# PCIe-1x-Toolcard.net
KiCad netlist of a schematic drawn in EAGLE
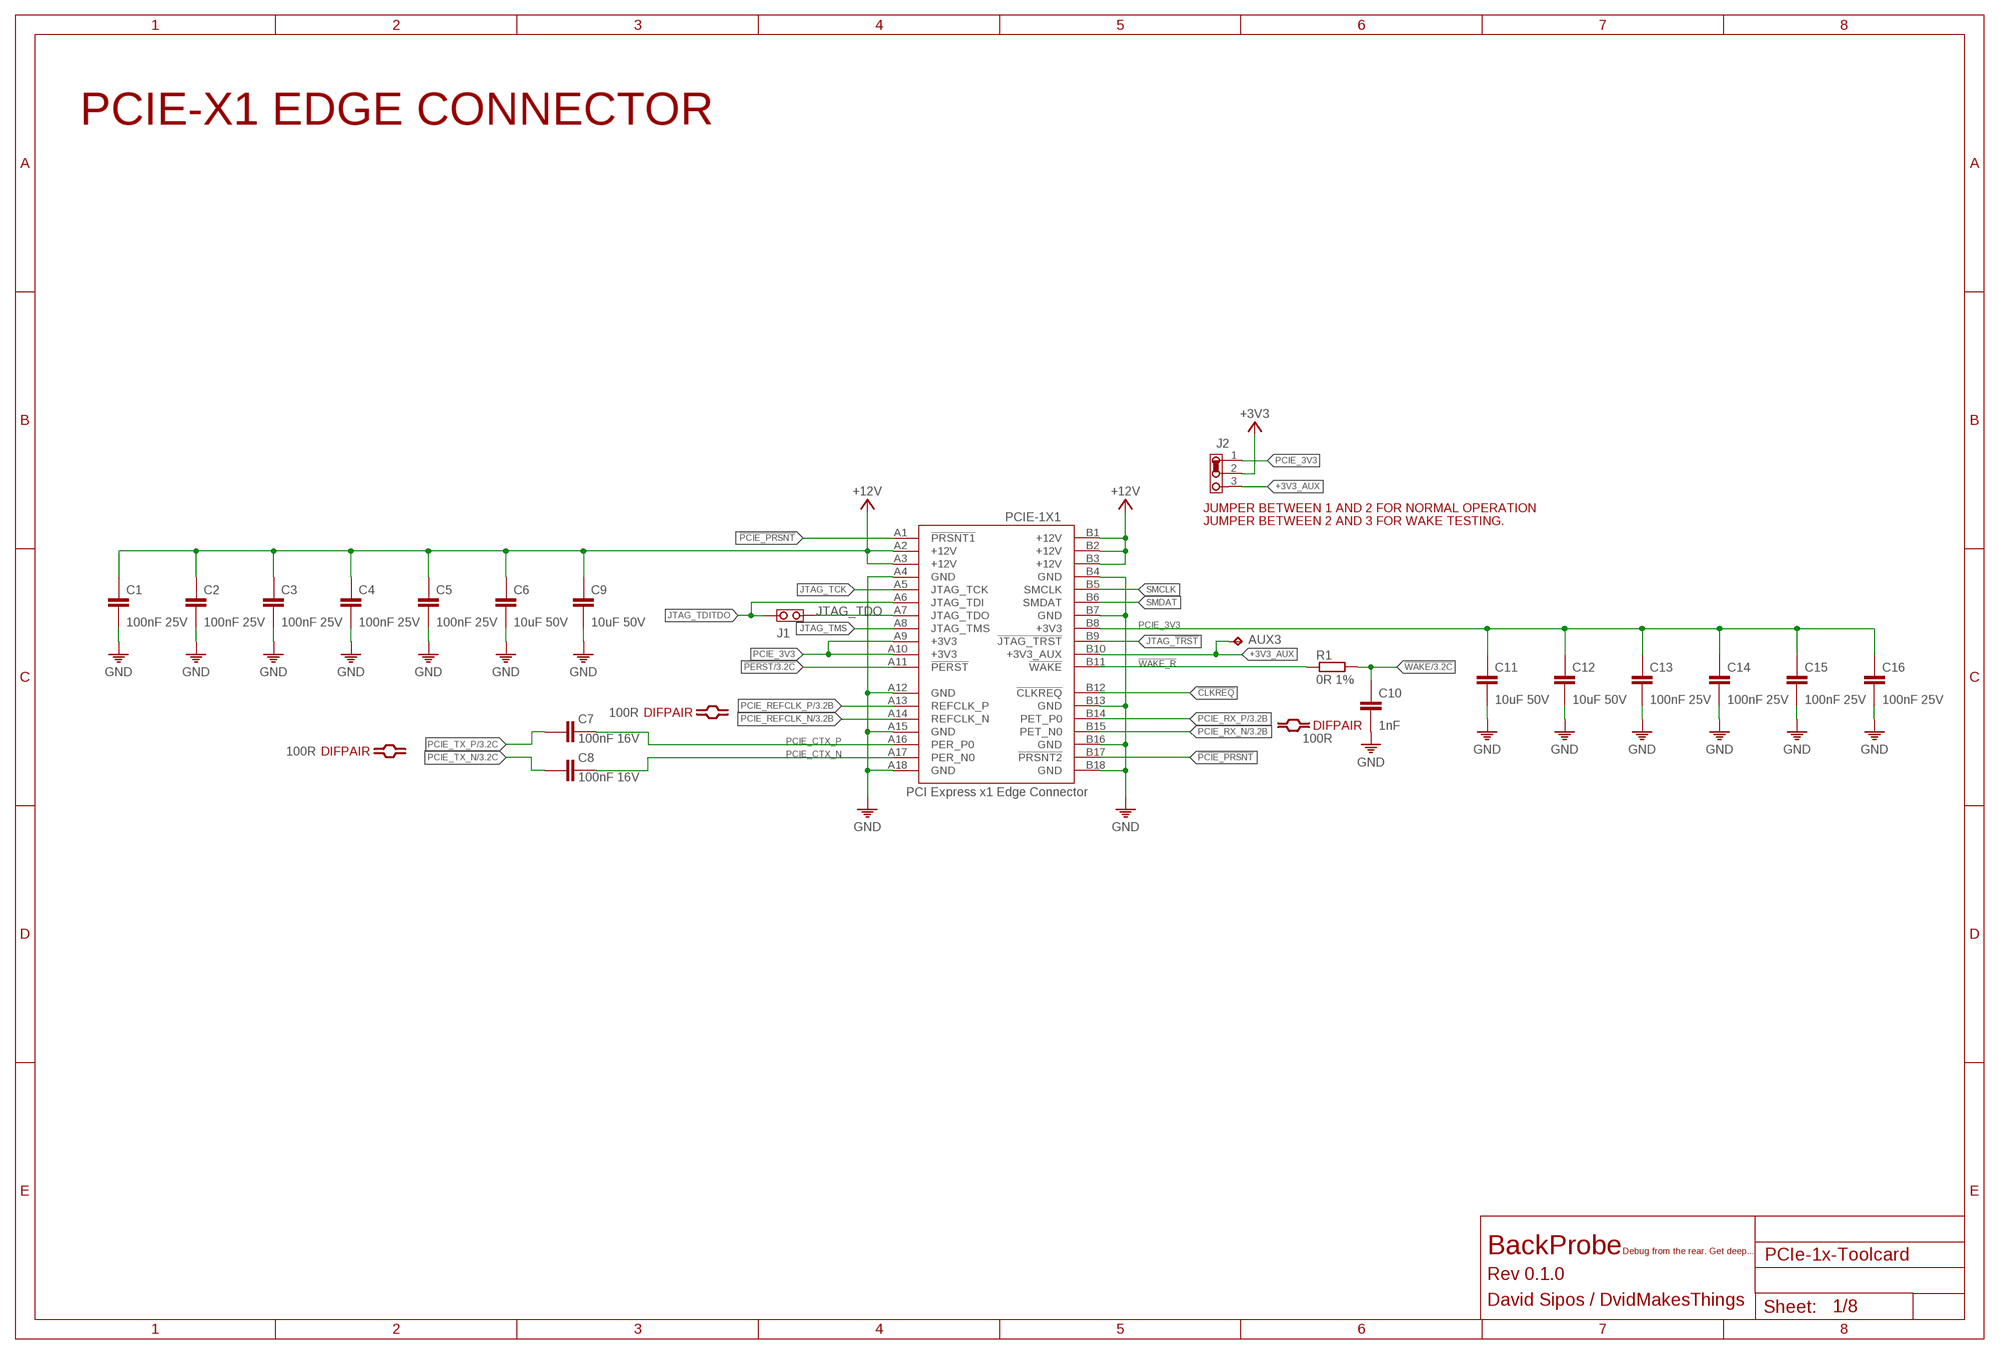
[diagram p0: schematic, sheet 1]
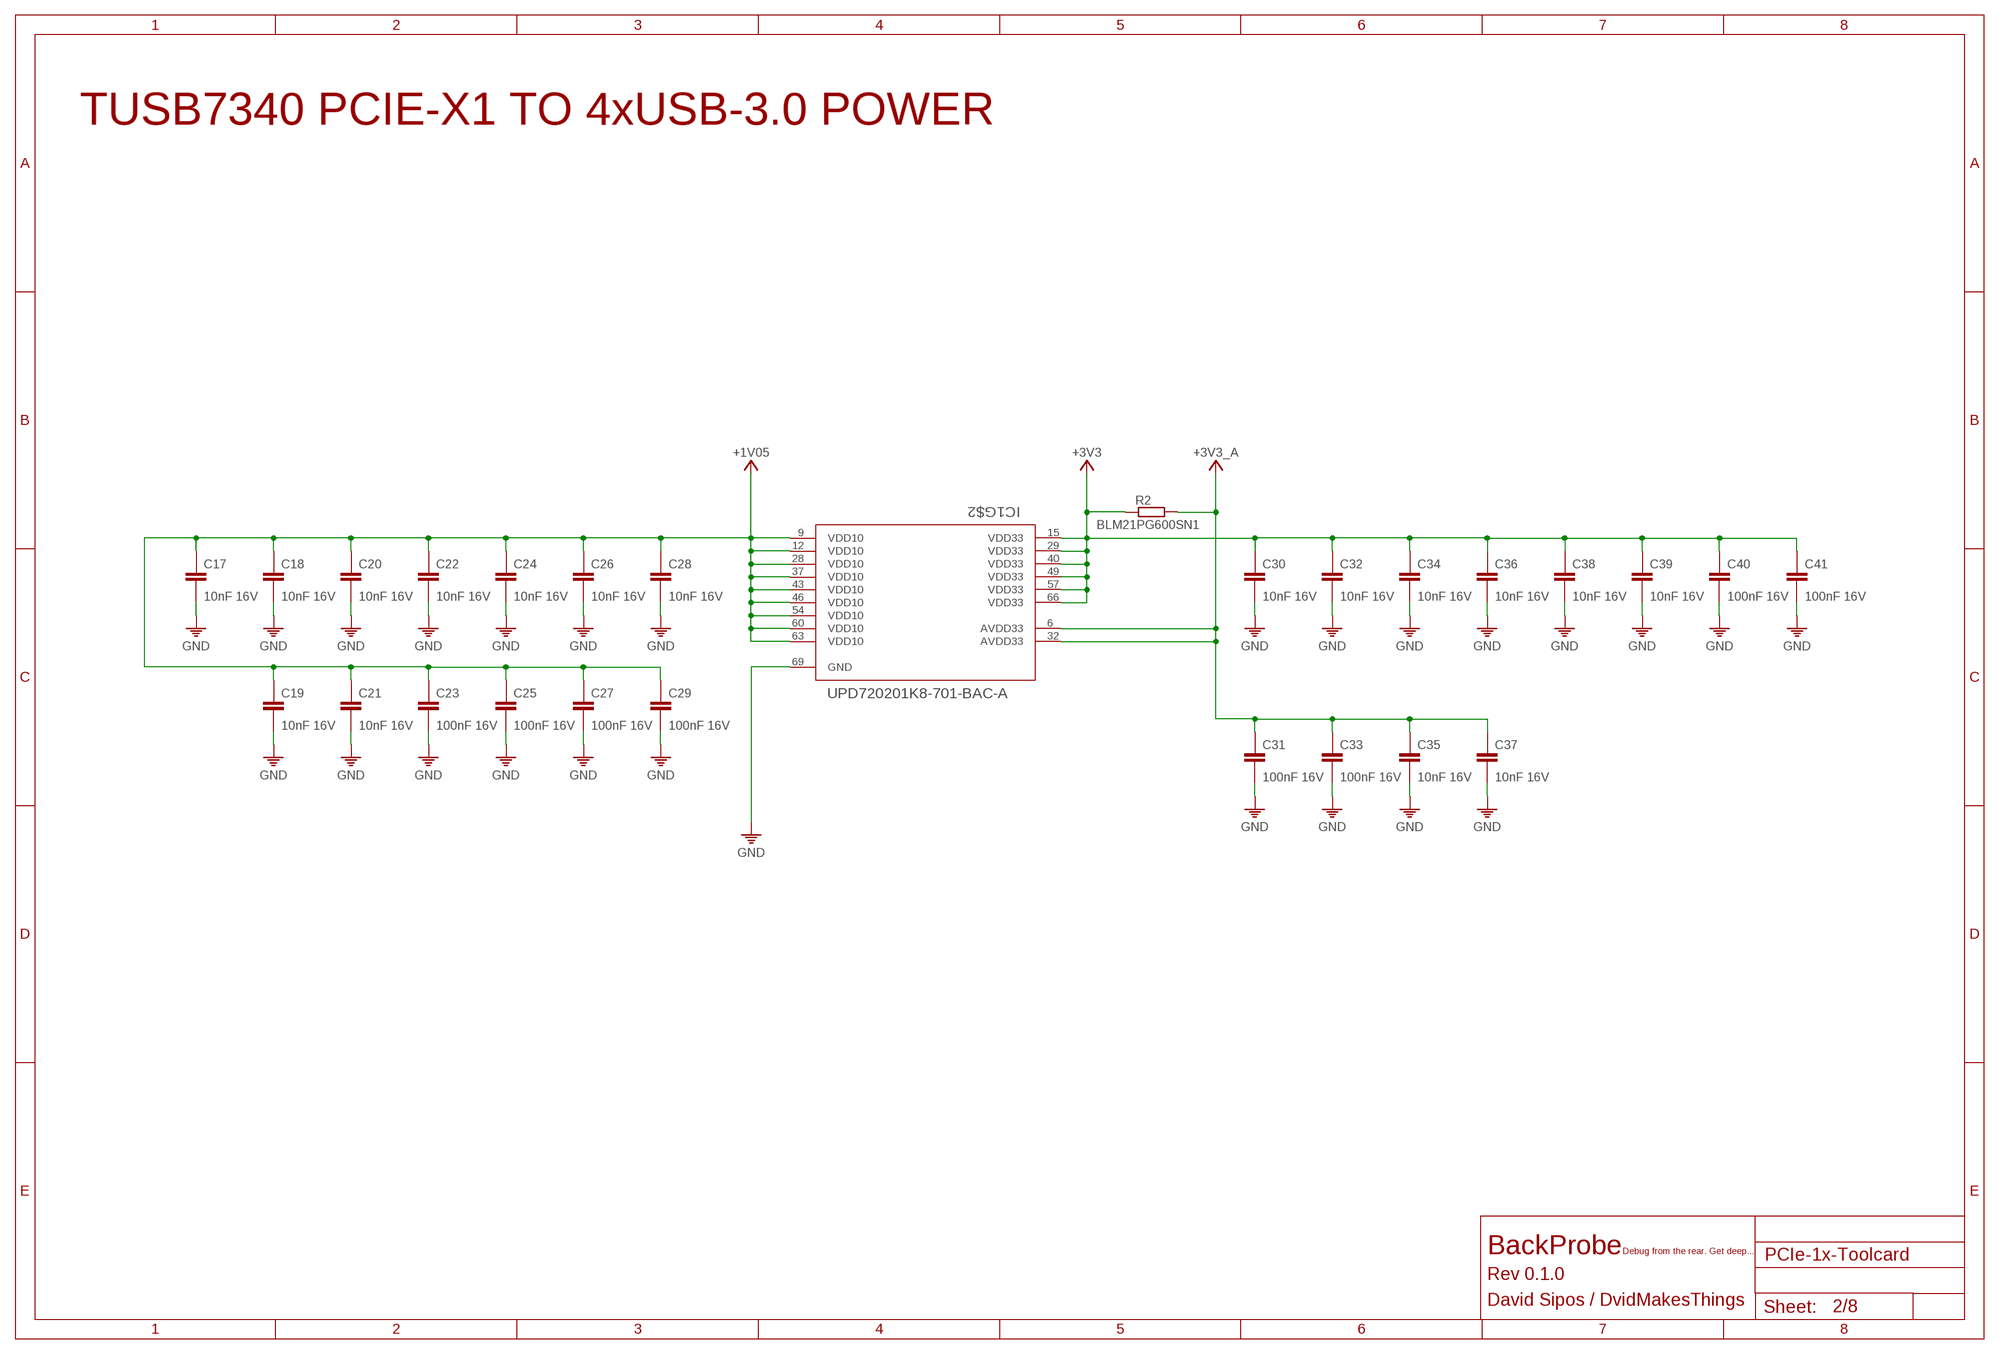
[diagram p1: schematic, sheet 2]
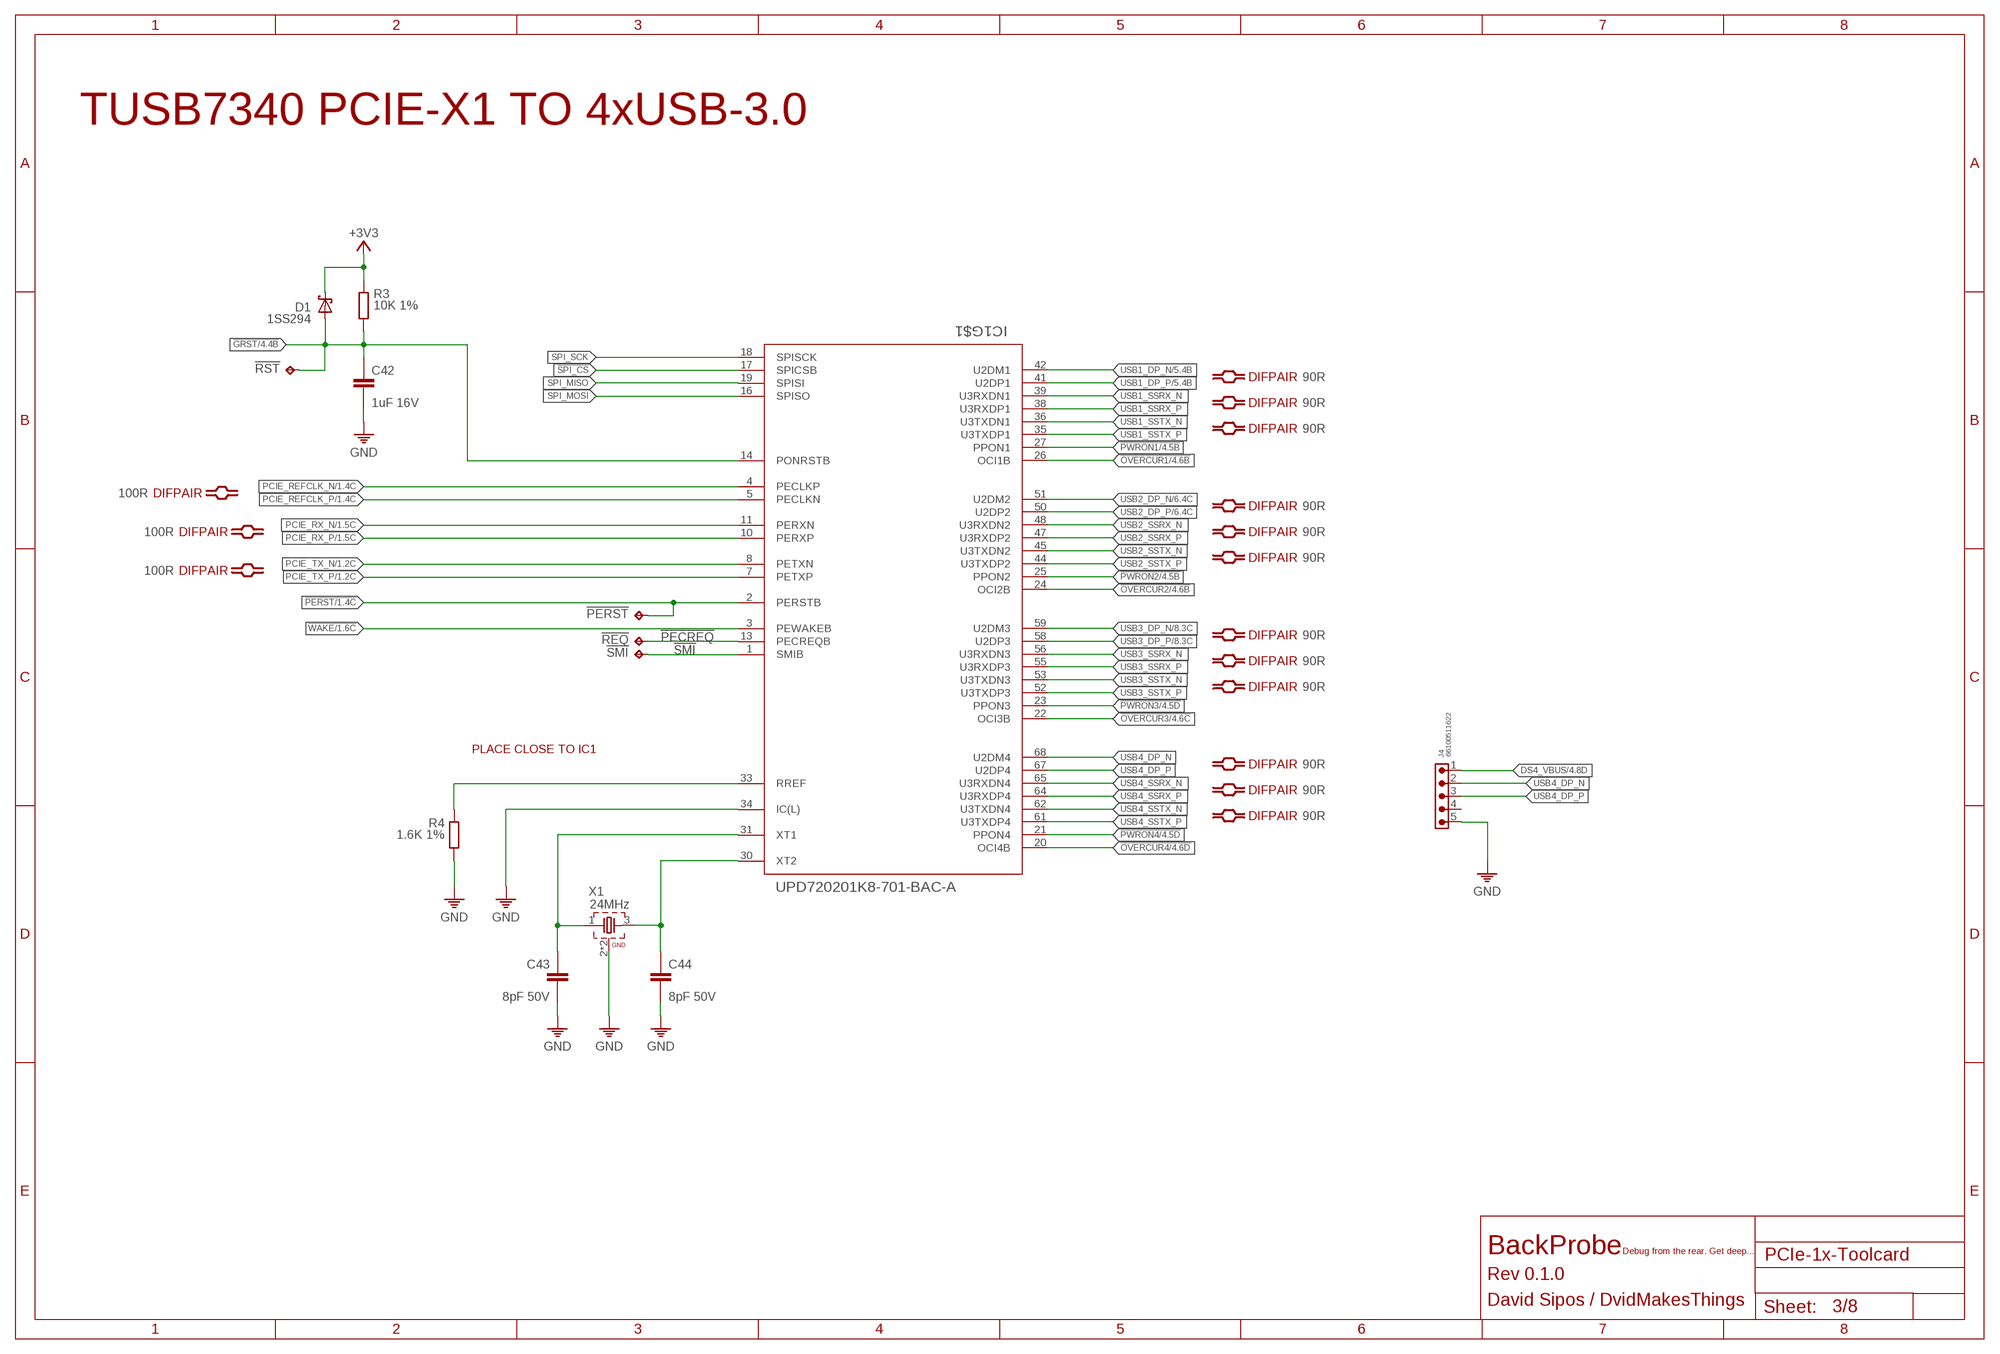
[diagram p2: schematic, sheet 3]
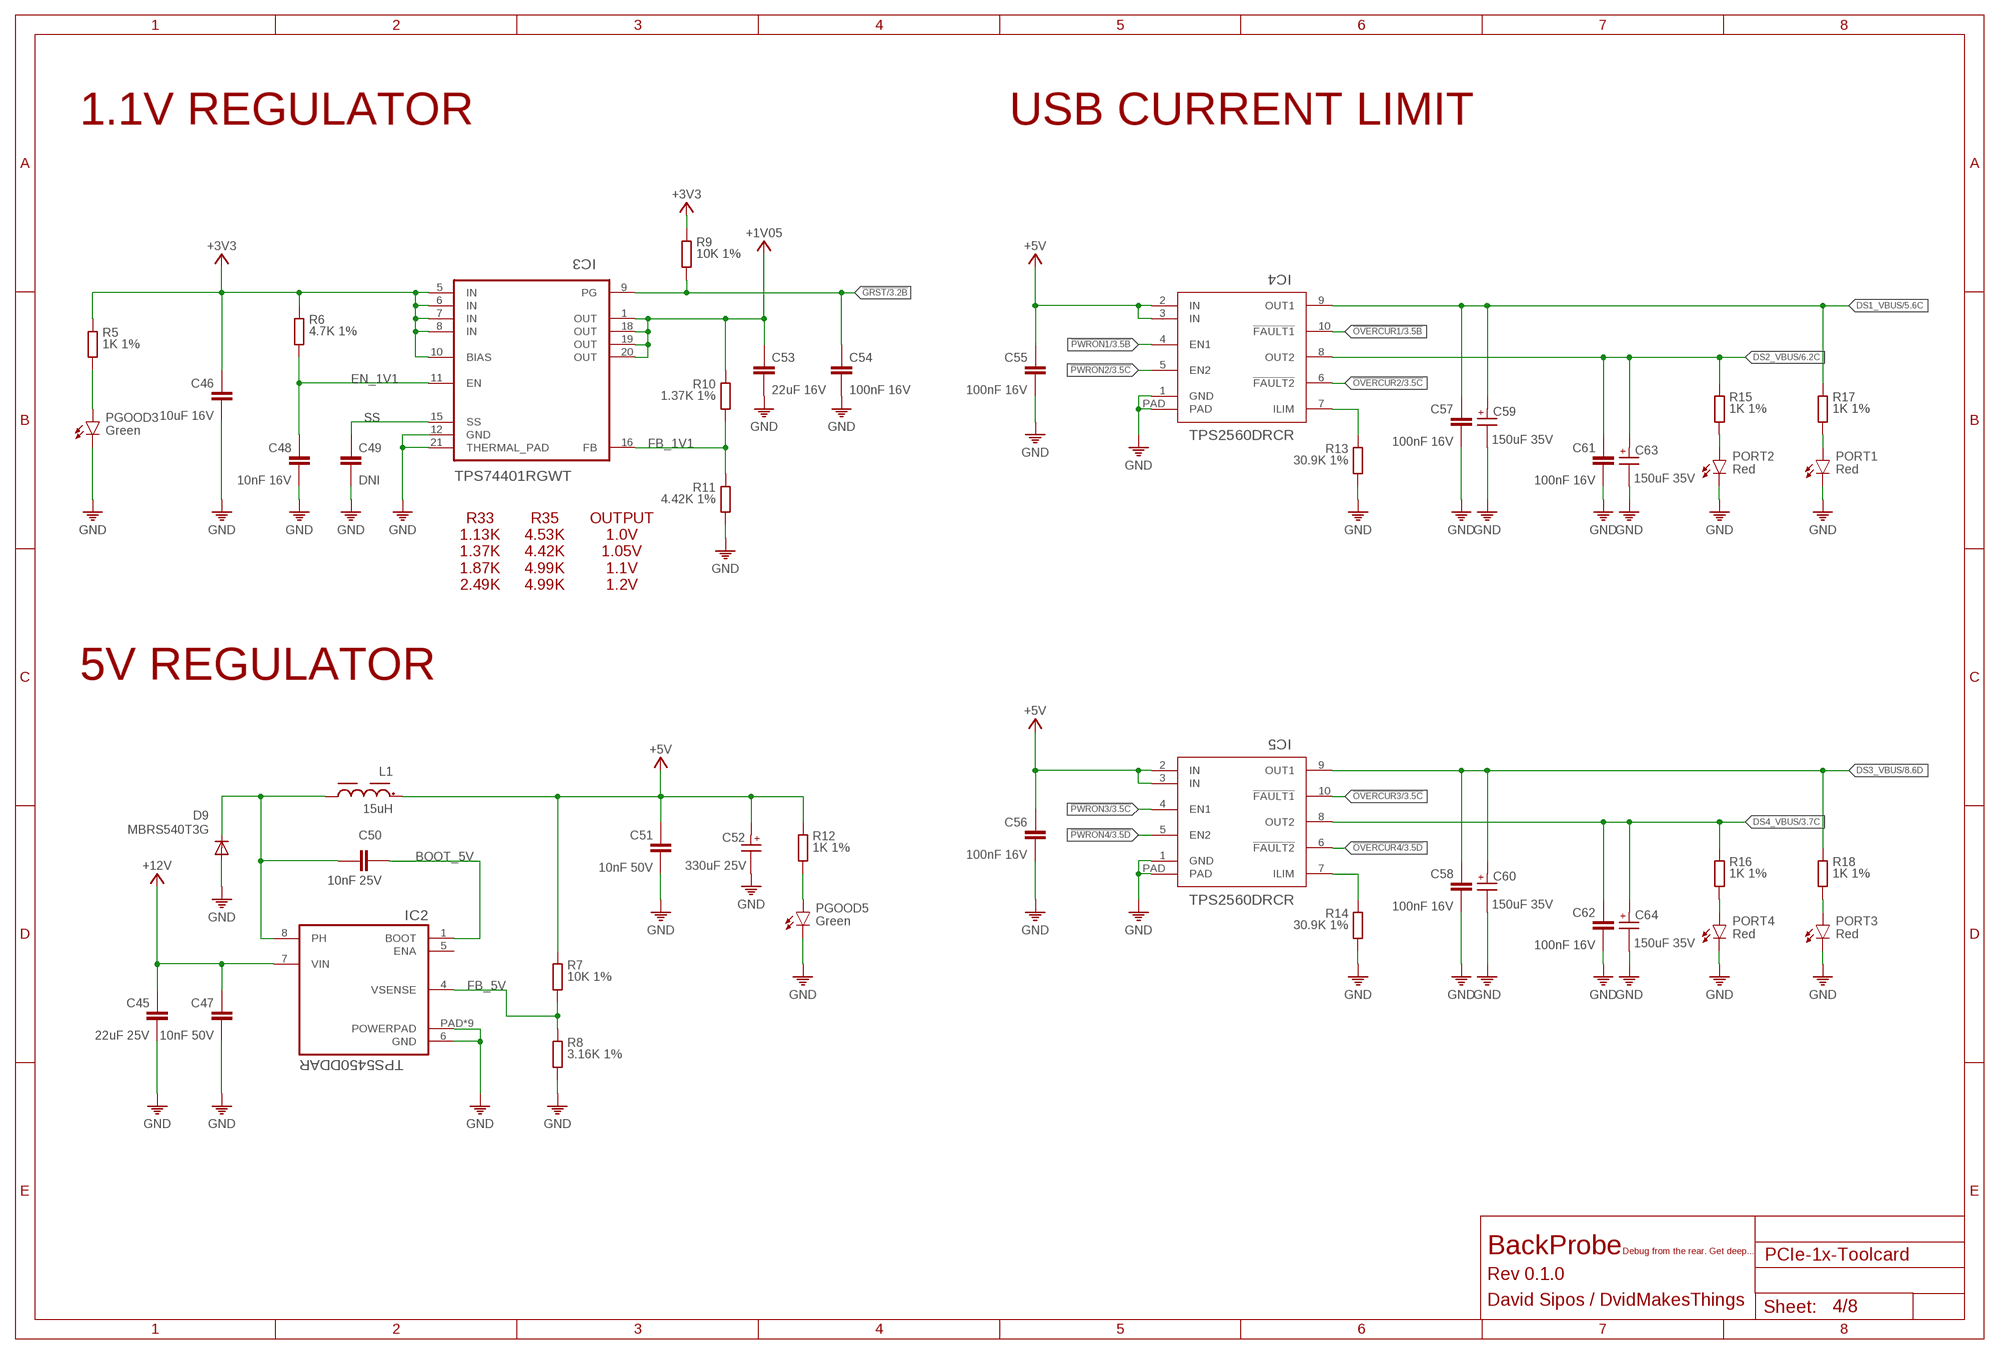
[diagram p3: schematic, sheet 4]
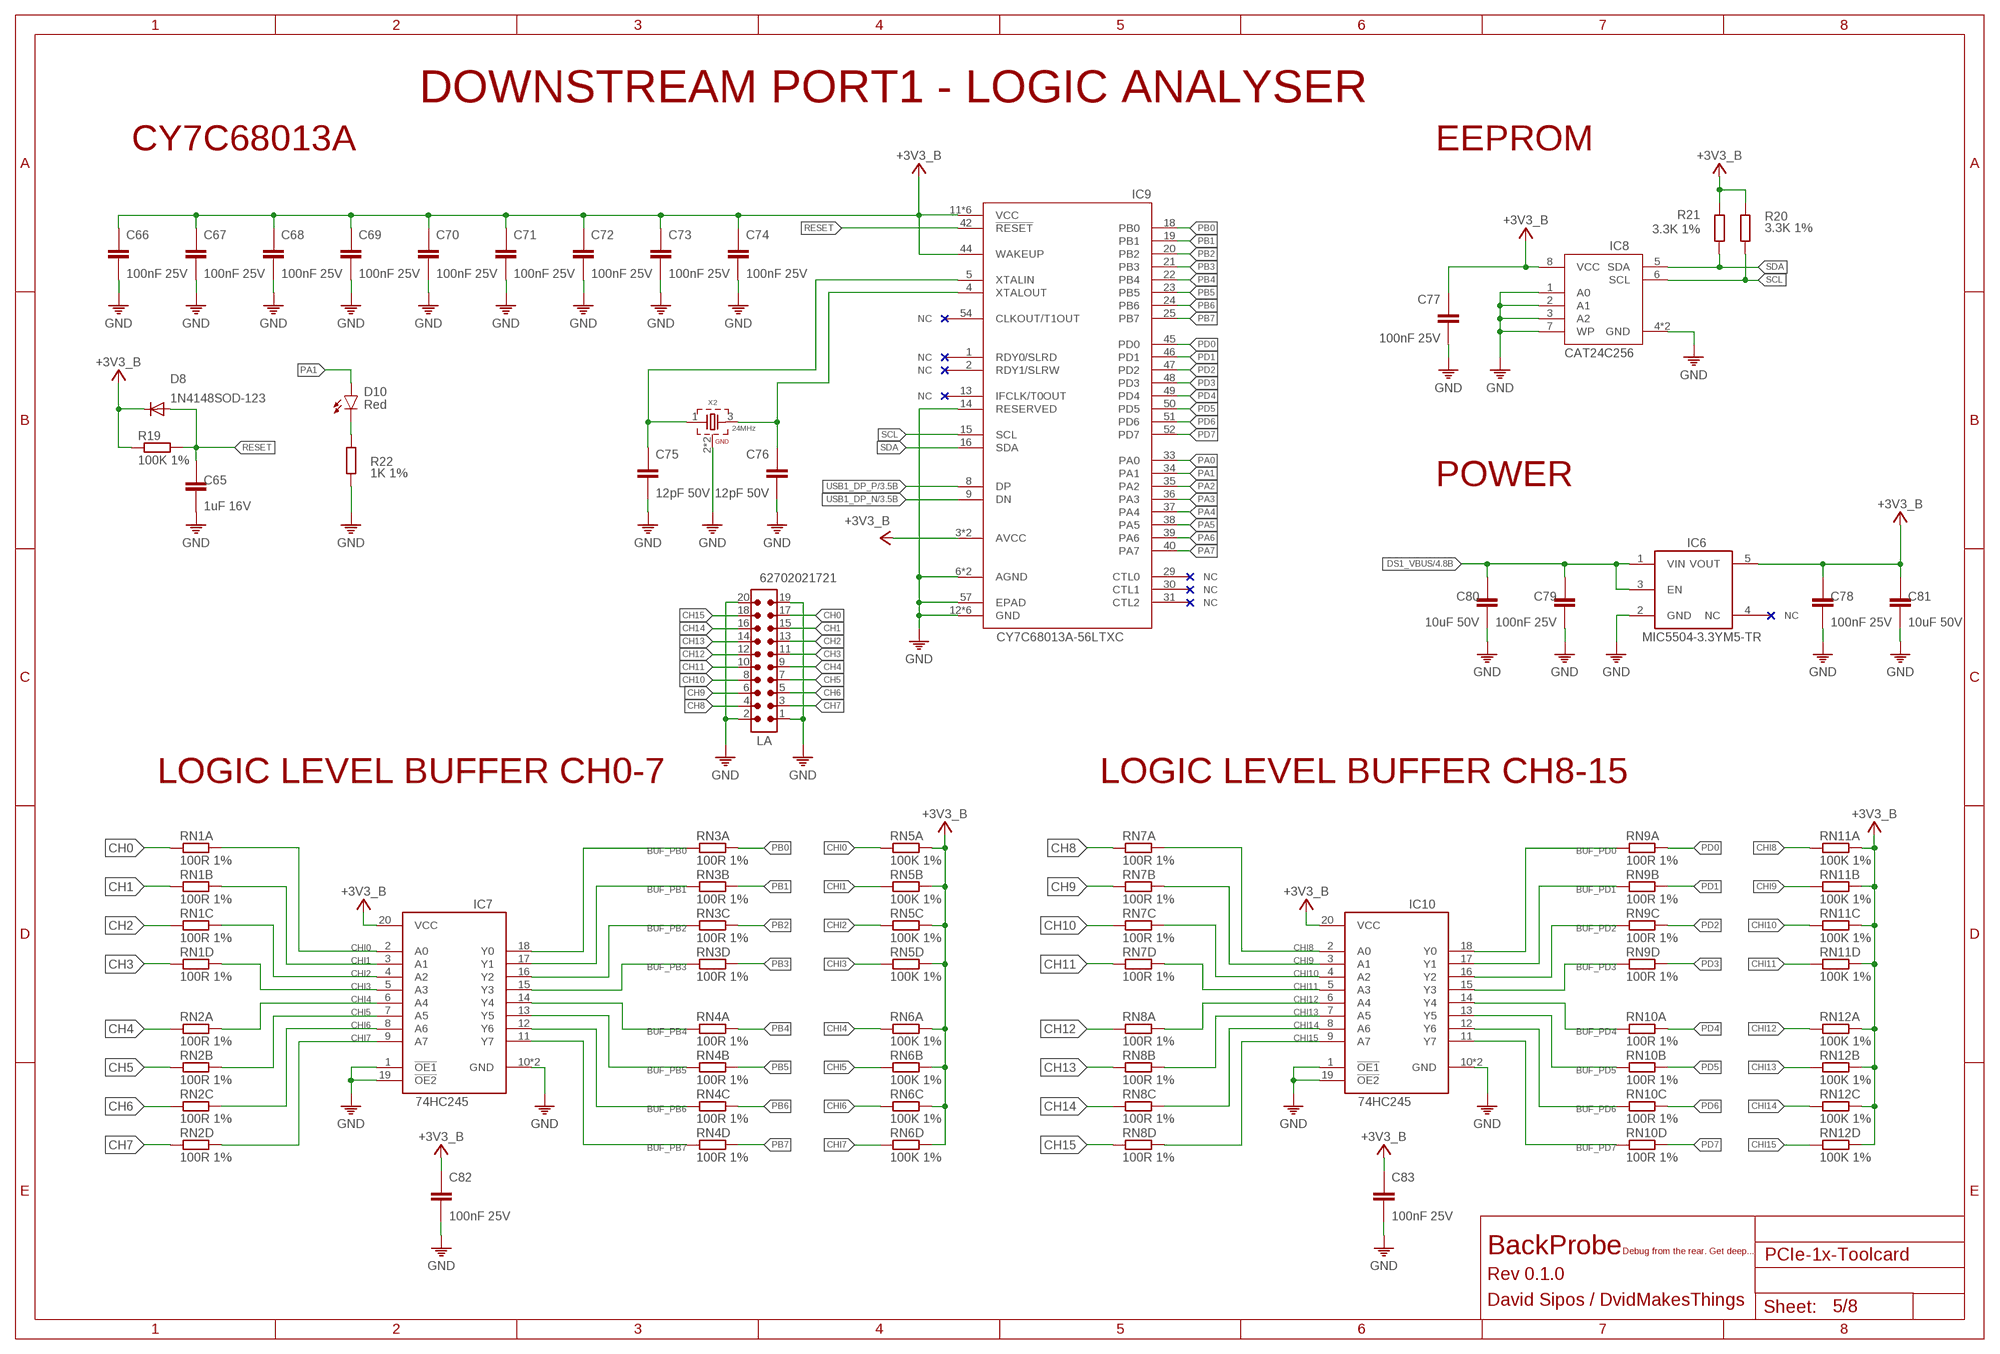
[diagram p4: schematic, sheet 5]
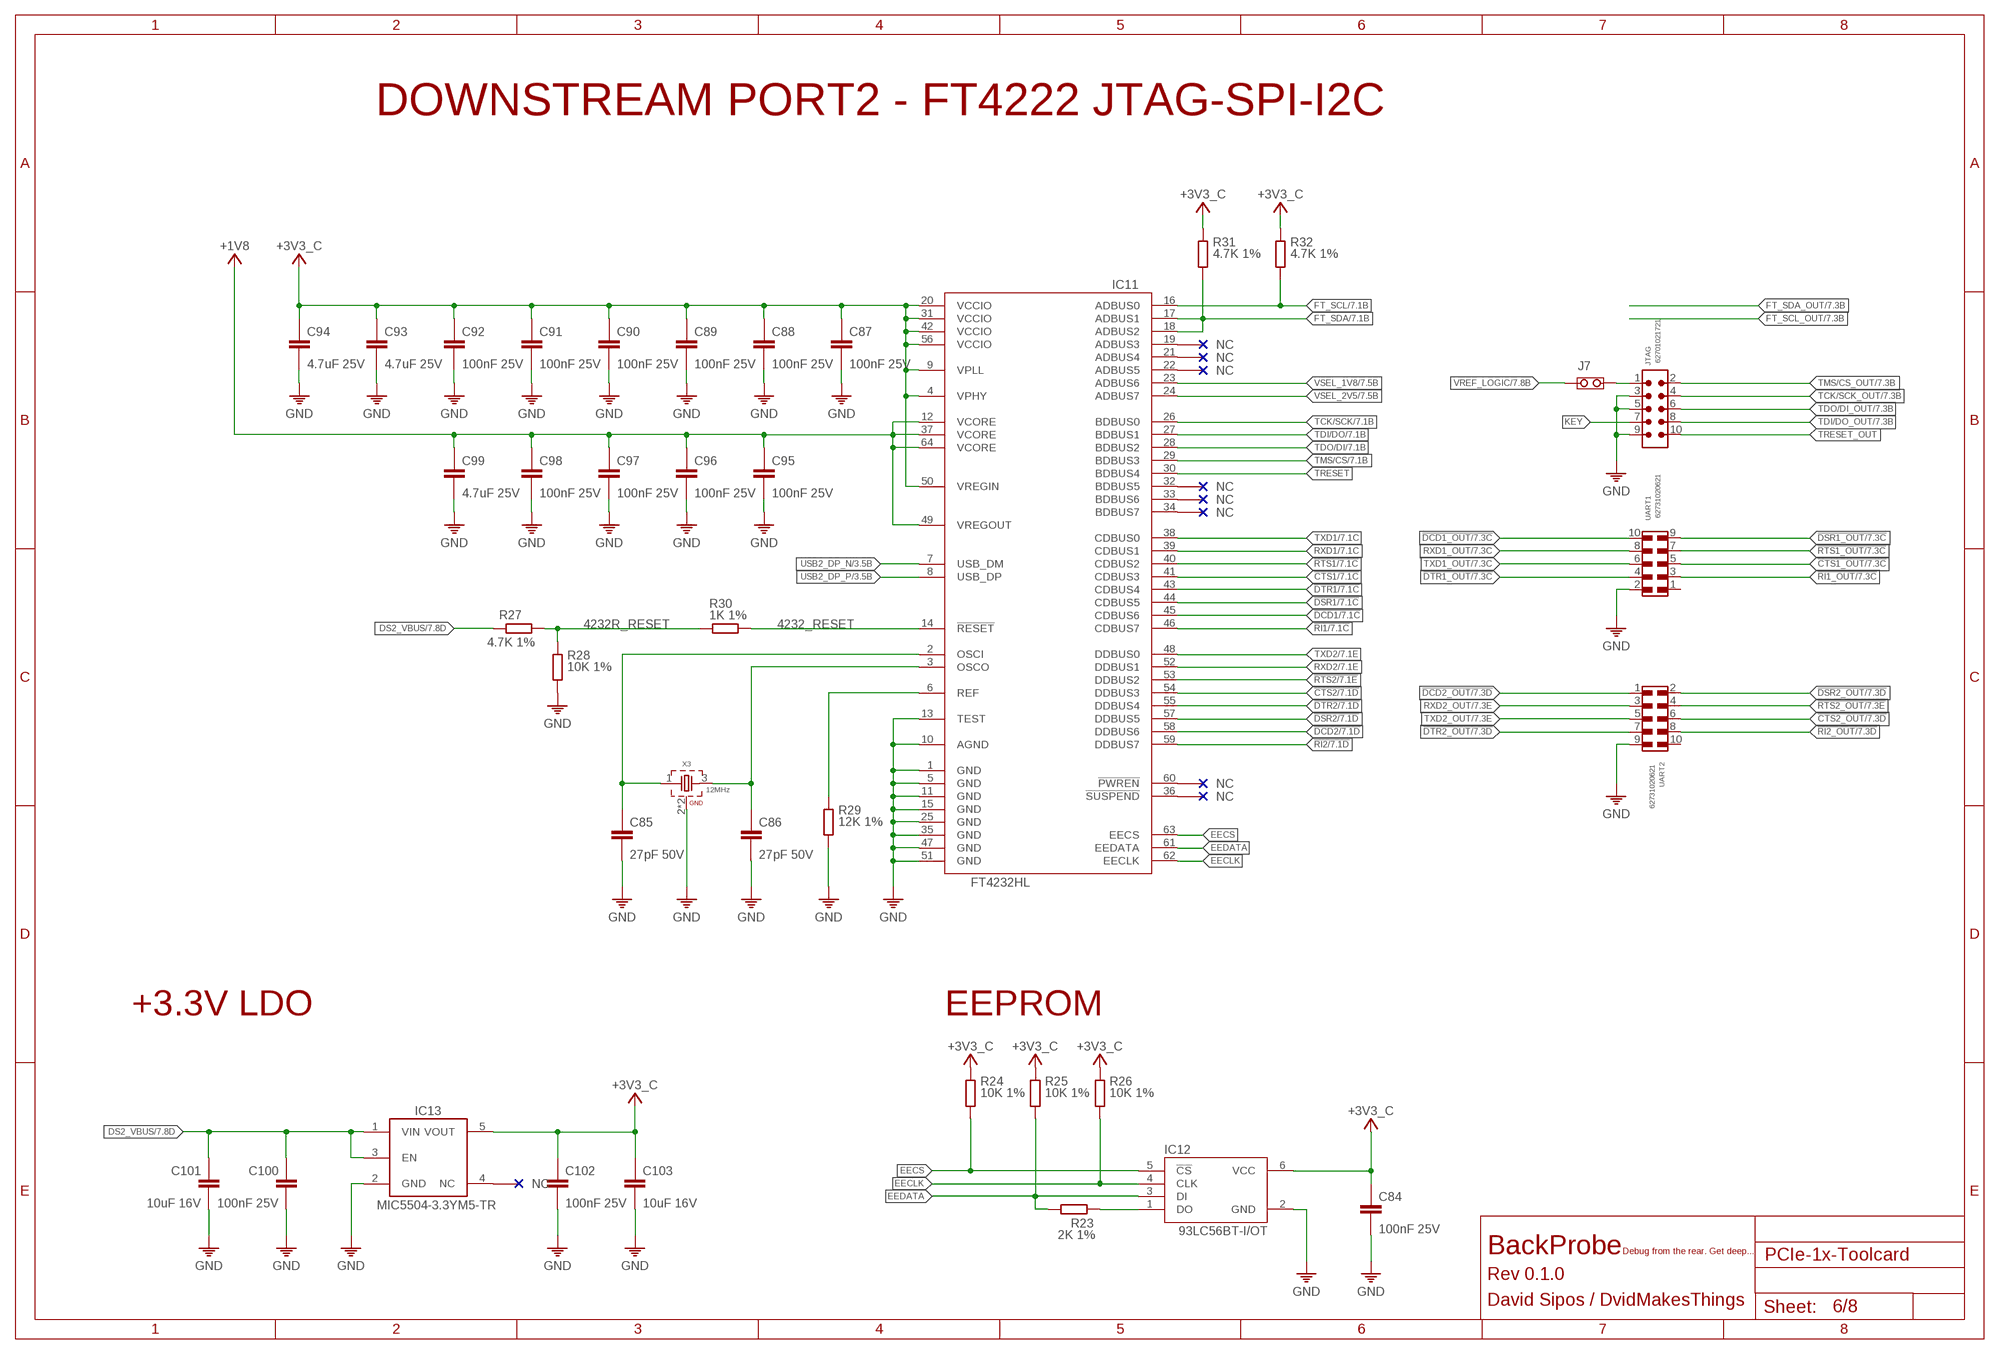
[diagram p5: schematic, sheet 6]
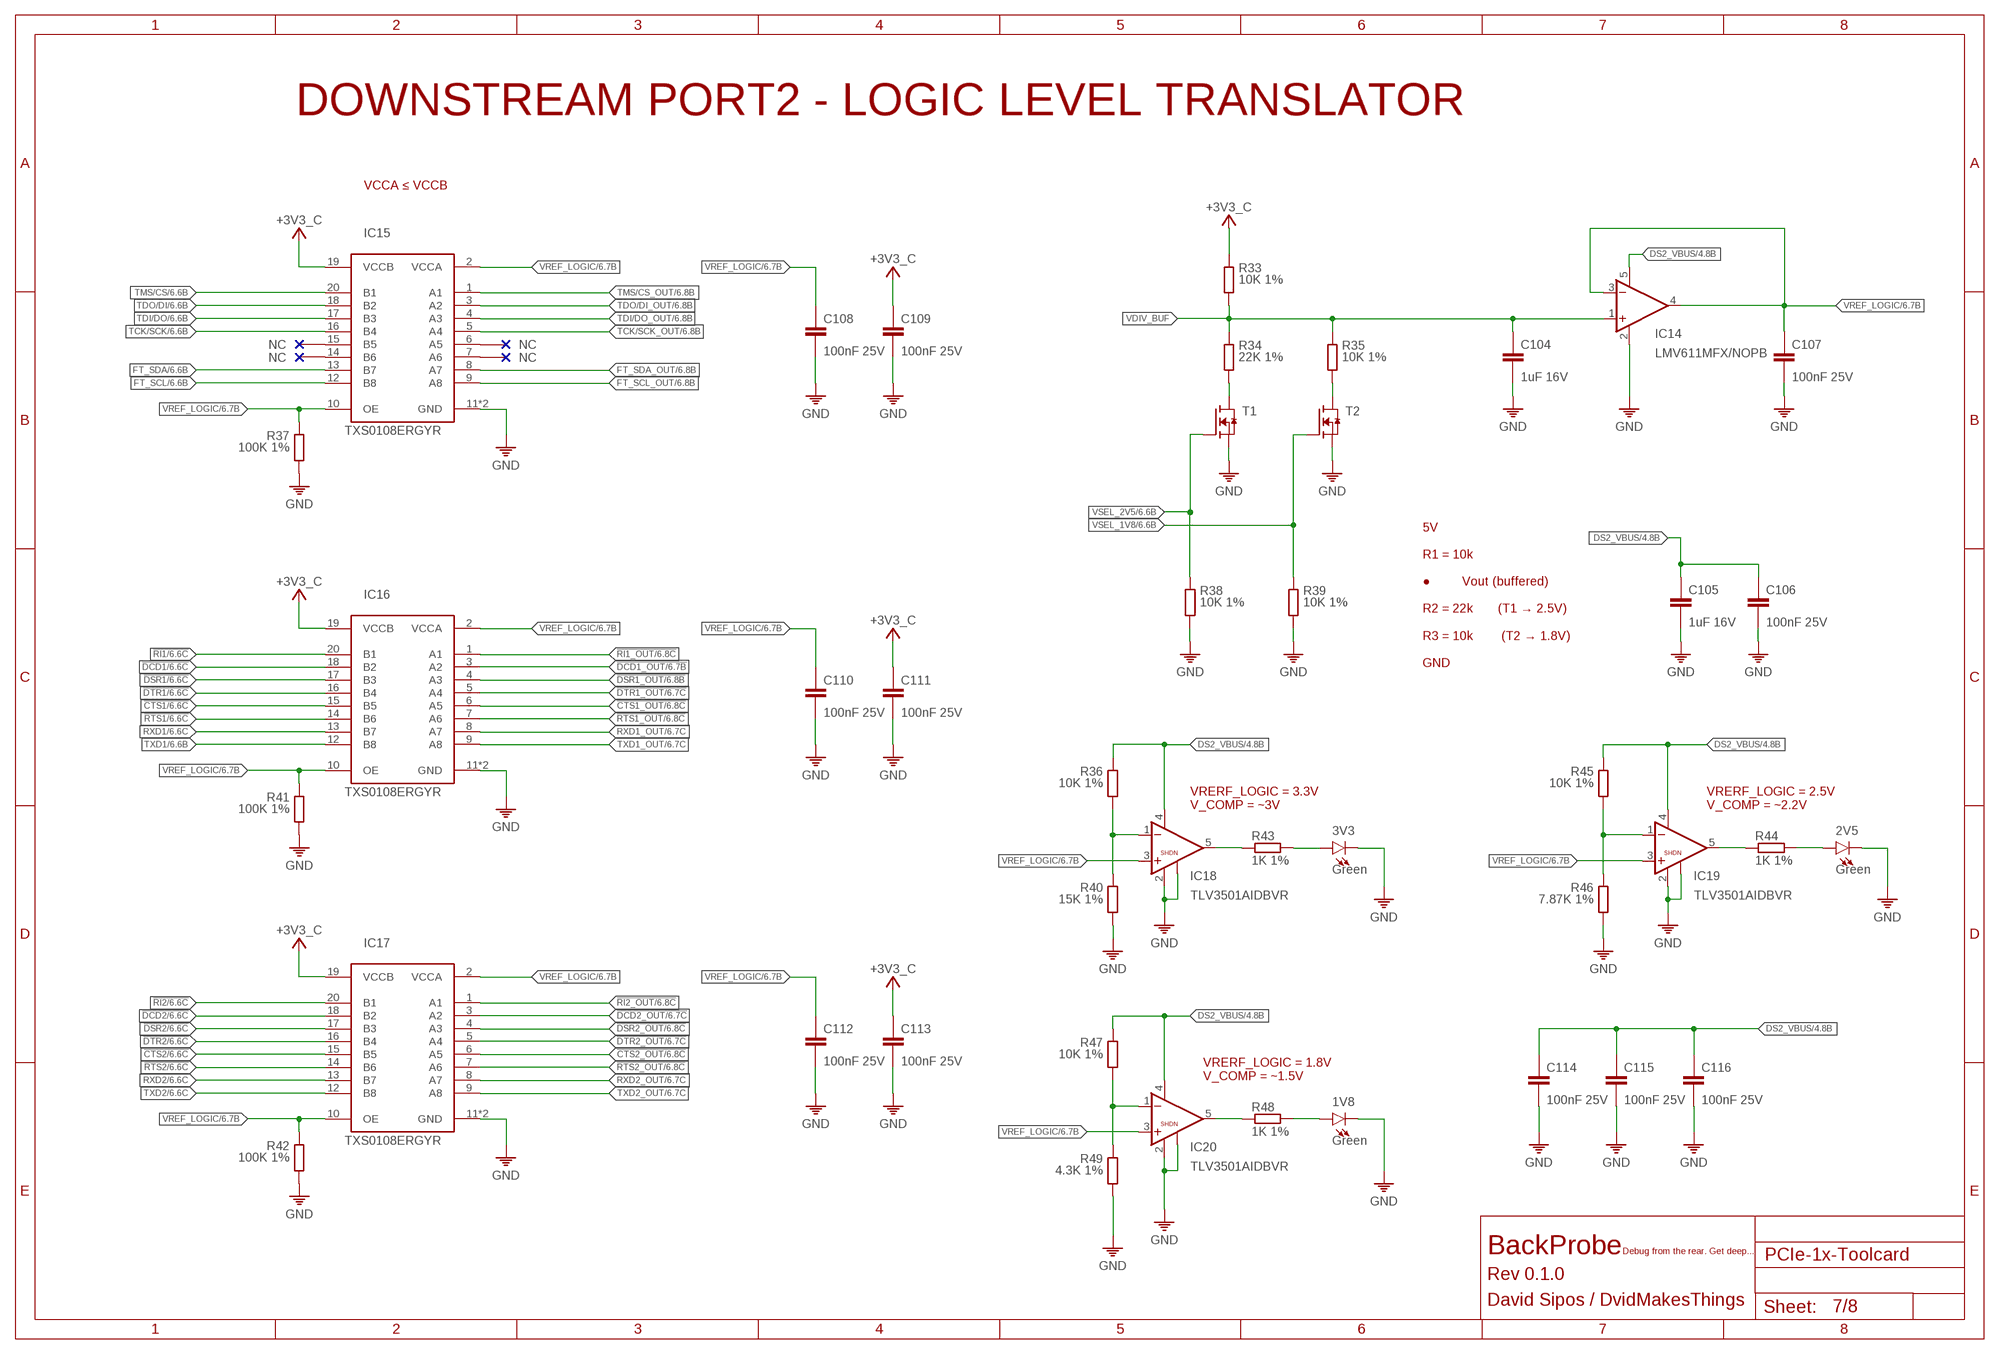
[diagram p6: schematic, sheet 7]
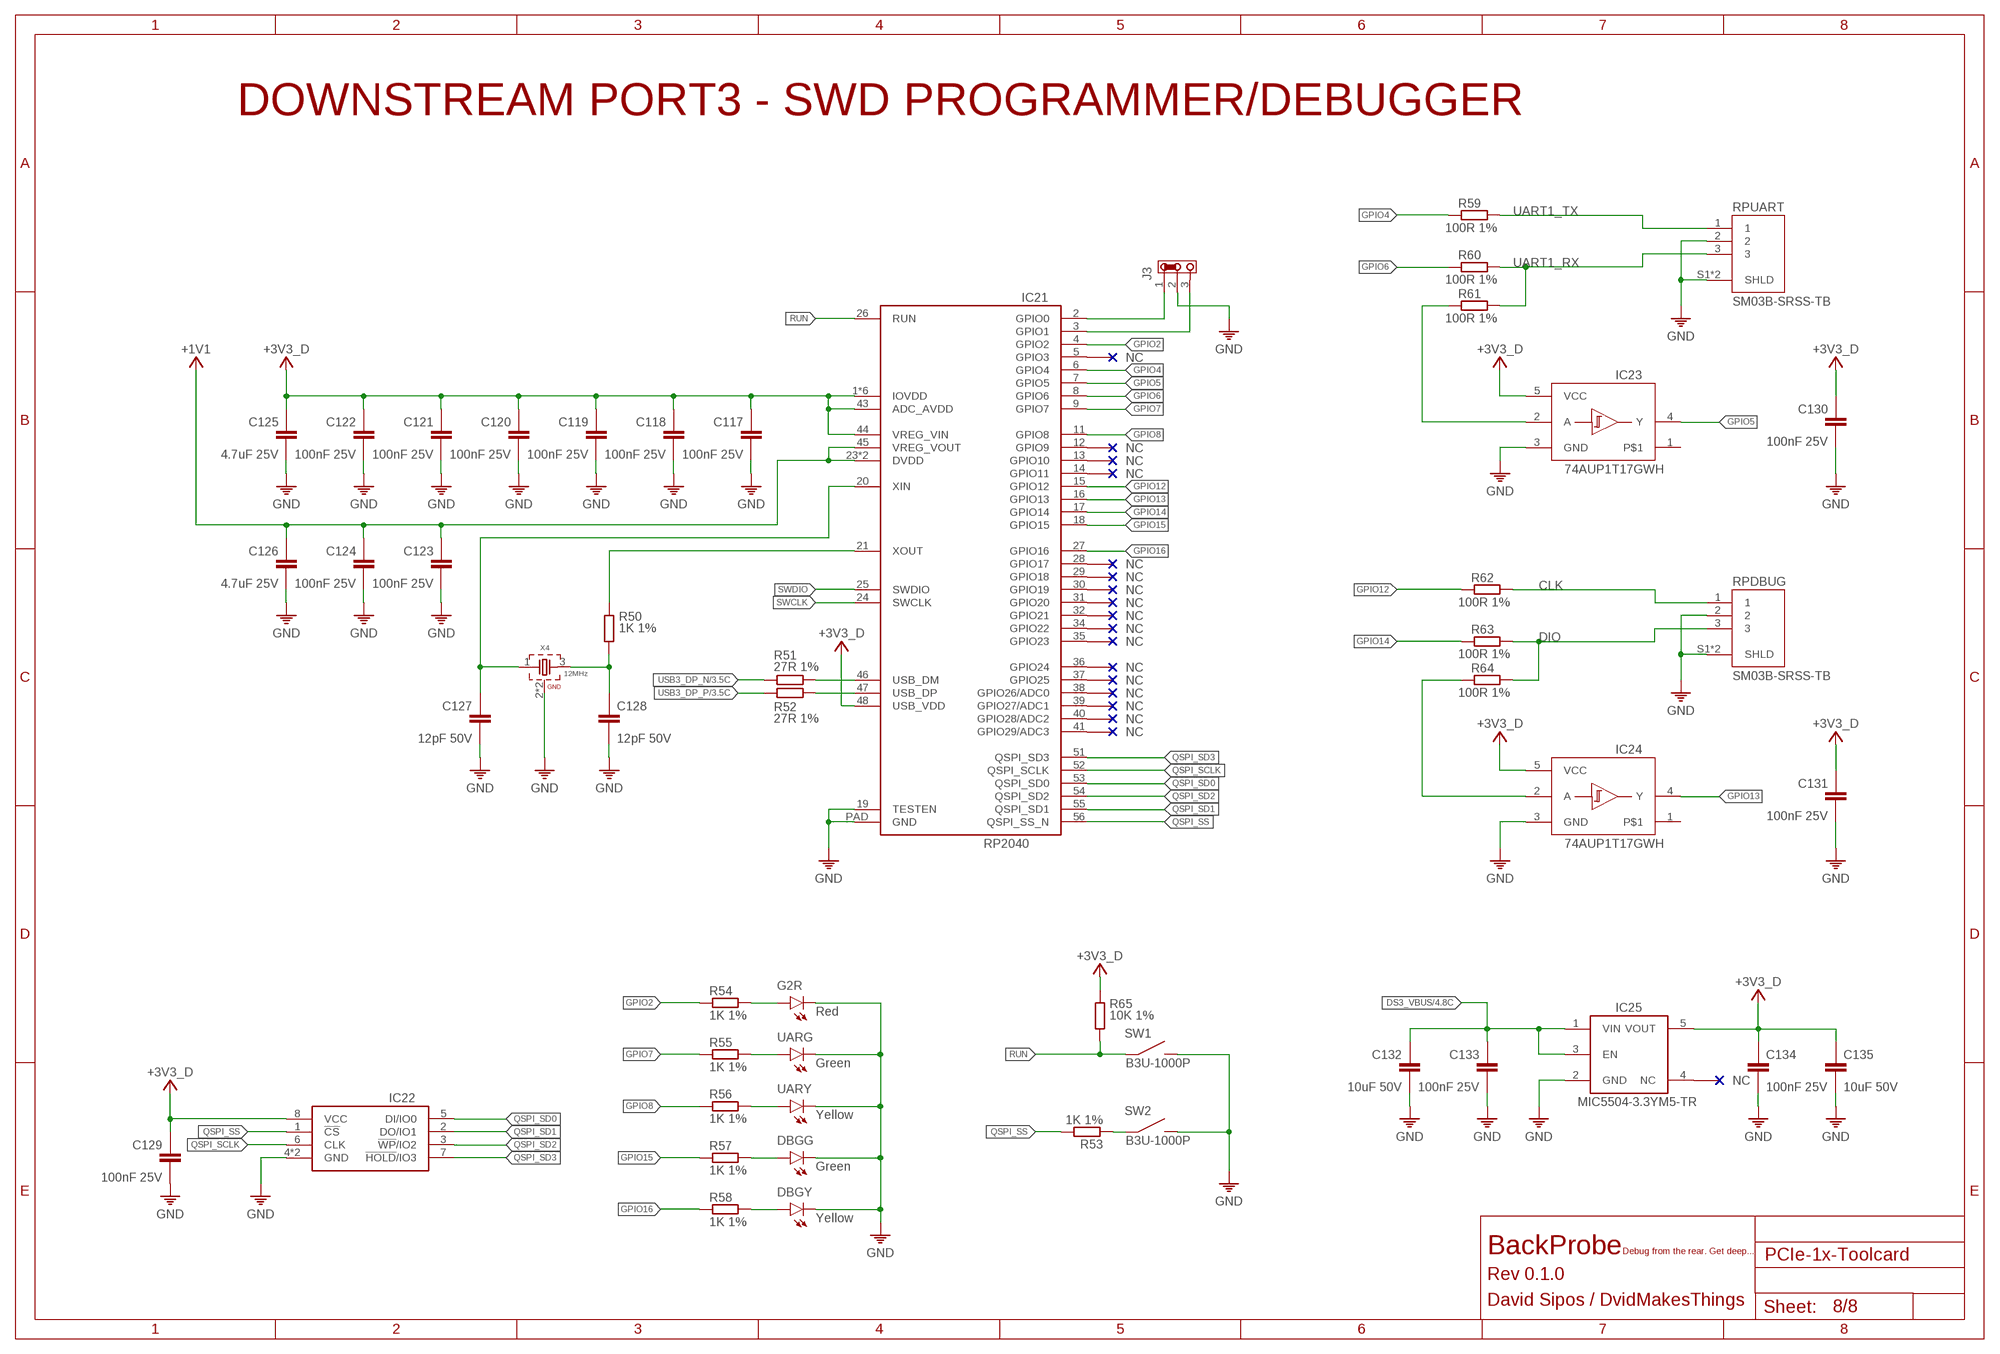
[diagram p7: schematic, sheet 8]

(export (version "E")
  (design (tool "Eeschema 10.0.6"))
  (components
    (comp (ref "1V8")
      (value "Green")
      (footprint "eagle-import:LED-0603")
      (fields (field (name "LCSC_PART") "C965804"))
      (libsource (lib "eagle-import") (part "LED-GREENLED-0603"))
    )
    (comp (ref "2V5")
      (value "Green")
      (footprint "eagle-import:LED-0603")
      (fields (field (name "LCSC_PART") "C965804"))
      (libsource (lib "eagle-import") (part "LED-GREENLED-0603"))
    )
    (comp (ref "3V3")
      (value "Green")
      (footprint "eagle-import:LED-0603")
      (fields (field (name "LCSC_PART") "C965804"))
      (libsource (lib "eagle-import") (part "LED-GREENLED-0603"))
    )
    (comp (ref "C104")
      (value "1uF 16V")
      (footprint "eagle-import:0201")
      (fields (field (name "LCSC_PART") "C307385"))
      (libsource (lib "eagle-import") (part "1UF-16V0201"))
    )
    (comp (ref "C105")
      (value "1uF 16V")
      (footprint "eagle-import:0201")
      (fields (field (name "LCSC_PART") "C307385"))
      (libsource (lib "eagle-import") (part "1UF-16V0201"))
    )
    (comp (ref "C106")
      (value "100nF 25V")
      (footprint "eagle-import:0201")
      (fields (field (name "LCSC_PART") "C76939"))
      (libsource (lib "eagle-import") (part "100NF-25V-0201"))
    )
    (comp (ref "C107")
      (value "100nF 25V")
      (footprint "eagle-import:0201")
      (fields (field (name "LCSC_PART") "C76939"))
      (libsource (lib "eagle-import") (part "100NF-25V-0201"))
    )
    (comp (ref "C108")
      (value "100nF 25V")
      (footprint "eagle-import:0201")
      (fields (field (name "LCSC_PART") "C76939"))
      (libsource (lib "eagle-import") (part "100NF-25V-0201"))
    )
    (comp (ref "C109")
      (value "100nF 25V")
      (footprint "eagle-import:0201")
      (fields (field (name "LCSC_PART") "C76939"))
      (libsource (lib "eagle-import") (part "100NF-25V-0201"))
    )
    (comp (ref "C110")
      (value "100nF 25V")
      (footprint "eagle-import:0201")
      (fields (field (name "LCSC_PART") "C76939"))
      (libsource (lib "eagle-import") (part "100NF-25V-0201"))
    )
    (comp (ref "C111")
      (value "100nF 25V")
      (footprint "eagle-import:0201")
      (fields (field (name "LCSC_PART") "C76939"))
      (libsource (lib "eagle-import") (part "100NF-25V-0201"))
    )
    (comp (ref "C112")
      (value "100nF 25V")
      (footprint "eagle-import:0201")
      (fields (field (name "LCSC_PART") "C76939"))
      (libsource (lib "eagle-import") (part "100NF-25V-0201"))
    )
    (comp (ref "C113")
      (value "100nF 25V")
      (footprint "eagle-import:0201")
      (fields (field (name "LCSC_PART") "C76939"))
      (libsource (lib "eagle-import") (part "100NF-25V-0201"))
    )
    (comp (ref "C114")
      (value "100nF 25V")
      (footprint "eagle-import:0201")
      (fields (field (name "LCSC_PART") "C76939"))
      (libsource (lib "eagle-import") (part "100NF-25V-0201"))
    )
    (comp (ref "C115")
      (value "100nF 25V")
      (footprint "eagle-import:0201")
      (fields (field (name "LCSC_PART") "C76939"))
      (libsource (lib "eagle-import") (part "100NF-25V-0201"))
    )
    (comp (ref "C116")
      (value "100nF 25V")
      (footprint "eagle-import:0201")
      (fields (field (name "LCSC_PART") "C76939"))
      (libsource (lib "eagle-import") (part "100NF-25V-0201"))
    )
    (comp (ref "IC14")
      (value "LMV611MFX/NOPB")
      (footprint "eagle-import:SOT23-5")
      (fields (field (name "LCSC_PART") "C165135"))
      (libsource (lib "eagle-import") (part "LMV611MFX"))
    )
    (comp (ref "IC15")
      (value "TXS0108ERGYR")
      (footprint "eagle-import:VQFN24")
      (fields (field (name "LCSC_PART") "C90706"))
      (libsource (lib "eagle-import") (part "TXB0108RGY"))
    )
    (comp (ref "IC16")
      (value "TXS0108ERGYR")
      (footprint "eagle-import:VQFN24")
      (fields (field (name "LCSC_PART") "C90706"))
      (libsource (lib "eagle-import") (part "TXB0108RGY"))
    )
    (comp (ref "IC17")
      (value "TXS0108ERGYR")
      (footprint "eagle-import:VQFN24")
      (fields (field (name "LCSC_PART") "C90706"))
      (libsource (lib "eagle-import") (part "TXB0108RGY"))
    )
    (comp (ref "IC18")
      (value "TLV3501AIDBVR")
      (footprint "eagle-import:SOT95P280X145-6N")
      (fields (field (name "LCSC_PART") "C193413"))
      (libsource (lib "eagle-import") (part "TLV3501AIDB"))
    )
    (comp (ref "IC19")
      (value "TLV3501AIDBVR")
      (footprint "eagle-import:SOT95P280X145-6N")
      (fields (field (name "LCSC_PART") "C193413"))
      (libsource (lib "eagle-import") (part "TLV3501AIDB"))
    )
    (comp (ref "IC20")
      (value "TLV3501AIDBVR")
      (footprint "eagle-import:SOT95P280X145-6N")
      (fields (field (name "LCSC_PART") "C193413"))
      (libsource (lib "eagle-import") (part "TLV3501AIDB"))
    )
    (comp (ref "R33")
      (value "10K 1%")
      (footprint "eagle-import:0402")
      (fields (field (name "LCSC_PART") "C25744"))
      (libsource (lib "eagle-import") (part "10K-1%0402"))
    )
    (comp (ref "R34")
      (value "22K 1%")
      (footprint "eagle-import:0402")
      (fields (field (name "LCSC_PART") "C82868"))
      (libsource (lib "eagle-import") (part "22K-1%0402"))
    )
    (comp (ref "R35")
      (value "10K 1%")
      (footprint "eagle-import:0402")
      (fields (field (name "LCSC_PART") "C25744"))
      (libsource (lib "eagle-import") (part "10K-1%0402"))
    )
    (comp (ref "R36")
      (value "10K 1%")
      (footprint "eagle-import:0201")
      (fields (field (name "LCSC_PART") "C473048"))
      (libsource (lib "eagle-import") (part "10K-1%0201"))
    )
    (comp (ref "R37")
      (value "100K 1%")
      (footprint "eagle-import:0201")
      (fields (field (name "LCSC_PART") "C270364"))
      (libsource (lib "eagle-import") (part "100K-1%0201"))
    )
    (comp (ref "R38")
      (value "10K 1%")
      (footprint "eagle-import:0402")
      (fields (field (name "LCSC_PART") "C25744"))
      (libsource (lib "eagle-import") (part "10K-1%0402"))
    )
    (comp (ref "R39")
      (value "10K 1%")
      (footprint "eagle-import:0402")
      (fields (field (name "LCSC_PART") "C25744"))
      (libsource (lib "eagle-import") (part "10K-1%0402"))
    )
    (comp (ref "R40")
      (value "15K 1%")
      (footprint "eagle-import:0201")
      (fields (field (name "LCSC_PART") "C295774"))
      (libsource (lib "eagle-import") (part "15K-1%0201"))
    )
    (comp (ref "R41")
      (value "100K 1%")
      (footprint "eagle-import:0201")
      (fields (field (name "LCSC_PART") "C270364"))
      (libsource (lib "eagle-import") (part "100K-1%0201"))
    )
    (comp (ref "R42")
      (value "100K 1%")
      (footprint "eagle-import:0201")
      (fields (field (name "LCSC_PART") "C270364"))
      (libsource (lib "eagle-import") (part "100K-1%0201"))
    )
    (comp (ref "R43")
      (value "1K 1%")
      (footprint "eagle-import:0603")
      (fields (field (name "LCSC_PART") "C21190"))
      (libsource (lib "eagle-import") (part "1K-1%0603"))
    )
    (comp (ref "R44")
      (value "1K 1%")
      (footprint "eagle-import:0603")
      (fields (field (name "LCSC_PART") "C21190"))
      (libsource (lib "eagle-import") (part "1K-1%0603"))
    )
    (comp (ref "R45")
      (value "10K 1%")
      (footprint "eagle-import:0201")
      (fields (field (name "LCSC_PART") "C473048"))
      (libsource (lib "eagle-import") (part "10K-1%0201"))
    )
    (comp (ref "R46")
      (value "7.87K 1%")
      (footprint "eagle-import:0201")
      (fields (field (name "LCSC_PART") "C473937"))
      (libsource (lib "eagle-import") (part "7.87K-1%0201"))
    )
    (comp (ref "R47")
      (value "10K 1%")
      (footprint "eagle-import:0201")
      (fields (field (name "LCSC_PART") "C473048"))
      (libsource (lib "eagle-import") (part "10K-1%0201"))
    )
    (comp (ref "R48")
      (value "1K 1%")
      (footprint "eagle-import:0603")
      (fields (field (name "LCSC_PART") "C21190"))
      (libsource (lib "eagle-import") (part "1K-1%0603"))
    )
    (comp (ref "R49")
      (value "4.3K 1%")
      (footprint "eagle-import:0201")
      (fields (field (name "LCSC_PART") "C423525"))
      (libsource (lib "eagle-import") (part "4.3K-1%0201"))
    )
    (comp (ref "T1")
      (value "BSS138")
      (footprint "eagle-import:SOT23")
      (libsource (lib "eagle-import") (part "BSS138"))
    )
    (comp (ref "T2")
      (value "BSS138")
      (footprint "eagle-import:SOT23")
      (libsource (lib "eagle-import") (part "BSS138"))
    )
    (comp (ref "C117")
      (value "100nF 25V")
      (footprint "eagle-import:0201")
      (fields (field (name "LCSC_PART") "C76939"))
      (libsource (lib "eagle-import") (part "100NF-25V-0201"))
    )
    (comp (ref "C118")
      (value "100nF 25V")
      (footprint "eagle-import:0201")
      (fields (field (name "LCSC_PART") "C76939"))
      (libsource (lib "eagle-import") (part "100NF-25V-0201"))
    )
    (comp (ref "C119")
      (value "100nF 25V")
      (footprint "eagle-import:0201")
      (fields (field (name "LCSC_PART") "C76939"))
      (libsource (lib "eagle-import") (part "100NF-25V-0201"))
    )
    (comp (ref "C120")
      (value "100nF 25V")
      (footprint "eagle-import:0201")
      (fields (field (name "LCSC_PART") "C76939"))
      (libsource (lib "eagle-import") (part "100NF-25V-0201"))
    )
    (comp (ref "C121")
      (value "100nF 25V")
      (footprint "eagle-import:0201")
      (fields (field (name "LCSC_PART") "C76939"))
      (libsource (lib "eagle-import") (part "100NF-25V-0201"))
    )
    (comp (ref "C122")
      (value "100nF 25V")
      (footprint "eagle-import:0201")
      (fields (field (name "LCSC_PART") "C76939"))
      (libsource (lib "eagle-import") (part "100NF-25V-0201"))
    )
    (comp (ref "C123")
      (value "100nF 25V")
      (footprint "eagle-import:0201")
      (fields (field (name "LCSC_PART") "C76939"))
      (libsource (lib "eagle-import") (part "100NF-25V-0201"))
    )
    (comp (ref "C124")
      (value "100nF 25V")
      (footprint "eagle-import:0201")
      (fields (field (name "LCSC_PART") "C76939"))
      (libsource (lib "eagle-import") (part "100NF-25V-0201"))
    )
    (comp (ref "C125")
      (value "4.7uF 25V")
      (footprint "eagle-import:0402")
      (fields (field (name "LCSC_PART") "C22367824"))
      (libsource (lib "eagle-import") (part "4.7UF-25V0402"))
    )
    (comp (ref "C126")
      (value "4.7uF 25V")
      (footprint "eagle-import:0402")
      (fields (field (name "LCSC_PART") "C22367824"))
      (libsource (lib "eagle-import") (part "4.7UF-25V0402"))
    )
    (comp (ref "C127")
      (value "12pF 50V")
      (footprint "eagle-import:0201")
      (fields (field (name "LCSC_PART") "C50391"))
      (libsource (lib "eagle-import") (part "12PF-50V0201"))
    )
    (comp (ref "C128")
      (value "12pF 50V")
      (footprint "eagle-import:0201")
      (fields (field (name "LCSC_PART") "C50391"))
      (libsource (lib "eagle-import") (part "12PF-50V0201"))
    )
    (comp (ref "C129")
      (value "100nF 25V")
      (footprint "eagle-import:0201")
      (fields (field (name "LCSC_PART") "C76939"))
      (libsource (lib "eagle-import") (part "100NF-25V-0201"))
    )
    (comp (ref "C130")
      (value "100nF 25V")
      (footprint "eagle-import:0201")
      (fields (field (name "LCSC_PART") "C76939"))
      (libsource (lib "eagle-import") (part "100NF-25V-0201"))
    )
    (comp (ref "C131")
      (value "100nF 25V")
      (footprint "eagle-import:0201")
      (fields (field (name "LCSC_PART") "C76939"))
      (libsource (lib "eagle-import") (part "100NF-25V-0201"))
    )
    (comp (ref "C132")
      (value "10uF 50V")
      (footprint "eagle-import:0805")
      (fields (field (name "LCSC_PART") "C440198"))
      (libsource (lib "eagle-import") (part "10UF-50V-0805"))
    )
    (comp (ref "C133")
      (value "100nF 25V")
      (footprint "eagle-import:0201")
      (fields (field (name "LCSC_PART") "C76939"))
      (libsource (lib "eagle-import") (part "100NF-25V-0201"))
    )
    (comp (ref "C134")
      (value "100nF 25V")
      (footprint "eagle-import:0201")
      (fields (field (name "LCSC_PART") "C76939"))
      (libsource (lib "eagle-import") (part "100NF-25V-0201"))
    )
    (comp (ref "C135")
      (value "10uF 50V")
      (footprint "eagle-import:0805")
      (fields (field (name "LCSC_PART") "C440198"))
      (libsource (lib "eagle-import") (part "10UF-50V-0805"))
    )
    (comp (ref "DBGG")
      (value "Green")
      (footprint "eagle-import:LED-0603")
      (fields (field (name "LCSC_PART") "C965804"))
      (libsource (lib "eagle-import") (part "LED-GREENLED-0603"))
    )
    (comp (ref "DBGY")
      (value "Yellow")
      (footprint "eagle-import:LED-0603")
      (fields (field (name "LCSC_PART") "C72038"))
      (libsource (lib "eagle-import") (part "LED-YELLOWLED-0603"))
    )
    (comp (ref "G2R")
      (value "Red")
      (footprint "eagle-import:LED-0603")
      (fields (field (name "LCSC_PART") "C2286"))
      (libsource (lib "eagle-import") (part "LED-REDLED-0603"))
    )
    (comp (ref "IC21")
      (value "RP2040")
      (footprint "eagle-import:QFN56")
      (fields (field (name "LCSC_PART") "C2040"))
      (libsource (lib "eagle-import") (part "RP2040"))
    )
    (comp (ref "IC22")
      (value "W25Q128JVP")
      (footprint "eagle-import:SON127P600X500X75-8N")
      (libsource (lib "eagle-import") (part "W25Q128JVP"))
    )
    (comp (ref "IC23")
      (value "74AUP1T17GWH")
      (footprint "eagle-import:SOT353-1")
      (fields (field (name "LCSC_PART") "C545951"))
      (libsource (lib "eagle-import") (part "74AUP1T17GW"))
    )
    (comp (ref "IC24")
      (value "74AUP1T17GWH")
      (footprint "eagle-import:SOT353-1")
      (fields (field (name "LCSC_PART") "C545951"))
      (libsource (lib "eagle-import") (part "74AUP1T17GW"))
    )
    (comp (ref "IC25")
      (value "MIC5504-3.3YM5")
      (footprint "eagle-import:SOT23-5")
      (fields (field (name "LCSC_PART") "C41348078"))
      (libsource (lib "eagle-import") (part "ds_ic_vreg_MIC5504-3.3YM5-TR"))
    )
    (comp (ref "J3")
      (value "JUMPER-3")
      (footprint "eagle-import:JUMPER-3")
      (libsource (lib "eagle-import") (part "JUMPER-3"))
    )
    (comp (ref "R50")
      (value "1K 1%")
      (footprint "eagle-import:0201")
      (fields (field (name "LCSC_PART") "C270365"))
      (libsource (lib "eagle-import") (part "1K-1%0201"))
    )
    (comp (ref "R51")
      (value "27R 1%")
      (footprint "eagle-import:0201")
      (fields (field (name "LCSC_PART") "C473051"))
      (libsource (lib "eagle-import") (part "27R-1%0201"))
    )
    (comp (ref "R52")
      (value "27R 1%")
      (footprint "eagle-import:0201")
      (fields (field (name "LCSC_PART") "C473051"))
      (libsource (lib "eagle-import") (part "27R-1%0201"))
    )
    (comp (ref "R53")
      (value "1K 1%")
      (footprint "eagle-import:0201")
      (fields (field (name "LCSC_PART") "C270365"))
      (libsource (lib "eagle-import") (part "1K-1%0201"))
    )
    (comp (ref "R54")
      (value "1K 1%")
      (footprint "eagle-import:0402")
      (fields (field (name "LCSC_PART") "C11702"))
      (libsource (lib "eagle-import") (part "1K-1%0402"))
    )
    (comp (ref "R55")
      (value "1K 1%")
      (footprint "eagle-import:0402")
      (fields (field (name "LCSC_PART") "C11702"))
      (libsource (lib "eagle-import") (part "1K-1%0402"))
    )
    (comp (ref "R56")
      (value "1K 1%")
      (footprint "eagle-import:0402")
      (fields (field (name "LCSC_PART") "C11702"))
      (libsource (lib "eagle-import") (part "1K-1%0402"))
    )
    (comp (ref "R57")
      (value "1K 1%")
      (footprint "eagle-import:0402")
      (fields (field (name "LCSC_PART") "C11702"))
      (libsource (lib "eagle-import") (part "1K-1%0402"))
    )
    (comp (ref "R58")
      (value "1K 1%")
      (footprint "eagle-import:0402")
      (fields (field (name "LCSC_PART") "C11702"))
      (libsource (lib "eagle-import") (part "1K-1%0402"))
    )
    (comp (ref "R59")
      (value "100R 1%")
      (footprint "eagle-import:0201")
      (fields (field (name "LCSC_PART") "C270366"))
      (libsource (lib "eagle-import") (part "100R-1%0201"))
    )
    (comp (ref "R60")
      (value "100R 1%")
      (footprint "eagle-import:0201")
      (fields (field (name "LCSC_PART") "C270366"))
      (libsource (lib "eagle-import") (part "100R-1%0201"))
    )
    (comp (ref "R61")
      (value "100R 1%")
      (footprint "eagle-import:0201")
      (fields (field (name "LCSC_PART") "C270366"))
      (libsource (lib "eagle-import") (part "100R-1%0201"))
    )
    (comp (ref "R62")
      (value "100R 1%")
      (footprint "eagle-import:0201")
      (fields (field (name "LCSC_PART") "C270366"))
      (libsource (lib "eagle-import") (part "100R-1%0201"))
    )
    (comp (ref "R63")
      (value "100R 1%")
      (footprint "eagle-import:0201")
      (fields (field (name "LCSC_PART") "C270366"))
      (libsource (lib "eagle-import") (part "100R-1%0201"))
    )
    (comp (ref "R64")
      (value "100R 1%")
      (footprint "eagle-import:0201")
      (fields (field (name "LCSC_PART") "C270366"))
      (libsource (lib "eagle-import") (part "100R-1%0201"))
    )
    (comp (ref "R65")
      (value "10K 1%")
      (footprint "eagle-import:0201")
      (fields (field (name "LCSC_PART") "C473048"))
      (libsource (lib "eagle-import") (part "10K-1%0201"))
    )
    (comp (ref "RPDBUG")
      (value "SM03B-SRSS-TB")
      (footprint "eagle-import:SM03B-SRSS-TB")
      (fields (field (name "LCSC_PART") "C160403"))
      (libsource (lib "eagle-import") (part "SM03B-SRSS-TB"))
    )
    (comp (ref "RPUART")
      (value "SM03B-SRSS-TB")
      (footprint "eagle-import:SM03B-SRSS-TB")
      (fields (field (name "LCSC_PART") "C160403"))
      (libsource (lib "eagle-import") (part "SM03B-SRSS-TB"))
    )
    (comp (ref "SW1")
      (value "B3U-1000P")
      (footprint "eagle-import:B3U-1000P")
      (fields (field (name "LCSC_PART") "C231329"))
      (libsource (lib "eagle-import") (part "B3U-1000P"))
    )
    (comp (ref "SW2")
      (value "B3U-1000P")
      (footprint "eagle-import:B3U-1000P")
      (fields (field (name "LCSC_PART") "C231329"))
      (libsource (lib "eagle-import") (part "B3U-1000P"))
    )
    (comp (ref "UARG")
      (value "Green")
      (footprint "eagle-import:LED-0603")
      (fields (field (name "LCSC_PART") "C965804"))
      (libsource (lib "eagle-import") (part "LED-GREENLED-0603"))
    )
    (comp (ref "UARY")
      (value "Yellow")
      (footprint "eagle-import:LED-0603")
      (fields (field (name "LCSC_PART") "C72038"))
      (libsource (lib "eagle-import") (part "LED-YELLOWLED-0603"))
    )
    (comp (ref "X4")
      (value "12MHz")
      (footprint "eagle-import:WE-XTAL_CFPX-180")
      (fields (field (name "TOLERANCE") "±20ppm"))
      (libsource (lib "eagle-import") (part "WE-XTAL_CFPX-180_830055295"))
    )
    (comp (ref "C65")
      (value "1uF 16V")
      (footprint "eagle-import:0201")
      (fields (field (name "LCSC_PART") "C307385"))
      (libsource (lib "eagle-import") (part "1UF-16V0201"))
    )
    (comp (ref "C66")
      (value "100nF 25V")
      (footprint "eagle-import:0201")
      (fields (field (name "LCSC_PART") "C76939"))
      (libsource (lib "eagle-import") (part "100NF-25V-0201"))
    )
    (comp (ref "C67")
      (value "100nF 25V")
      (footprint "eagle-import:0201")
      (fields (field (name "LCSC_PART") "C76939"))
      (libsource (lib "eagle-import") (part "100NF-25V-0201"))
    )
    (comp (ref "C68")
      (value "100nF 25V")
      (footprint "eagle-import:0201")
      (fields (field (name "LCSC_PART") "C76939"))
      (libsource (lib "eagle-import") (part "100NF-25V-0201"))
    )
    (comp (ref "C69")
      (value "100nF 25V")
      (footprint "eagle-import:0201")
      (fields (field (name "LCSC_PART") "C76939"))
      (libsource (lib "eagle-import") (part "100NF-25V-0201"))
    )
    (comp (ref "C70")
      (value "100nF 25V")
      (footprint "eagle-import:0201")
      (fields (field (name "LCSC_PART") "C76939"))
      (libsource (lib "eagle-import") (part "100NF-25V-0201"))
    )
    (comp (ref "C71")
      (value "100nF 25V")
      (footprint "eagle-import:0201")
      (fields (field (name "LCSC_PART") "C76939"))
      (libsource (lib "eagle-import") (part "100NF-25V-0201"))
    )
    (comp (ref "C72")
      (value "100nF 25V")
      (footprint "eagle-import:0201")
      (fields (field (name "LCSC_PART") "C76939"))
      (libsource (lib "eagle-import") (part "100NF-25V-0201"))
    )
    (comp (ref "C73")
      (value "100nF 25V")
      (footprint "eagle-import:0201")
      (fields (field (name "LCSC_PART") "C76939"))
      (libsource (lib "eagle-import") (part "100NF-25V-0201"))
    )
    (comp (ref "C74")
      (value "100nF 25V")
      (footprint "eagle-import:0201")
      (fields (field (name "LCSC_PART") "C76939"))
      (libsource (lib "eagle-import") (part "100NF-25V-0201"))
    )
    (comp (ref "C75")
      (value "12pF 50V")
      (footprint "eagle-import:0201")
      (fields (field (name "LCSC_PART") "C50391"))
      (libsource (lib "eagle-import") (part "12PF-50V0201"))
    )
    (comp (ref "C76")
      (value "12pF 50V")
      (footprint "eagle-import:0201")
      (fields (field (name "LCSC_PART") "C50391"))
      (libsource (lib "eagle-import") (part "12PF-50V0201"))
    )
    (comp (ref "C77")
      (value "100nF 25V")
      (footprint "eagle-import:0201")
      (fields (field (name "LCSC_PART") "C76939"))
      (libsource (lib "eagle-import") (part "100NF-25V-0201"))
    )
    (comp (ref "C78")
      (value "100nF 25V")
      (footprint "eagle-import:0201")
      (fields (field (name "LCSC_PART") "C76939"))
      (libsource (lib "eagle-import") (part "100NF-25V-0201"))
    )
    (comp (ref "C79")
      (value "100nF 25V")
      (footprint "eagle-import:0201")
      (fields (field (name "LCSC_PART") "C76939"))
      (libsource (lib "eagle-import") (part "100NF-25V-0201"))
    )
    (comp (ref "C80")
      (value "10uF 50V")
      (footprint "eagle-import:0805")
      (fields (field (name "LCSC_PART") "C440198"))
      (libsource (lib "eagle-import") (part "10UF-50V-0805"))
    )
    (comp (ref "C81")
      (value "10uF 50V")
      (footprint "eagle-import:0805")
      (fields (field (name "LCSC_PART") "C440198"))
      (libsource (lib "eagle-import") (part "10UF-50V-0805"))
    )
    (comp (ref "C82")
      (value "100nF 25V")
      (footprint "eagle-import:0201")
      (fields (field (name "LCSC_PART") "C76939"))
      (libsource (lib "eagle-import") (part "100NF-25V-0201"))
    )
    (comp (ref "C83")
      (value "100nF 25V")
      (footprint "eagle-import:0201")
      (fields (field (name "LCSC_PART") "C76939"))
      (libsource (lib "eagle-import") (part "100NF-25V-0201"))
    )
    (comp (ref "D8")
      (value "1N4148SOD-123")
      (footprint "eagle-import:SOD-123FL")
      (libsource (lib "eagle-import") (part "DIODE_SOD-123FL"))
    )
    (comp (ref "D10")
      (value "Red")
      (footprint "eagle-import:LED-0603")
      (fields (field (name "LCSC_PART") "C2286"))
      (libsource (lib "eagle-import") (part "LED-REDLED-0603"))
    )
    (comp (ref "IC6")
      (value "MIC5504-3.3YM5-TR")
      (footprint "eagle-import:SOT23-5")
      (libsource (lib "eagle-import") (part "MIC5504-3.3YM5-TR"))
    )
    (comp (ref "IC7")
      (value "SN74LVC541ARGYR")
      (footprint "eagle-import:QFN50P350X450X100-25T305X205N")
      (libsource (lib "eagle-import") (part "74LVC541A"))
    )
    (comp (ref "IC8")
      (value "CAT24C256HU4IGT3")
      (footprint "eagle-import:SON50P300X200X50-9T130X140N")
      (libsource (lib "eagle-import") (part "CAT24C256-HU4"))
    )
    (comp (ref "IC9")
      (value "CY7C68013A-56LTXC")
      (footprint "eagle-import:QFN50P800X800X100-57T665")
      (libsource (lib "eagle-import") (part "CY7C68013A-56QFNLFXC"))
    )
    (comp (ref "IC10")
      (value "SN74LVC541ARGYR")
      (footprint "eagle-import:QFN50P350X450X100-25T305X205N")
      (libsource (lib "eagle-import") (part "74LVC541A"))
    )
    (comp (ref "LA")
      (value "62702021721")
      (footprint "eagle-import:62702021721")
      (libsource (lib "eagle-import") (part "6270XX21721_62702021721"))
    )
    (comp (ref "R19")
      (value "100K 1%")
      (footprint "eagle-import:0201")
      (fields (field (name "LCSC_PART") "C270364"))
      (libsource (lib "eagle-import") (part "100K-1%0201"))
    )
    (comp (ref "R20")
      (value "3.3K 1%")
      (footprint "eagle-import:0201")
      (fields (field (name "LCSC_PART") "C270350"))
      (libsource (lib "eagle-import") (part "3.3K-1%0201"))
    )
    (comp (ref "R21")
      (value "3.3K 1%")
      (footprint "eagle-import:0201")
      (fields (field (name "LCSC_PART") "C270350"))
      (libsource (lib "eagle-import") (part "3.3K-1%0201"))
    )
    (comp (ref "R22")
      (value "1K 1%")
      (footprint "eagle-import:0402")
      (fields (field (name "LCSC_PART") "C11702"))
      (libsource (lib "eagle-import") (part "1K-1%0402"))
    )
    (comp (ref "RN1")
      (value "100R 1%")
      (footprint "eagle-import:0603X4-1206")
      (fields (field (name "LCSC_PART") "C136838"))
      (libsource (lib "eagle-import") (part "100R-1%_ARRAY0603X4-1206"))
    )
    (comp (ref "RN2")
      (value "100R 1%")
      (footprint "eagle-import:0603X4-1206")
      (fields (field (name "LCSC_PART") "C136838"))
      (libsource (lib "eagle-import") (part "100R-1%_ARRAY0603X4-1206"))
    )
    (comp (ref "RN3")
      (value "100R 1%")
      (footprint "eagle-import:0603X4-1206")
      (fields (field (name "LCSC_PART") "C136838"))
      (libsource (lib "eagle-import") (part "100R-1%_ARRAY0603X4-1206"))
    )
    (comp (ref "RN4")
      (value "100R 1%")
      (footprint "eagle-import:0603X4-1206")
      (fields (field (name "LCSC_PART") "C136838"))
      (libsource (lib "eagle-import") (part "100R-1%_ARRAY0603X4-1206"))
    )
    (comp (ref "RN5")
      (value "100K 1%")
      (footprint "eagle-import:0603X4-1206")
      (fields (field (name "LCSC_PART") "C110374"))
      (libsource (lib "eagle-import") (part "100K-1%_ARRAY0603X4-1206"))
    )
    (comp (ref "RN6")
      (value "100K 1%")
      (footprint "eagle-import:0603X4-1206")
      (fields (field (name "LCSC_PART") "C110374"))
      (libsource (lib "eagle-import") (part "100K-1%_ARRAY0603X4-1206"))
    )
    (comp (ref "RN7")
      (value "100R 1%")
      (footprint "eagle-import:0603X4-1206")
      (fields (field (name "LCSC_PART") "C136838"))
      (libsource (lib "eagle-import") (part "100R-1%_ARRAY0603X4-1206"))
    )
    (comp (ref "RN8")
      (value "100R 1%")
      (footprint "eagle-import:0603X4-1206")
      (fields (field (name "LCSC_PART") "C136838"))
      (libsource (lib "eagle-import") (part "100R-1%_ARRAY0603X4-1206"))
    )
    (comp (ref "RN9")
      (value "100R 1%")
      (footprint "eagle-import:0603X4-1206")
      (fields (field (name "LCSC_PART") "C136838"))
      (libsource (lib "eagle-import") (part "100R-1%_ARRAY0603X4-1206"))
    )
    (comp (ref "RN10")
      (value "100R 1%")
      (footprint "eagle-import:0603X4-1206")
      (fields (field (name "LCSC_PART") "C136838"))
      (libsource (lib "eagle-import") (part "100R-1%_ARRAY0603X4-1206"))
    )
    (comp (ref "RN11")
      (value "100K 1%")
      (footprint "eagle-import:0603X4-1206")
      (fields (field (name "LCSC_PART") "C110374"))
      (libsource (lib "eagle-import") (part "100K-1%_ARRAY0603X4-1206"))
    )
    (comp (ref "RN12")
      (value "100K 1%")
      (footprint "eagle-import:0603X4-1206")
      (fields (field (name "LCSC_PART") "C110374"))
      (libsource (lib "eagle-import") (part "100K-1%_ARRAY0603X4-1206"))
    )
    (comp (ref "X2")
      (value "24MHz")
      (footprint "eagle-import:WE-XTAL_CFPX-180")
      (fields (field (name "TOLERANCE") "±10ppm"))
      (libsource (lib "eagle-import") (part "WE-XTAL_CFPX-180_830058149"))
    )
    (comp (ref "C45")
      (value "22uF 25V")
      (footprint "eagle-import:0805")
      (fields (field (name "LCSC_PART") "C45783"))
      (libsource (lib "eagle-import") (part "22UF-25V-0805"))
    )
    (comp (ref "C46")
      (value "10uF 16V")
      (footprint "eagle-import:0805")
      (fields (field (name "LCSC_PART") "C1713"))
      (libsource (lib "eagle-import") (part "10UF-16V-0805"))
    )
    (comp (ref "C47")
      (value "10nF 50V")
      (footprint "eagle-import:0805")
      (fields (field (name "LCSC_PART") "C1710"))
      (libsource (lib "eagle-import") (part "10NF-50V-0805"))
    )
    (comp (ref "C48")
      (value "10nF 16V")
      (footprint "eagle-import:0201")
      (fields (field (name "LCSC_PART") "C272853"))
      (libsource (lib "eagle-import") (part "10NF-16V-0201"))
    )
    (comp (ref "C49")
      (value "DNI")
      (footprint "eagle-import:0201")
      (libsource (lib "eagle-import") (part "C-0201"))
    )
    (comp (ref "C50")
      (value "10nF 25V")
      (footprint "eagle-import:0402")
      (fields (field (name "LCSC_PART") "C284987"))
      (libsource (lib "eagle-import") (part "10NF-25V-0402"))
    )
    (comp (ref "C51")
      (value "10nF 50V")
      (footprint "eagle-import:0805")
      (fields (field (name "LCSC_PART") "C1710"))
      (libsource (lib "eagle-import") (part "10NF-50V-0805"))
    )
    (comp (ref "C52")
      (value "330uF 25V")
      (footprint "eagle-import:6.3X7.7(DXL)")
      (fields (field (name "LCSC_PART") "C2980171"))
      (libsource (lib "eagle-import") (part "330UF-25V6.3X7.7(DXL)"))
    )
    (comp (ref "C53")
      (value "22uF 16V")
      (footprint "eagle-import:0805")
      (fields (field (name "LCSC_PART") "C76637"))
      (libsource (lib "eagle-import") (part "22UF-16V-0805"))
    )
    (comp (ref "C54")
      (value "100nF 16V")
      (footprint "eagle-import:0201")
      (fields (field (name "LCSC_PART") "C2846674"))
      (libsource (lib "eagle-import") (part "100NF-16V-0201"))
    )
    (comp (ref "C55")
      (value "100nF 16V")
      (footprint "eagle-import:0201")
      (fields (field (name "LCSC_PART") "C2846674"))
      (libsource (lib "eagle-import") (part "100NF-16V-0201"))
    )
    (comp (ref "C56")
      (value "100nF 16V")
      (footprint "eagle-import:0201")
      (fields (field (name "LCSC_PART") "C2846674"))
      (libsource (lib "eagle-import") (part "100NF-16V-0201"))
    )
    (comp (ref "C57")
      (value "100nF 16V")
      (footprint "eagle-import:0201")
      (fields (field (name "LCSC_PART") "C2846674"))
      (libsource (lib "eagle-import") (part "100NF-16V-0201"))
    )
    (comp (ref "C58")
      (value "100nF 16V")
      (footprint "eagle-import:0201")
      (fields (field (name "LCSC_PART") "C2846674"))
      (libsource (lib "eagle-import") (part "100NF-16V-0201"))
    )
    (comp (ref "C59")
      (value "150uF 35V")
      (footprint "eagle-import:6.3X5.5(DXL)")
      (fields (field (name "LCSC_PART") "C3032176"))
      (libsource (lib "eagle-import") (part "150UF-35V-6.3X5.5"))
    )
    (comp (ref "C60")
      (value "150uF 35V")
      (footprint "eagle-import:6.3X5.5(DXL)")
      (fields (field (name "LCSC_PART") "C3032176"))
      (libsource (lib "eagle-import") (part "150UF-35V-6.3X5.5"))
    )
    (comp (ref "C61")
      (value "100nF 16V")
      (footprint "eagle-import:0201")
      (fields (field (name "LCSC_PART") "C2846674"))
      (libsource (lib "eagle-import") (part "100NF-16V-0201"))
    )
    (comp (ref "C62")
      (value "100nF 16V")
      (footprint "eagle-import:0201")
      (fields (field (name "LCSC_PART") "C2846674"))
      (libsource (lib "eagle-import") (part "100NF-16V-0201"))
    )
    (comp (ref "C63")
      (value "150uF 35V")
      (footprint "eagle-import:6.3X5.5(DXL)")
      (fields (field (name "LCSC_PART") "C3032176"))
      (libsource (lib "eagle-import") (part "150UF-35V-6.3X5.5"))
    )
    (comp (ref "C64")
      (value "150uF 35V")
      (footprint "eagle-import:6.3X5.5(DXL)")
      (fields (field (name "LCSC_PART") "C3032176"))
      (libsource (lib "eagle-import") (part "150UF-35V-6.3X5.5"))
    )
    (comp (ref "D9")
      (value "MBRS540T3G")
      (footprint "eagle-import:SMC")
      (libsource (lib "eagle-import") (part "DIODE-SMC"))
    )
    (comp (ref "IC2")
      (value "TPS5450DDAR")
      (footprint "eagle-import:8-POWERSOIC")
      (fields (field (name "LCSC_PART") "C114425"))
      (libsource (lib "eagle-import") (part "TPS5450"))
    )
    (comp (ref "IC3")
      (value "TPS74401RGWT")
      (footprint "eagle-import:VQFN20-5X5")
      (fields (field (name "LCSC_PART") "C840108"))
      (libsource (lib "eagle-import") (part "TPS74401RGWT"))
    )
    (comp (ref "IC4")
      (value "TPS2560DRCR")
      (footprint "eagle-import:VSON10-3X3")
      (fields
        (field (name "LCSC_PART") "C140304")
        (field (name "COPYRIGHT") "Copyright (C) 2025 Ultra Librarian. All rights reserved.")
      )
      (libsource (lib "eagle-import") (part "TPS2560DRCR"))
    )
    (comp (ref "IC5")
      (value "TPS2560DRCR")
      (footprint "eagle-import:VSON10-3X3")
      (fields
        (field (name "LCSC_PART") "C140304")
        (field (name "COPYRIGHT") "Copyright (C) 2025 Ultra Librarian. All rights reserved.")
      )
      (libsource (lib "eagle-import") (part "TPS2560DRCR"))
    )
    (comp (ref "L1")
      (value "15uH")
      (footprint "eagle-import:L-10X10")
      (fields (field (name "LCSC_PART") "C2847564"))
      (libsource (lib "eagle-import") (part "15UHL-10X10"))
    )
    (comp (ref "PGOOD3")
      (value "Green")
      (footprint "eagle-import:LED-0603")
      (fields (field (name "LCSC_PART") "C965804"))
      (libsource (lib "eagle-import") (part "LED-GREENLED-0603"))
    )
    (comp (ref "PGOOD5")
      (value "Green")
      (footprint "eagle-import:LED-0603")
      (fields (field (name "LCSC_PART") "C965804"))
      (libsource (lib "eagle-import") (part "LED-GREENLED-0603"))
    )
    (comp (ref "PORT1")
      (value "Red")
      (footprint "eagle-import:LED-0603")
      (fields (field (name "LCSC_PART") "C2286"))
      (libsource (lib "eagle-import") (part "LED-REDLED-0603"))
    )
    (comp (ref "PORT2")
      (value "Red")
      (footprint "eagle-import:LED-0603")
      (fields (field (name "LCSC_PART") "C2286"))
      (libsource (lib "eagle-import") (part "LED-REDLED-0603"))
    )
    (comp (ref "PORT3")
      (value "Red")
      (footprint "eagle-import:LED-0603")
      (fields (field (name "LCSC_PART") "C2286"))
      (libsource (lib "eagle-import") (part "LED-REDLED-0603"))
    )
    (comp (ref "PORT4")
      (value "Red")
      (footprint "eagle-import:LED-0603")
      (fields (field (name "LCSC_PART") "C2286"))
      (libsource (lib "eagle-import") (part "LED-REDLED-0603"))
    )
    (comp (ref "R5")
      (value "1K 1%")
      (footprint "eagle-import:0402")
      (fields (field (name "LCSC_PART") "C11702"))
      (libsource (lib "eagle-import") (part "1K-1%0402"))
    )
    (comp (ref "R6")
      (value "4.7K 1%")
      (footprint "eagle-import:0201")
      (fields (field (name "LCSC_PART") "C270346"))
      (libsource (lib "eagle-import") (part "4.7K-1%0201"))
    )
    (comp (ref "R7")
      (value "10K 1%")
      (footprint "eagle-import:0402")
      (fields (field (name "LCSC_PART") "C25744"))
      (libsource (lib "eagle-import") (part "10K-1%0402"))
    )
    (comp (ref "R8")
      (value "3.16K 1%")
      (footprint "eagle-import:0402")
      (fields (field (name "LCSC_PART") "C2933087"))
      (libsource (lib "eagle-import") (part "3.16K-1%0402"))
    )
    (comp (ref "R9")
      (value "10K 1%")
      (footprint "eagle-import:0201")
      (fields (field (name "LCSC_PART") "C473048"))
      (libsource (lib "eagle-import") (part "10K-1%0201"))
    )
    (comp (ref "R10")
      (value "1.37K 1%")
      (footprint "eagle-import:0201")
      (fields (field (name "LCSC_PART") "C166356"))
      (libsource (lib "eagle-import") (part "1.37K-1%0201"))
    )
    (comp (ref "R11")
      (value "4.42K 1%")
      (footprint "eagle-import:0201")
      (fields (field (name "LCSC_PART") "C423515"))
      (libsource (lib "eagle-import") (part "4.42K-1%0201"))
    )
    (comp (ref "R12")
      (value "1K 1%")
      (footprint "eagle-import:0402")
      (fields (field (name "LCSC_PART") "C11702"))
      (libsource (lib "eagle-import") (part "1K-1%0402"))
    )
    (comp (ref "R13")
      (value "30.9K 1%")
      (footprint "eagle-import:0201")
      (fields (field (name "LCSC_PART") "C364366"))
      (libsource (lib "eagle-import") (part "30.9K-1%0201"))
    )
    (comp (ref "R14")
      (value "30.9K 1%")
      (footprint "eagle-import:0201")
      (fields (field (name "LCSC_PART") "C364366"))
      (libsource (lib "eagle-import") (part "30.9K-1%0201"))
    )
    (comp (ref "R15")
      (value "1K 1%")
      (footprint "eagle-import:0402")
      (fields (field (name "LCSC_PART") "C11702"))
      (libsource (lib "eagle-import") (part "1K-1%0402"))
    )
    (comp (ref "R16")
      (value "1K 1%")
      (footprint "eagle-import:0402")
      (fields (field (name "LCSC_PART") "C11702"))
      (libsource (lib "eagle-import") (part "1K-1%0402"))
    )
    (comp (ref "R17")
      (value "1K 1%")
      (footprint "eagle-import:0402")
      (fields (field (name "LCSC_PART") "C11702"))
      (libsource (lib "eagle-import") (part "1K-1%0402"))
    )
    (comp (ref "R18")
      (value "1K 1%")
      (footprint "eagle-import:0402")
      (fields (field (name "LCSC_PART") "C11702"))
      (libsource (lib "eagle-import") (part "1K-1%0402"))
    )
    (comp (ref "C84")
      (value "100nF 25V")
      (footprint "eagle-import:0402")
      (fields (field (name "LCSC_PART") "C56392"))
      (libsource (lib "eagle-import") (part "100NF-25V-0402"))
    )
    (comp (ref "C85")
      (value "27pF 50V")
      (footprint "eagle-import:0201")
      (fields (field (name "LCSC_PART") "C85899"))
      (libsource (lib "eagle-import") (part "27PF-50V0201"))
    )
    (comp (ref "C86")
      (value "27pF 50V")
      (footprint "eagle-import:0201")
      (fields (field (name "LCSC_PART") "C85899"))
      (libsource (lib "eagle-import") (part "27PF-50V0201"))
    )
    (comp (ref "C87")
      (value "100nF 25V")
      (footprint "eagle-import:0201")
      (fields (field (name "LCSC_PART") "C76939"))
      (libsource (lib "eagle-import") (part "100NF-25V-0201"))
    )
    (comp (ref "C88")
      (value "100nF 25V")
      (footprint "eagle-import:0201")
      (fields (field (name "LCSC_PART") "C76939"))
      (libsource (lib "eagle-import") (part "100NF-25V-0201"))
    )
    (comp (ref "C89")
      (value "100nF 25V")
      (footprint "eagle-import:0201")
      (fields (field (name "LCSC_PART") "C76939"))
      (libsource (lib "eagle-import") (part "100NF-25V-0201"))
    )
    (comp (ref "C90")
      (value "100nF 25V")
      (footprint "eagle-import:0201")
      (fields (field (name "LCSC_PART") "C76939"))
      (libsource (lib "eagle-import") (part "100NF-25V-0201"))
    )
    (comp (ref "C91")
      (value "100nF 25V")
      (footprint "eagle-import:0201")
      (fields (field (name "LCSC_PART") "C76939"))
      (libsource (lib "eagle-import") (part "100NF-25V-0201"))
    )
    (comp (ref "C92")
      (value "100nF 25V")
      (footprint "eagle-import:0201")
      (fields (field (name "LCSC_PART") "C76939"))
      (libsource (lib "eagle-import") (part "100NF-25V-0201"))
    )
    (comp (ref "C93")
      (value "4.7uF 25V")
      (footprint "eagle-import:0402")
      (fields (field (name "LCSC_PART") "C22367824"))
      (libsource (lib "eagle-import") (part "4.7UF-25V0402"))
    )
    (comp (ref "C94")
      (value "4.7uF 25V")
      (footprint "eagle-import:0402")
      (fields (field (name "LCSC_PART") "C22367824"))
      (libsource (lib "eagle-import") (part "4.7UF-25V0402"))
    )
    (comp (ref "C95")
      (value "100nF 25V")
      (footprint "eagle-import:0201")
      (fields (field (name "LCSC_PART") "C76939"))
      (libsource (lib "eagle-import") (part "100NF-25V-0201"))
    )
    (comp (ref "C96")
      (value "100nF 25V")
      (footprint "eagle-import:0201")
      (fields (field (name "LCSC_PART") "C76939"))
      (libsource (lib "eagle-import") (part "100NF-25V-0201"))
    )
    (comp (ref "C97")
      (value "100nF 25V")
      (footprint "eagle-import:0201")
      (fields (field (name "LCSC_PART") "C76939"))
      (libsource (lib "eagle-import") (part "100NF-25V-0201"))
    )
    (comp (ref "C98")
      (value "100nF 25V")
      (footprint "eagle-import:0201")
      (fields (field (name "LCSC_PART") "C76939"))
      (libsource (lib "eagle-import") (part "100NF-25V-0201"))
    )
    (comp (ref "C99")
      (value "4.7uF 25V")
      (footprint "eagle-import:0402")
      (fields (field (name "LCSC_PART") "C22367824"))
      (libsource (lib "eagle-import") (part "4.7UF-25V0402"))
    )
    (comp (ref "C100")
      (value "100nF 25V")
      (footprint "eagle-import:0201")
      (fields (field (name "LCSC_PART") "C76939"))
      (libsource (lib "eagle-import") (part "100NF-25V-0201"))
    )
    (comp (ref "C101")
      (value "10uF 16V")
      (footprint "eagle-import:0603")
      (fields (field (name "LCSC_PART") "C92487"))
      (libsource (lib "eagle-import") (part "10UF-16V-0603"))
    )
    (comp (ref "C102")
      (value "100nF 25V")
      (footprint "eagle-import:0201")
      (fields (field (name "LCSC_PART") "C76939"))
      (libsource (lib "eagle-import") (part "100NF-25V-0201"))
    )
    (comp (ref "C103")
      (value "10uF 16V")
      (footprint "eagle-import:0603")
      (fields (field (name "LCSC_PART") "C92487"))
      (libsource (lib "eagle-import") (part "10UF-16V-0603"))
    )
    (comp (ref "IC11")
      (value "FT4232HL")
      (footprint "eagle-import:LQFP64-10X10")
      (fields (field (name "LCSC_PART") "C56742"))
      (libsource (lib "eagle-import") (part "FT4232HL"))
    )
    (comp (ref "IC12")
      (value "93LC56BT-I/OT")
      (footprint "eagle-import:SOT95P280X145-6N")
      (fields (field (name "LCSC_PART") "C190271"))
      (libsource (lib "eagle-import") (part "93LC56BT-I/OT"))
    )
    (comp (ref "IC13")
      (value "MIC5504-3.3YM5")
      (footprint "eagle-import:SOT23-5")
      (fields (field (name "LCSC_PART") "C41348078"))
      (libsource (lib "eagle-import") (part "ds_ic_vreg_MIC5504-3.3YM5-TR"))
    )
    (comp (ref "J7")
      (value "JUMPER-NO")
      (footprint "eagle-import:J-0402-NO")
      (libsource (lib "eagle-import") (part "JUMPER-NO"))
    )
    (comp (ref "JTAG")
      (value "62701021721")
      (footprint "eagle-import:62701021721")
      (libsource (lib "eagle-import") (part "6270XX21721_62701021721"))
    )
    (comp (ref "R23")
      (value "2K 1%")
      (footprint "eagle-import:0201")
      (fields (field (name "LCSC_PART") "C270358"))
      (libsource (lib "eagle-import") (part "2K-1%0201"))
    )
    (comp (ref "R24")
      (value "10K 1%")
      (footprint "eagle-import:0201")
      (fields (field (name "LCSC_PART") "C473048"))
      (libsource (lib "eagle-import") (part "10K-1%0201"))
    )
    (comp (ref "R25")
      (value "10K 1%")
      (footprint "eagle-import:0201")
      (fields (field (name "LCSC_PART") "C473048"))
      (libsource (lib "eagle-import") (part "10K-1%0201"))
    )
    (comp (ref "R26")
      (value "10K 1%")
      (footprint "eagle-import:0201")
      (fields (field (name "LCSC_PART") "C473048"))
      (libsource (lib "eagle-import") (part "10K-1%0201"))
    )
    (comp (ref "R27")
      (value "4.7K 1%")
      (footprint "eagle-import:0201")
      (fields (field (name "LCSC_PART") "C270346"))
      (libsource (lib "eagle-import") (part "4.7K-1%0201"))
    )
    (comp (ref "R28")
      (value "10K 1%")
      (footprint "eagle-import:0201")
      (fields (field (name "LCSC_PART") "C473048"))
      (libsource (lib "eagle-import") (part "10K-1%0201"))
    )
    (comp (ref "R29")
      (value "12K 1%")
      (footprint "eagle-import:0201")
      (fields (field (name "LCSC_PART") "C270363"))
      (libsource (lib "eagle-import") (part "12K-1%0201"))
    )
    (comp (ref "R30")
      (value "1K 1%")
      (footprint "eagle-import:0201")
      (fields (field (name "LCSC_PART") "C270365"))
      (libsource (lib "eagle-import") (part "1K-1%0201"))
    )
    (comp (ref "R31")
      (value "4.7K 1%")
      (footprint "eagle-import:0201")
      (fields (field (name "LCSC_PART") "C270346"))
      (libsource (lib "eagle-import") (part "4.7K-1%0201"))
    )
    (comp (ref "R32")
      (value "4.7K 1%")
      (footprint "eagle-import:0201")
      (fields (field (name "LCSC_PART") "C270346"))
      (libsource (lib "eagle-import") (part "4.7K-1%0201"))
    )
    (comp (ref "UART1")
      (value "62731020621")
      (footprint "eagle-import:62731020621")
      (libsource (lib "eagle-import") (part "6273XX20621_62731020621"))
    )
    (comp (ref "UART2")
      (value "62731020621")
      (footprint "eagle-import:62731020621")
      (libsource (lib "eagle-import") (part "6273XX20621_62731020621"))
    )
    (comp (ref "X3")
      (value "12MHz")
      (footprint "eagle-import:WE-XTAL_CFPX-180")
      (fields (field (name "TOLERANCE") "±20ppm"))
      (libsource (lib "eagle-import") (part "WE-XTAL_CFPX-180_830055295"))
    )
    (comp (ref "C17")
      (value "10nF 16V")
      (footprint "eagle-import:0201")
      (fields (field (name "LCSC_PART") "C272853"))
      (libsource (lib "eagle-import") (part "10NF-16V-0201"))
    )
    (comp (ref "C18")
      (value "10nF 16V")
      (footprint "eagle-import:0201")
      (fields (field (name "LCSC_PART") "C272853"))
      (libsource (lib "eagle-import") (part "10NF-16V-0201"))
    )
    (comp (ref "C19")
      (value "10nF 16V")
      (footprint "eagle-import:0201")
      (fields (field (name "LCSC_PART") "C272853"))
      (libsource (lib "eagle-import") (part "10NF-16V-0201"))
    )
    (comp (ref "C20")
      (value "10nF 16V")
      (footprint "eagle-import:0201")
      (fields (field (name "LCSC_PART") "C272853"))
      (libsource (lib "eagle-import") (part "10NF-16V-0201"))
    )
    (comp (ref "C21")
      (value "10nF 16V")
      (footprint "eagle-import:0201")
      (fields (field (name "LCSC_PART") "C272853"))
      (libsource (lib "eagle-import") (part "10NF-16V-0201"))
    )
    (comp (ref "C22")
      (value "10nF 16V")
      (footprint "eagle-import:0201")
      (fields (field (name "LCSC_PART") "C272853"))
      (libsource (lib "eagle-import") (part "10NF-16V-0201"))
    )
    (comp (ref "C23")
      (value "100nF 16V")
      (footprint "eagle-import:0201")
      (fields (field (name "LCSC_PART") "C2846674"))
      (libsource (lib "eagle-import") (part "100NF-16V-0201"))
    )
    (comp (ref "C24")
      (value "10nF 16V")
      (footprint "eagle-import:0201")
      (fields (field (name "LCSC_PART") "C272853"))
      (libsource (lib "eagle-import") (part "10NF-16V-0201"))
    )
    (comp (ref "C25")
      (value "100nF 16V")
      (footprint "eagle-import:0201")
      (fields (field (name "LCSC_PART") "C2846674"))
      (libsource (lib "eagle-import") (part "100NF-16V-0201"))
    )
    (comp (ref "C26")
      (value "10nF 16V")
      (footprint "eagle-import:0201")
      (fields (field (name "LCSC_PART") "C272853"))
      (libsource (lib "eagle-import") (part "10NF-16V-0201"))
    )
    (comp (ref "C27")
      (value "100nF 16V")
      (footprint "eagle-import:0201")
      (fields (field (name "LCSC_PART") "C2846674"))
      (libsource (lib "eagle-import") (part "100NF-16V-0201"))
    )
    (comp (ref "C28")
      (value "10nF 16V")
      (footprint "eagle-import:0201")
      (fields (field (name "LCSC_PART") "C272853"))
      (libsource (lib "eagle-import") (part "10NF-16V-0201"))
    )
    (comp (ref "C29")
      (value "100nF 16V")
      (footprint "eagle-import:0201")
      (fields (field (name "LCSC_PART") "C2846674"))
      (libsource (lib "eagle-import") (part "100NF-16V-0201"))
    )
    (comp (ref "C30")
      (value "10nF 16V")
      (footprint "eagle-import:0201")
      (fields (field (name "LCSC_PART") "C272853"))
      (libsource (lib "eagle-import") (part "10NF-16V-0201"))
    )
    (comp (ref "C31")
      (value "100nF 16V")
      (footprint "eagle-import:0201")
      (fields (field (name "LCSC_PART") "C2846674"))
      (libsource (lib "eagle-import") (part "100NF-16V-0201"))
    )
    (comp (ref "C32")
      (value "10nF 16V")
      (footprint "eagle-import:0201")
      (fields (field (name "LCSC_PART") "C272853"))
      (libsource (lib "eagle-import") (part "10NF-16V-0201"))
    )
    (comp (ref "C33")
      (value "100nF 16V")
      (footprint "eagle-import:0201")
      (fields (field (name "LCSC_PART") "C2846674"))
      (libsource (lib "eagle-import") (part "100NF-16V-0201"))
    )
    (comp (ref "C34")
      (value "10nF 16V")
      (footprint "eagle-import:0201")
      (fields (field (name "LCSC_PART") "C272853"))
      (libsource (lib "eagle-import") (part "10NF-16V-0201"))
    )
    (comp (ref "C35")
      (value "10nF 16V")
      (footprint "eagle-import:0201")
      (fields (field (name "LCSC_PART") "C272853"))
      (libsource (lib "eagle-import") (part "10NF-16V-0201"))
    )
    (comp (ref "C36")
      (value "10nF 16V")
      (footprint "eagle-import:0201")
      (fields (field (name "LCSC_PART") "C272853"))
      (libsource (lib "eagle-import") (part "10NF-16V-0201"))
    )
    (comp (ref "C37")
      (value "10nF 16V")
      (footprint "eagle-import:0201")
      (fields (field (name "LCSC_PART") "C272853"))
      (libsource (lib "eagle-import") (part "10NF-16V-0201"))
    )
    (comp (ref "C38")
      (value "10nF 16V")
      (footprint "eagle-import:0201")
      (fields (field (name "LCSC_PART") "C272853"))
      (libsource (lib "eagle-import") (part "10NF-16V-0201"))
    )
    (comp (ref "C39")
      (value "10nF 16V")
      (footprint "eagle-import:0201")
      (fields (field (name "LCSC_PART") "C272853"))
      (libsource (lib "eagle-import") (part "10NF-16V-0201"))
    )
    (comp (ref "C40")
      (value "100nF 16V")
      (footprint "eagle-import:0201")
      (fields (field (name "LCSC_PART") "C2846674"))
      (libsource (lib "eagle-import") (part "100NF-16V-0201"))
    )
    (comp (ref "C41")
      (value "100nF 16V")
      (footprint "eagle-import:0201")
      (fields (field (name "LCSC_PART") "C2846674"))
      (libsource (lib "eagle-import") (part "100NF-16V-0201"))
    )
    (comp (ref "IC1")
      (value "UPD720201K8-701-BAC-A")
      (footprint "eagle-import:QFN68-8X8")
      (fields (field (name "LCSC_PART") "C355375"))
      (libsource (lib "eagle-import") (part "UPD720201"))
    )
    (comp (ref "R2")
      (value "BLM21PG600SN1")
      (footprint "eagle-import:0603")
      (libsource (lib "eagle-import") (part "R0603"))
    )
    (comp (ref "!PERST")
      (value "TPB1,27")
      (footprint "eagle-import:B1,27")
      (libsource (lib "eagle-import") (part "TPB1,27"))
    )
    (comp (ref "!REQ")
      (value "TPB1,27")
      (footprint "eagle-import:B1,27")
      (libsource (lib "eagle-import") (part "TPB1,27"))
    )
    (comp (ref "!RST")
      (value "TPB1,27")
      (footprint "eagle-import:B1,27")
      (libsource (lib "eagle-import") (part "TPB1,27"))
    )
    (comp (ref "!SMI")
      (value "TPB1,27")
      (footprint "eagle-import:B1,27")
      (libsource (lib "eagle-import") (part "TPB1,27"))
    )
    (comp (ref "C42")
      (value "1uF 16V")
      (footprint "eagle-import:0201")
      (fields (field (name "LCSC_PART") "C307385"))
      (libsource (lib "eagle-import") (part "1UF-16V0201"))
    )
    (comp (ref "C43")
      (value "8pF 50V")
      (footprint "eagle-import:0201")
      (fields (field (name "LCSC_PART") "C161366"))
      (libsource (lib "eagle-import") (part "8PF-50V0201"))
    )
    (comp (ref "C44")
      (value "8pF 50V")
      (footprint "eagle-import:0201")
      (fields (field (name "LCSC_PART") "C161366"))
      (libsource (lib "eagle-import") (part "8PF-50V0201"))
    )
    (comp (ref "D1")
      (value "1SS294")
      (footprint "eagle-import:SOT23")
      (libsource (lib "eagle-import") (part "BAT54"))
    )
    (comp (ref "J4")
      (value "66100511622")
      (footprint "eagle-import:66100511622")
      (libsource (lib "eagle-import") (part "66100511622"))
    )
    (comp (ref "R3")
      (value "10K 1%")
      (footprint "eagle-import:0201")
      (fields (field (name "LCSC_PART") "C473048"))
      (libsource (lib "eagle-import") (part "10K-1%0201"))
    )
    (comp (ref "R4")
      (value "1.6K 1%")
      (footprint "eagle-import:0201")
      (fields (field (name "LCSC_PART") "C6123628"))
      (libsource (lib "eagle-import") (part "1.6K-1%0201"))
    )
    (comp (ref "X1")
      (value "24MHz")
      (footprint "eagle-import:WE-XTAL_CFPX-180")
      (fields (field (name "TOLERANCE") "±10ppm"))
      (libsource (lib "eagle-import") (part "WE-XTAL_CFPX-180_830108207709"))
    )
    (comp (ref "AUX3")
      (value "TPB1,27")
      (footprint "eagle-import:B1,27")
      (libsource (lib "eagle-import") (part "TPB1,27"))
    )
    (comp (ref "C1")
      (value "100nF 25V")
      (footprint "eagle-import:0402")
      (fields (field (name "LCSC_PART") "C56392"))
      (libsource (lib "eagle-import") (part "100NF-25V-0402"))
    )
    (comp (ref "C2")
      (value "100nF 25V")
      (footprint "eagle-import:0402")
      (fields (field (name "LCSC_PART") "C56392"))
      (libsource (lib "eagle-import") (part "100NF-25V-0402"))
    )
    (comp (ref "C3")
      (value "100nF 25V")
      (footprint "eagle-import:0402")
      (fields (field (name "LCSC_PART") "C56392"))
      (libsource (lib "eagle-import") (part "100NF-25V-0402"))
    )
    (comp (ref "C4")
      (value "100nF 25V")
      (footprint "eagle-import:0402")
      (fields (field (name "LCSC_PART") "C56392"))
      (libsource (lib "eagle-import") (part "100NF-25V-0402"))
    )
    (comp (ref "C5")
      (value "100nF 25V")
      (footprint "eagle-import:0402")
      (fields (field (name "LCSC_PART") "C56392"))
      (libsource (lib "eagle-import") (part "100NF-25V-0402"))
    )
    (comp (ref "C6")
      (value "10uF 50V")
      (footprint "eagle-import:0805")
      (fields (field (name "LCSC_PART") "C440198"))
      (libsource (lib "eagle-import") (part "10UF-50V-0805"))
    )
    (comp (ref "C7")
      (value "100nF 16V")
      (footprint "eagle-import:0201")
      (fields (field (name "LCSC_PART") "C2846674"))
      (libsource (lib "eagle-import") (part "100NF-16V-0201"))
    )
    (comp (ref "C8")
      (value "100nF 16V")
      (footprint "eagle-import:0201")
      (fields (field (name "LCSC_PART") "C2846674"))
      (libsource (lib "eagle-import") (part "100NF-16V-0201"))
    )
    (comp (ref "C9")
      (value "10uF 50V")
      (footprint "eagle-import:0805")
      (fields (field (name "LCSC_PART") "C440198"))
      (libsource (lib "eagle-import") (part "10UF-50V-0805"))
    )
    (comp (ref "C10")
      (value "1nF")
      (footprint "eagle-import:C0402")
      (libsource (lib "eagle-import") (part "ds_passive_C-0402"))
    )
    (comp (ref "C11")
      (value "10uF 50V")
      (footprint "eagle-import:0805")
      (fields (field (name "LCSC_PART") "C440198"))
      (libsource (lib "eagle-import") (part "10UF-50V-0805"))
    )
    (comp (ref "C12")
      (value "10uF 50V")
      (footprint "eagle-import:0805")
      (fields (field (name "LCSC_PART") "C440198"))
      (libsource (lib "eagle-import") (part "10UF-50V-0805"))
    )
    (comp (ref "C13")
      (value "100nF 25V")
      (footprint "eagle-import:0402")
      (fields (field (name "LCSC_PART") "C56392"))
      (libsource (lib "eagle-import") (part "100NF-25V-0402"))
    )
    (comp (ref "C14")
      (value "100nF 25V")
      (footprint "eagle-import:0402")
      (fields (field (name "LCSC_PART") "C56392"))
      (libsource (lib "eagle-import") (part "100NF-25V-0402"))
    )
    (comp (ref "C15")
      (value "100nF 25V")
      (footprint "eagle-import:0402")
      (fields (field (name "LCSC_PART") "C56392"))
      (libsource (lib "eagle-import") (part "100NF-25V-0402"))
    )
    (comp (ref "C16")
      (value "100nF 25V")
      (footprint "eagle-import:0402")
      (fields (field (name "LCSC_PART") "C56392"))
      (libsource (lib "eagle-import") (part "100NF-25V-0402"))
    )
    (comp (ref "J1")
      (value "JUMPER-NO")
      (footprint "eagle-import:J-0402-NO")
      (libsource (lib "eagle-import") (part "JUMPER-NO"))
    )
    (comp (ref "J2")
      (value "JUMPER-3")
      (footprint "eagle-import:JUMPER-3")
      (libsource (lib "eagle-import") (part "JUMPER-3"))
    )
    (comp (ref "PCIE-1X1")
      (value "PCI Express x1 Edge Connector")
      (footprint "eagle-import:PCIE_X1_LOWPROFILE")
      (libsource (lib "eagle-import") (part "PCIE-1X-LOWPROFILE"))
    )
    (comp (ref "R1")
      (value "0R 1%")
      (footprint "eagle-import:0201")
      (fields (field (name "LCSC_PART") "C106227"))
      (libsource (lib "eagle-import") (part "0R0201"))
    )
  )
  (nets
    (net (code "1") (name "+1V1") (class "Default")
      (node (ref "C123") (pin "1") (pinfunction "1_1") (pintype "passive"))
      (node (ref "C124") (pin "1") (pinfunction "1_1") (pintype "passive"))
      (node (ref "C126") (pin "1") (pinfunction "1_1") (pintype "passive"))
      (node (ref "IC21") (pin "23") (pinfunction "DVDD_23") (pintype "bidirectional"))
      (node (ref "IC21") (pin "45") (pinfunction "VREG_VOUT_45") (pintype "bidirectional"))
      (node (ref "IC21") (pin "50") (pinfunction "DVDD_50") (pintype "bidirectional"))
    )
    (net (code "2") (name "+1V05") (class "Default")
      (node (ref "C17") (pin "1") (pinfunction "1_1") (pintype "passive"))
      (node (ref "C18") (pin "1") (pinfunction "1_1") (pintype "passive"))
      (node (ref "C19") (pin "1") (pinfunction "1_1") (pintype "passive"))
      (node (ref "C20") (pin "1") (pinfunction "1_1") (pintype "passive"))
      (node (ref "C21") (pin "1") (pinfunction "1_1") (pintype "passive"))
      (node (ref "C22") (pin "1") (pinfunction "1_1") (pintype "passive"))
      (node (ref "C23") (pin "1") (pinfunction "1_1") (pintype "passive"))
      (node (ref "C24") (pin "1") (pinfunction "1_1") (pintype "passive"))
      (node (ref "C25") (pin "1") (pinfunction "1_1") (pintype "passive"))
      (node (ref "C26") (pin "1") (pinfunction "1_1") (pintype "passive"))
      (node (ref "C27") (pin "1") (pinfunction "1_1") (pintype "passive"))
      (node (ref "C28") (pin "1") (pinfunction "1_1") (pintype "passive"))
      (node (ref "C29") (pin "1") (pinfunction "1_1") (pintype "passive"))
      (node (ref "C53") (pin "1") (pinfunction "1_1") (pintype "passive"))
      (node (ref "IC1") (pin "12") (pinfunction "VDD10_12") (pintype "power_in"))
      (node (ref "IC1") (pin "28") (pinfunction "VDD10_28") (pintype "power_in"))
      (node (ref "IC1") (pin "37") (pinfunction "VDD10_37") (pintype "power_in"))
      (node (ref "IC1") (pin "43") (pinfunction "VDD10_43") (pintype "power_in"))
      (node (ref "IC1") (pin "46") (pinfunction "VDD10_46") (pintype "power_in"))
      (node (ref "IC1") (pin "54") (pinfunction "VDD10_54") (pintype "power_in"))
      (node (ref "IC1") (pin "60") (pinfunction "VDD10_60") (pintype "power_in"))
      (node (ref "IC1") (pin "63") (pinfunction "VDD10_63") (pintype "power_in"))
      (node (ref "IC1") (pin "9") (pinfunction "VDD10_9") (pintype "power_in"))
      (node (ref "IC3") (pin "1") (pinfunction "OUT_1") (pintype "output"))
      (node (ref "IC3") (pin "18") (pinfunction "OUT_18") (pintype "output"))
      (node (ref "IC3") (pin "19") (pinfunction "OUT_19") (pintype "output"))
      (node (ref "IC3") (pin "20") (pinfunction "OUT_20") (pintype "output"))
      (node (ref "R10") (pin "1") (pinfunction "1_1") (pintype "passive"))
    )
    (net (code "3") (name "+1V8") (class "Default")
      (node (ref "C95") (pin "1") (pinfunction "1_1") (pintype "passive"))
      (node (ref "C96") (pin "1") (pinfunction "1_1") (pintype "passive"))
      (node (ref "C97") (pin "1") (pinfunction "1_1") (pintype "passive"))
      (node (ref "C98") (pin "1") (pinfunction "1_1") (pintype "passive"))
      (node (ref "C99") (pin "1") (pinfunction "1_1") (pintype "passive"))
      (node (ref "IC11") (pin "12") (pinfunction "VCORE_12") (pintype "power_in"))
      (node (ref "IC11") (pin "37") (pinfunction "VCORE_37") (pintype "power_in"))
      (node (ref "IC11") (pin "49") (pinfunction "VREGOUT_49") (pintype "power_in"))
      (node (ref "IC11") (pin "64") (pinfunction "VCORE_64") (pintype "power_in"))
    )
    (net (code "4") (name "+3V3") (class "Default")
      (node (ref "C30") (pin "1") (pinfunction "1_1") (pintype "passive"))
      (node (ref "C32") (pin "1") (pinfunction "1_1") (pintype "passive"))
      (node (ref "C34") (pin "1") (pinfunction "1_1") (pintype "passive"))
      (node (ref "C36") (pin "1") (pinfunction "1_1") (pintype "passive"))
      (node (ref "C38") (pin "1") (pinfunction "1_1") (pintype "passive"))
      (node (ref "C39") (pin "1") (pinfunction "1_1") (pintype "passive"))
      (node (ref "C40") (pin "1") (pinfunction "1_1") (pintype "passive"))
      (node (ref "C41") (pin "1") (pinfunction "1_1") (pintype "passive"))
      (node (ref "C46") (pin "1") (pinfunction "1_1") (pintype "passive"))
      (node (ref "D1") (pin "3") (pinfunction "C_3") (pintype "passive"))
      (node (ref "IC1") (pin "15") (pinfunction "VDD33_15") (pintype "power_in"))
      (node (ref "IC1") (pin "29") (pinfunction "VDD33_29") (pintype "power_in"))
      (node (ref "IC1") (pin "40") (pinfunction "VDD33_40") (pintype "power_in"))
      (node (ref "IC1") (pin "49") (pinfunction "VDD33_49") (pintype "power_in"))
      (node (ref "IC1") (pin "57") (pinfunction "VDD33_57") (pintype "power_in"))
      (node (ref "IC1") (pin "66") (pinfunction "VDD33_66") (pintype "power_in"))
      (node (ref "IC3") (pin "10") (pinfunction "BIAS_10") (pintype "input"))
      (node (ref "IC3") (pin "5") (pinfunction "IN_5") (pintype "input"))
      (node (ref "IC3") (pin "6") (pinfunction "IN_6") (pintype "input"))
      (node (ref "IC3") (pin "7") (pinfunction "IN_7") (pintype "input"))
      (node (ref "IC3") (pin "8") (pinfunction "IN_8") (pintype "input"))
      (node (ref "J2") (pin "2") (pinfunction "2_2") (pintype "bidirectional"))
      (node (ref "R2") (pin "1") (pinfunction "1_1") (pintype "passive"))
      (node (ref "R3") (pin "1") (pinfunction "1_1") (pintype "passive"))
      (node (ref "R5") (pin "1") (pinfunction "1_1") (pintype "passive"))
      (node (ref "R6") (pin "1") (pinfunction "1_1") (pintype "passive"))
      (node (ref "R9") (pin "1") (pinfunction "1_1") (pintype "passive"))
    )
    (net (code "5") (name "+3V3B") (class "Default")
      (node (ref "C66") (pin "1") (pinfunction "1_1") (pintype "passive"))
      (node (ref "C67") (pin "1") (pinfunction "1_1") (pintype "passive"))
      (node (ref "C68") (pin "1") (pinfunction "1_1") (pintype "passive"))
      (node (ref "C69") (pin "1") (pinfunction "1_1") (pintype "passive"))
      (node (ref "C70") (pin "1") (pinfunction "1_1") (pintype "passive"))
      (node (ref "C71") (pin "1") (pinfunction "1_1") (pintype "passive"))
      (node (ref "C72") (pin "1") (pinfunction "1_1") (pintype "passive"))
      (node (ref "C73") (pin "1") (pinfunction "1_1") (pintype "passive"))
      (node (ref "C74") (pin "1") (pinfunction "1_1") (pintype "passive"))
      (node (ref "C77") (pin "1") (pinfunction "1_1") (pintype "passive"))
      (node (ref "C78") (pin "1") (pinfunction "1_1") (pintype "passive"))
      (node (ref "C81") (pin "1") (pinfunction "1_1") (pintype "passive"))
      (node (ref "C82") (pin "1") (pinfunction "1_1") (pintype "passive"))
      (node (ref "C83") (pin "1") (pinfunction "1_1") (pintype "passive"))
      (node (ref "D8") (pin "C") (pinfunction "C_C") (pintype "passive"))
      (node (ref "IC10") (pin "20") (pinfunction "VCC_20") (pintype "power_in"))
      (node (ref "IC6") (pin "5") (pinfunction "VOUT_5") (pintype "bidirectional"))
      (node (ref "IC7") (pin "20") (pinfunction "VCC_20") (pintype "power_in"))
      (node (ref "IC8") (pin "8") (pinfunction "VCC_8") (pintype "power_in"))
      (node (ref "IC9") (pin "11") (pinfunction "VCC_11") (pintype "power_in"))
      (node (ref "IC9") (pin "17") (pinfunction "VCC_17") (pintype "power_in"))
      (node (ref "IC9") (pin "27") (pinfunction "VCC_27") (pintype "power_in"))
      (node (ref "IC9") (pin "3") (pinfunction "AVCC_3") (pintype "power_in"))
      (node (ref "IC9") (pin "32") (pinfunction "VCC_32") (pintype "power_in"))
      (node (ref "IC9") (pin "43") (pinfunction "VCC_43") (pintype "power_in"))
      (node (ref "IC9") (pin "44") (pinfunction "WAKEUP_44") (pintype "input"))
      (node (ref "IC9") (pin "55") (pinfunction "VCC_55") (pintype "power_in"))
      (node (ref "IC9") (pin "7") (pinfunction "AVCC_7") (pintype "power_in"))
      (node (ref "R19") (pin "1") (pinfunction "1_1") (pintype "passive"))
      (node (ref "R20") (pin "2") (pinfunction "2_2") (pintype "passive"))
      (node (ref "R21") (pin "2") (pinfunction "2_2") (pintype "passive"))
      (node (ref "RN11") (pin "A2") (pinfunction "2_A2") (pintype "passive"))
      (node (ref "RN11") (pin "B2") (pinfunction "2_B2") (pintype "passive"))
      (node (ref "RN11") (pin "C2") (pinfunction "2_C2") (pintype "passive"))
      (node (ref "RN11") (pin "D2") (pinfunction "2_D2") (pintype "passive"))
      (node (ref "RN12") (pin "A2") (pinfunction "2_A2") (pintype "passive"))
      (node (ref "RN12") (pin "B2") (pinfunction "2_B2") (pintype "passive"))
      (node (ref "RN12") (pin "C2") (pinfunction "2_C2") (pintype "passive"))
      (node (ref "RN12") (pin "D2") (pinfunction "2_D2") (pintype "passive"))
      (node (ref "RN5") (pin "A2") (pinfunction "2_A2") (pintype "passive"))
      (node (ref "RN5") (pin "B2") (pinfunction "2_B2") (pintype "passive"))
      (node (ref "RN5") (pin "C2") (pinfunction "2_C2") (pintype "passive"))
      (node (ref "RN5") (pin "D2") (pinfunction "2_D2") (pintype "passive"))
      (node (ref "RN6") (pin "A2") (pinfunction "2_A2") (pintype "passive"))
      (node (ref "RN6") (pin "B2") (pinfunction "2_B2") (pintype "passive"))
      (node (ref "RN6") (pin "C2") (pinfunction "2_C2") (pintype "passive"))
      (node (ref "RN6") (pin "D2") (pinfunction "2_D2") (pintype "passive"))
    )
    (net (code "6") (name "+3V3C") (class "Default")
      (node (ref "C102") (pin "1") (pinfunction "1_1") (pintype "passive"))
      (node (ref "C103") (pin "1") (pinfunction "1_1") (pintype "passive"))
      (node (ref "C109") (pin "1") (pinfunction "1_1") (pintype "passive"))
      (node (ref "C111") (pin "1") (pinfunction "1_1") (pintype "passive"))
      (node (ref "C113") (pin "1") (pinfunction "1_1") (pintype "passive"))
      (node (ref "C84") (pin "1") (pinfunction "1_1") (pintype "passive"))
      (node (ref "C87") (pin "1") (pinfunction "1_1") (pintype "passive"))
      (node (ref "C88") (pin "1") (pinfunction "1_1") (pintype "passive"))
      (node (ref "C89") (pin "1") (pinfunction "1_1") (pintype "passive"))
      (node (ref "C90") (pin "1") (pinfunction "1_1") (pintype "passive"))
      (node (ref "C91") (pin "1") (pinfunction "1_1") (pintype "passive"))
      (node (ref "C92") (pin "1") (pinfunction "1_1") (pintype "passive"))
      (node (ref "C93") (pin "1") (pinfunction "1_1") (pintype "passive"))
      (node (ref "C94") (pin "1") (pinfunction "1_1") (pintype "passive"))
      (node (ref "IC11") (pin "20") (pinfunction "VCCIO_20") (pintype "power_in"))
      (node (ref "IC11") (pin "31") (pinfunction "VCCIO_31") (pintype "power_in"))
      (node (ref "IC11") (pin "4") (pinfunction "VPHY_4") (pintype "power_in"))
      (node (ref "IC11") (pin "42") (pinfunction "VCCIO_42") (pintype "power_in"))
      (node (ref "IC11") (pin "50") (pinfunction "VREGIN_50") (pintype "power_in"))
      (node (ref "IC11") (pin "56") (pinfunction "VCCIO_56") (pintype "power_in"))
      (node (ref "IC11") (pin "9") (pinfunction "VPLL_9") (pintype "power_in"))
      (node (ref "IC12") (pin "6") (pinfunction "VCC_6") (pintype "power_in"))
      (node (ref "IC13") (pin "5") (pinfunction "VOUT_5") (pintype "bidirectional"))
      (node (ref "IC15") (pin "19") (pinfunction "VCCB_19") (pintype "power_in"))
      (node (ref "IC16") (pin "19") (pinfunction "VCCB_19") (pintype "power_in"))
      (node (ref "IC17") (pin "19") (pinfunction "VCCB_19") (pintype "power_in"))
      (node (ref "R24") (pin "1") (pinfunction "1_1") (pintype "passive"))
      (node (ref "R25") (pin "1") (pinfunction "1_1") (pintype "passive"))
      (node (ref "R26") (pin "1") (pinfunction "1_1") (pintype "passive"))
      (node (ref "R31") (pin "1") (pinfunction "1_1") (pintype "passive"))
      (node (ref "R32") (pin "1") (pinfunction "1_1") (pintype "passive"))
      (node (ref "R33") (pin "1") (pinfunction "1_1") (pintype "passive"))
    )
    (net (code "7") (name "+3V3D") (class "Default")
      (node (ref "C117") (pin "1") (pinfunction "1_1") (pintype "passive"))
      (node (ref "C118") (pin "1") (pinfunction "1_1") (pintype "passive"))
      (node (ref "C119") (pin "1") (pinfunction "1_1") (pintype "passive"))
      (node (ref "C120") (pin "1") (pinfunction "1_1") (pintype "passive"))
      (node (ref "C121") (pin "1") (pinfunction "1_1") (pintype "passive"))
      (node (ref "C122") (pin "1") (pinfunction "1_1") (pintype "passive"))
      (node (ref "C125") (pin "1") (pinfunction "1_1") (pintype "passive"))
      (node (ref "C129") (pin "1") (pinfunction "1_1") (pintype "passive"))
      (node (ref "C130") (pin "1") (pinfunction "1_1") (pintype "passive"))
      (node (ref "C131") (pin "1") (pinfunction "1_1") (pintype "passive"))
      (node (ref "C134") (pin "1") (pinfunction "1_1") (pintype "passive"))
      (node (ref "C135") (pin "1") (pinfunction "1_1") (pintype "passive"))
      (node (ref "IC21") (pin "1") (pinfunction "IOVDD_1") (pintype "bidirectional"))
      (node (ref "IC21") (pin "10") (pinfunction "IOVDD_10") (pintype "bidirectional"))
      (node (ref "IC21") (pin "22") (pinfunction "IOVDD_22") (pintype "bidirectional"))
      (node (ref "IC21") (pin "33") (pinfunction "IOVDD_33") (pintype "bidirectional"))
      (node (ref "IC21") (pin "42") (pinfunction "IOVDD_42") (pintype "bidirectional"))
      (node (ref "IC21") (pin "43") (pinfunction "ADC_AVDD_43") (pintype "bidirectional"))
      (node (ref "IC21") (pin "44") (pinfunction "VREG_VIN_44") (pintype "bidirectional"))
      (node (ref "IC21") (pin "48") (pinfunction "USB_VDD_48") (pintype "bidirectional"))
      (node (ref "IC21") (pin "49") (pinfunction "IOVDD_49") (pintype "bidirectional"))
      (node (ref "IC22") (pin "8") (pinfunction "VCC_8") (pintype "power_in"))
      (node (ref "IC23") (pin "5") (pinfunction "VCC_5") (pintype "power_in"))
      (node (ref "IC24") (pin "5") (pinfunction "VCC_5") (pintype "power_in"))
      (node (ref "IC25") (pin "5") (pinfunction "VOUT_5") (pintype "bidirectional"))
      (node (ref "R65") (pin "1") (pinfunction "1_1") (pintype "passive"))
    )
    (net (code "8") (name "+3V3_A") (class "Default")
      (node (ref "C31") (pin "1") (pinfunction "1_1") (pintype "passive"))
      (node (ref "C33") (pin "1") (pinfunction "1_1") (pintype "passive"))
      (node (ref "C35") (pin "1") (pinfunction "1_1") (pintype "passive"))
      (node (ref "C37") (pin "1") (pinfunction "1_1") (pintype "passive"))
      (node (ref "IC1") (pin "32") (pinfunction "AVDD33_32") (pintype "power_in"))
      (node (ref "IC1") (pin "6") (pinfunction "AVDD33_6") (pintype "power_in"))
      (node (ref "R2") (pin "2") (pinfunction "2_2") (pintype "passive"))
    )
    (net (code "9") (name "+3V3_AUX") (class "Default")
      (node (ref "AUX3") (pin "TP") (pinfunction "TP_TP") (pintype "input"))
      (node (ref "J2") (pin "3") (pinfunction "3_3") (pintype "bidirectional"))
      (node (ref "PCIE-1X1") (pin "B10") (pinfunction "+3V3_AUX_B10") (pintype "power_in"))
    )
    (net (code "10") (name "+5V") (class "Default")
      (node (ref "C51") (pin "1") (pinfunction "1_1") (pintype "passive"))
      (node (ref "C52") (pin "1") (pinfunction "+_1") (pintype "passive"))
      (node (ref "C55") (pin "1") (pinfunction "1_1") (pintype "passive"))
      (node (ref "C56") (pin "1") (pinfunction "1_1") (pintype "passive"))
      (node (ref "IC4") (pin "2") (pinfunction "IN_2") (pintype "input"))
      (node (ref "IC4") (pin "3") (pinfunction "IN_3") (pintype "input"))
      (node (ref "IC5") (pin "2") (pinfunction "IN_2") (pintype "input"))
      (node (ref "IC5") (pin "3") (pinfunction "IN_3") (pintype "input"))
      (node (ref "L1") (pin "1") (pinfunction "1_1") (pintype "passive"))
      (node (ref "R12") (pin "1") (pinfunction "1_1") (pintype "passive"))
      (node (ref "R7") (pin "1") (pinfunction "1_1") (pintype "passive"))
    )
    (net (code "11") (name "+12V") (class "Default")
      (node (ref "C1") (pin "1") (pinfunction "1_1") (pintype "passive"))
      (node (ref "C2") (pin "1") (pinfunction "1_1") (pintype "passive"))
      (node (ref "C3") (pin "1") (pinfunction "1_1") (pintype "passive"))
      (node (ref "C4") (pin "1") (pinfunction "1_1") (pintype "passive"))
      (node (ref "C45") (pin "1") (pinfunction "1_1") (pintype "passive"))
      (node (ref "C47") (pin "1") (pinfunction "1_1") (pintype "passive"))
      (node (ref "C5") (pin "1") (pinfunction "1_1") (pintype "passive"))
      (node (ref "C6") (pin "1") (pinfunction "1_1") (pintype "passive"))
      (node (ref "C9") (pin "1") (pinfunction "1_1") (pintype "passive"))
      (node (ref "IC2") (pin "7") (pinfunction "VIN_7") (pintype "input"))
      (node (ref "PCIE-1X1") (pin "A2") (pinfunction "+12V_A2") (pintype "power_in"))
      (node (ref "PCIE-1X1") (pin "A3") (pinfunction "+12V_A3") (pintype "power_in"))
      (node (ref "PCIE-1X1") (pin "B1") (pinfunction "+12V_B1") (pintype "power_in"))
      (node (ref "PCIE-1X1") (pin "B2") (pinfunction "+12V_B2") (pintype "power_in"))
      (node (ref "PCIE-1X1") (pin "B3") (pinfunction "+12V_B3") (pintype "power_in"))
    )
    (net (code "12") (name "4232R_RESET") (class "Default")
      (node (ref "R27") (pin "2") (pinfunction "2_2") (pintype "passive"))
      (node (ref "R28") (pin "1") (pinfunction "1_1") (pintype "passive"))
      (node (ref "R30") (pin "1") (pinfunction "1_1") (pintype "passive"))
    )
    (net (code "13") (name "4232_RESET") (class "Default")
      (node (ref "IC11") (pin "14") (pinfunction "~{RESET}_14") (pintype "input"))
      (node (ref "R30") (pin "2") (pinfunction "2_2") (pintype "passive"))
    )
    (net (code "14") (name "BOOT_5V") (class "Default")
      (node (ref "C50") (pin "1") (pinfunction "1_1") (pintype "passive"))
      (node (ref "IC2") (pin "1") (pinfunction "BOOT_1") (pintype "input"))
    )
    (net (code "15") (name "BUF_PB0") (class "Default")
      (node (ref "IC7") (pin "18") (pinfunction "Y0_18") (pintype "bidirectional"))
      (node (ref "RN3") (pin "A1") (pinfunction "1_A1") (pintype "passive"))
    )
    (net (code "16") (name "BUF_PB1") (class "Default")
      (node (ref "IC7") (pin "17") (pinfunction "Y1_17") (pintype "bidirectional"))
      (node (ref "RN3") (pin "B1") (pinfunction "1_B1") (pintype "passive"))
    )
    (net (code "17") (name "BUF_PB2") (class "Default")
      (node (ref "IC7") (pin "16") (pinfunction "Y2_16") (pintype "bidirectional"))
      (node (ref "RN3") (pin "C1") (pinfunction "1_C1") (pintype "passive"))
    )
    (net (code "18") (name "BUF_PB3") (class "Default")
      (node (ref "IC7") (pin "15") (pinfunction "Y3_15") (pintype "bidirectional"))
      (node (ref "RN3") (pin "D1") (pinfunction "1_D1") (pintype "passive"))
    )
    (net (code "19") (name "BUF_PB4") (class "Default")
      (node (ref "IC7") (pin "14") (pinfunction "Y4_14") (pintype "bidirectional"))
      (node (ref "RN4") (pin "A1") (pinfunction "1_A1") (pintype "passive"))
    )
    (net (code "20") (name "BUF_PB5") (class "Default")
      (node (ref "IC7") (pin "13") (pinfunction "Y5_13") (pintype "bidirectional"))
      (node (ref "RN4") (pin "B1") (pinfunction "1_B1") (pintype "passive"))
    )
    (net (code "21") (name "BUF_PB6") (class "Default")
      (node (ref "IC7") (pin "12") (pinfunction "Y6_12") (pintype "bidirectional"))
      (node (ref "RN4") (pin "C1") (pinfunction "1_C1") (pintype "passive"))
    )
    (net (code "22") (name "BUF_PB7") (class "Default")
      (node (ref "IC7") (pin "11") (pinfunction "Y7_11") (pintype "bidirectional"))
      (node (ref "RN4") (pin "D1") (pinfunction "1_D1") (pintype "passive"))
    )
    (net (code "23") (name "BUF_PD0") (class "Default")
      (node (ref "IC10") (pin "18") (pinfunction "Y0_18") (pintype "bidirectional"))
      (node (ref "RN9") (pin "A1") (pinfunction "1_A1") (pintype "passive"))
    )
    (net (code "24") (name "BUF_PD1") (class "Default")
      (node (ref "IC10") (pin "17") (pinfunction "Y1_17") (pintype "bidirectional"))
      (node (ref "RN9") (pin "B1") (pinfunction "1_B1") (pintype "passive"))
    )
    (net (code "25") (name "BUF_PD2") (class "Default")
      (node (ref "IC10") (pin "16") (pinfunction "Y2_16") (pintype "bidirectional"))
      (node (ref "RN9") (pin "C1") (pinfunction "1_C1") (pintype "passive"))
    )
    (net (code "26") (name "BUF_PD3") (class "Default")
      (node (ref "IC10") (pin "15") (pinfunction "Y3_15") (pintype "bidirectional"))
      (node (ref "RN9") (pin "D1") (pinfunction "1_D1") (pintype "passive"))
    )
    (net (code "27") (name "BUF_PD4") (class "Default")
      (node (ref "IC10") (pin "14") (pinfunction "Y4_14") (pintype "bidirectional"))
      (node (ref "RN10") (pin "A1") (pinfunction "1_A1") (pintype "passive"))
    )
    (net (code "28") (name "BUF_PD5") (class "Default")
      (node (ref "IC10") (pin "13") (pinfunction "Y5_13") (pintype "bidirectional"))
      (node (ref "RN10") (pin "B1") (pinfunction "1_B1") (pintype "passive"))
    )
    (net (code "29") (name "BUF_PD6") (class "Default")
      (node (ref "IC10") (pin "12") (pinfunction "Y6_12") (pintype "bidirectional"))
      (node (ref "RN10") (pin "C1") (pinfunction "1_C1") (pintype "passive"))
    )
    (net (code "30") (name "BUF_PD7") (class "Default")
      (node (ref "IC10") (pin "11") (pinfunction "Y7_11") (pintype "bidirectional"))
      (node (ref "RN10") (pin "D1") (pinfunction "1_D1") (pintype "passive"))
    )
    (net (code "31") (name "CH0") (class "Default")
      (node (ref "LA") (pin "17") (pinfunction "17_17") (pintype "passive"))
      (node (ref "RN1") (pin "A1") (pinfunction "1_A1") (pintype "passive"))
    )
    (net (code "32") (name "CH1") (class "Default")
      (node (ref "LA") (pin "15") (pinfunction "15_15") (pintype "passive"))
      (node (ref "RN1") (pin "B1") (pinfunction "1_B1") (pintype "passive"))
    )
    (net (code "33") (name "CH2") (class "Default")
      (node (ref "LA") (pin "13") (pinfunction "13_13") (pintype "passive"))
      (node (ref "RN1") (pin "C1") (pinfunction "1_C1") (pintype "passive"))
    )
    (net (code "34") (name "CH3") (class "Default")
      (node (ref "LA") (pin "11") (pinfunction "11_11") (pintype "passive"))
      (node (ref "RN1") (pin "D1") (pinfunction "1_D1") (pintype "passive"))
    )
    (net (code "35") (name "CH4") (class "Default")
      (node (ref "LA") (pin "9") (pinfunction "9_9") (pintype "passive"))
      (node (ref "RN2") (pin "A1") (pinfunction "1_A1") (pintype "passive"))
    )
    (net (code "36") (name "CH5") (class "Default")
      (node (ref "LA") (pin "7") (pinfunction "7_7") (pintype "passive"))
      (node (ref "RN2") (pin "B1") (pinfunction "1_B1") (pintype "passive"))
    )
    (net (code "37") (name "CH6") (class "Default")
      (node (ref "LA") (pin "5") (pinfunction "5_5") (pintype "passive"))
      (node (ref "RN2") (pin "C1") (pinfunction "1_C1") (pintype "passive"))
    )
    (net (code "38") (name "CH7") (class "Default")
      (node (ref "LA") (pin "3") (pinfunction "3_3") (pintype "passive"))
      (node (ref "RN2") (pin "D1") (pinfunction "1_D1") (pintype "passive"))
    )
    (net (code "39") (name "CH8") (class "Default")
      (node (ref "LA") (pin "4") (pinfunction "4_4") (pintype "passive"))
      (node (ref "RN7") (pin "A1") (pinfunction "1_A1") (pintype "passive"))
    )
    (net (code "40") (name "CH9") (class "Default")
      (node (ref "LA") (pin "6") (pinfunction "6_6") (pintype "passive"))
      (node (ref "RN7") (pin "B1") (pinfunction "1_B1") (pintype "passive"))
    )
    (net (code "41") (name "CH10") (class "Default")
      (node (ref "LA") (pin "8") (pinfunction "8_8") (pintype "passive"))
      (node (ref "RN7") (pin "C1") (pinfunction "1_C1") (pintype "passive"))
    )
    (net (code "42") (name "CH11") (class "Default")
      (node (ref "LA") (pin "10") (pinfunction "10_10") (pintype "passive"))
      (node (ref "RN7") (pin "D1") (pinfunction "1_D1") (pintype "passive"))
    )
    (net (code "43") (name "CH12") (class "Default")
      (node (ref "LA") (pin "12") (pinfunction "12_12") (pintype "passive"))
      (node (ref "RN8") (pin "A1") (pinfunction "1_A1") (pintype "passive"))
    )
    (net (code "44") (name "CH13") (class "Default")
      (node (ref "LA") (pin "14") (pinfunction "14_14") (pintype "passive"))
      (node (ref "RN8") (pin "B1") (pinfunction "1_B1") (pintype "passive"))
    )
    (net (code "45") (name "CH14") (class "Default")
      (node (ref "LA") (pin "16") (pinfunction "16_16") (pintype "passive"))
      (node (ref "RN8") (pin "C1") (pinfunction "1_C1") (pintype "passive"))
    )
    (net (code "46") (name "CH15") (class "Default")
      (node (ref "LA") (pin "18") (pinfunction "18_18") (pintype "passive"))
      (node (ref "RN8") (pin "D1") (pinfunction "1_D1") (pintype "passive"))
    )
    (net (code "47") (name "CHI0") (class "Default")
      (node (ref "IC7") (pin "2") (pinfunction "A0_2") (pintype "bidirectional"))
      (node (ref "RN1") (pin "A2") (pinfunction "2_A2") (pintype "passive"))
      (node (ref "RN5") (pin "A1") (pinfunction "1_A1") (pintype "passive"))
    )
    (net (code "48") (name "CHI1") (class "Default")
      (node (ref "IC7") (pin "3") (pinfunction "A1_3") (pintype "bidirectional"))
      (node (ref "RN1") (pin "B2") (pinfunction "2_B2") (pintype "passive"))
      (node (ref "RN5") (pin "B1") (pinfunction "1_B1") (pintype "passive"))
    )
    (net (code "49") (name "CHI2") (class "Default")
      (node (ref "IC7") (pin "4") (pinfunction "A2_4") (pintype "bidirectional"))
      (node (ref "RN1") (pin "C2") (pinfunction "2_C2") (pintype "passive"))
      (node (ref "RN5") (pin "C1") (pinfunction "1_C1") (pintype "passive"))
    )
    (net (code "50") (name "CHI3") (class "Default")
      (node (ref "IC7") (pin "5") (pinfunction "A3_5") (pintype "bidirectional"))
      (node (ref "RN1") (pin "D2") (pinfunction "2_D2") (pintype "passive"))
      (node (ref "RN5") (pin "D1") (pinfunction "1_D1") (pintype "passive"))
    )
    (net (code "51") (name "CHI4") (class "Default")
      (node (ref "IC7") (pin "6") (pinfunction "A4_6") (pintype "bidirectional"))
      (node (ref "RN2") (pin "A2") (pinfunction "2_A2") (pintype "passive"))
      (node (ref "RN6") (pin "A1") (pinfunction "1_A1") (pintype "passive"))
    )
    (net (code "52") (name "CHI5") (class "Default")
      (node (ref "IC7") (pin "7") (pinfunction "A5_7") (pintype "bidirectional"))
      (node (ref "RN2") (pin "B2") (pinfunction "2_B2") (pintype "passive"))
      (node (ref "RN6") (pin "B1") (pinfunction "1_B1") (pintype "passive"))
    )
    (net (code "53") (name "CHI6") (class "Default")
      (node (ref "IC7") (pin "8") (pinfunction "A6_8") (pintype "bidirectional"))
      (node (ref "RN2") (pin "C2") (pinfunction "2_C2") (pintype "passive"))
      (node (ref "RN6") (pin "C1") (pinfunction "1_C1") (pintype "passive"))
    )
    (net (code "54") (name "CHI7") (class "Default")
      (node (ref "IC7") (pin "9") (pinfunction "A7_9") (pintype "bidirectional"))
      (node (ref "RN2") (pin "D2") (pinfunction "2_D2") (pintype "passive"))
      (node (ref "RN6") (pin "D1") (pinfunction "1_D1") (pintype "passive"))
    )
    (net (code "55") (name "CHI8") (class "Default")
      (node (ref "IC10") (pin "2") (pinfunction "A0_2") (pintype "bidirectional"))
      (node (ref "RN11") (pin "A1") (pinfunction "1_A1") (pintype "passive"))
      (node (ref "RN7") (pin "A2") (pinfunction "2_A2") (pintype "passive"))
    )
    (net (code "56") (name "CHI9") (class "Default")
      (node (ref "IC10") (pin "3") (pinfunction "A1_3") (pintype "bidirectional"))
      (node (ref "RN11") (pin "B1") (pinfunction "1_B1") (pintype "passive"))
      (node (ref "RN7") (pin "B2") (pinfunction "2_B2") (pintype "passive"))
    )
    (net (code "57") (name "CHI10") (class "Default")
      (node (ref "IC10") (pin "4") (pinfunction "A2_4") (pintype "bidirectional"))
      (node (ref "RN11") (pin "C1") (pinfunction "1_C1") (pintype "passive"))
      (node (ref "RN7") (pin "C2") (pinfunction "2_C2") (pintype "passive"))
    )
    (net (code "58") (name "CHI11") (class "Default")
      (node (ref "IC10") (pin "5") (pinfunction "A3_5") (pintype "bidirectional"))
      (node (ref "RN11") (pin "D1") (pinfunction "1_D1") (pintype "passive"))
      (node (ref "RN7") (pin "D2") (pinfunction "2_D2") (pintype "passive"))
    )
    (net (code "59") (name "CHI12") (class "Default")
      (node (ref "IC10") (pin "6") (pinfunction "A4_6") (pintype "bidirectional"))
      (node (ref "RN12") (pin "A1") (pinfunction "1_A1") (pintype "passive"))
      (node (ref "RN8") (pin "A2") (pinfunction "2_A2") (pintype "passive"))
    )
    (net (code "60") (name "CHI13") (class "Default")
      (node (ref "IC10") (pin "7") (pinfunction "A5_7") (pintype "bidirectional"))
      (node (ref "RN12") (pin "B1") (pinfunction "1_B1") (pintype "passive"))
      (node (ref "RN8") (pin "B2") (pinfunction "2_B2") (pintype "passive"))
    )
    (net (code "61") (name "CHI14") (class "Default")
      (node (ref "IC10") (pin "8") (pinfunction "A6_8") (pintype "bidirectional"))
      (node (ref "RN12") (pin "C1") (pinfunction "1_C1") (pintype "passive"))
      (node (ref "RN8") (pin "C2") (pinfunction "2_C2") (pintype "passive"))
    )
    (net (code "62") (name "CHI15") (class "Default")
      (node (ref "IC10") (pin "9") (pinfunction "A7_9") (pintype "bidirectional"))
      (node (ref "RN12") (pin "D1") (pinfunction "1_D1") (pintype "passive"))
      (node (ref "RN8") (pin "D2") (pinfunction "2_D2") (pintype "passive"))
    )
    (net (code "63") (name "CLK") (class "Default")
      (node (ref "R62") (pin "2") (pinfunction "2_2") (pintype "passive"))
      (node (ref "RPDBUG") (pin "1") (pinfunction "1_1") (pintype "passive"))
    )
    (net (code "64") (name "DIO") (class "Default")
      (node (ref "R63") (pin "2") (pinfunction "2_2") (pintype "passive"))
      (node (ref "R64") (pin "2") (pinfunction "2_2") (pintype "passive"))
      (node (ref "RPDBUG") (pin "3") (pinfunction "3_3") (pintype "passive"))
    )
    (net (code "65") (name "DS1_VBUS") (class "Default")
      (node (ref "C57") (pin "1") (pinfunction "1_1") (pintype "passive"))
      (node (ref "C59") (pin "1") (pinfunction "+_1") (pintype "passive"))
      (node (ref "C79") (pin "1") (pinfunction "1_1") (pintype "passive"))
      (node (ref "C80") (pin "1") (pinfunction "1_1") (pintype "passive"))
      (node (ref "IC4") (pin "9") (pinfunction "OUT1_9") (pintype "output"))
      (node (ref "IC6") (pin "1") (pinfunction "VIN_1") (pintype "bidirectional"))
      (node (ref "IC6") (pin "3") (pinfunction "EN_3") (pintype "bidirectional"))
      (node (ref "R17") (pin "1") (pinfunction "1_1") (pintype "passive"))
    )
    (net (code "66") (name "DS2_VBUS") (class "Default")
      (node (ref "C100") (pin "1") (pinfunction "1_1") (pintype "passive"))
      (node (ref "C101") (pin "1") (pinfunction "1_1") (pintype "passive"))
      (node (ref "C105") (pin "1") (pinfunction "1_1") (pintype "passive"))
      (node (ref "C106") (pin "1") (pinfunction "1_1") (pintype "passive"))
      (node (ref "C114") (pin "1") (pinfunction "1_1") (pintype "passive"))
      (node (ref "C115") (pin "1") (pinfunction "1_1") (pintype "passive"))
      (node (ref "C116") (pin "1") (pinfunction "1_1") (pintype "passive"))
      (node (ref "C61") (pin "1") (pinfunction "1_1") (pintype "passive"))
      (node (ref "C63") (pin "1") (pinfunction "+_1") (pintype "passive"))
      (node (ref "IC13") (pin "1") (pinfunction "VIN_1") (pintype "bidirectional"))
      (node (ref "IC13") (pin "3") (pinfunction "EN_3") (pintype "bidirectional"))
      (node (ref "IC14") (pin "5") (pinfunction "V+_5") (pintype "power_in"))
      (node (ref "IC18") (pin "4") (pinfunction "V+_4") (pintype "power_in"))
      (node (ref "IC19") (pin "4") (pinfunction "V+_4") (pintype "power_in"))
      (node (ref "IC20") (pin "4") (pinfunction "V+_4") (pintype "power_in"))
      (node (ref "IC4") (pin "8") (pinfunction "OUT2_8") (pintype "output"))
      (node (ref "R15") (pin "1") (pinfunction "1_1") (pintype "passive"))
      (node (ref "R27") (pin "1") (pinfunction "1_1") (pintype "passive"))
      (node (ref "R36") (pin "1") (pinfunction "1_1") (pintype "passive"))
      (node (ref "R45") (pin "1") (pinfunction "1_1") (pintype "passive"))
      (node (ref "R47") (pin "1") (pinfunction "1_1") (pintype "passive"))
    )
    (net (code "67") (name "DS3_VBUS") (class "Default")
      (node (ref "C132") (pin "1") (pinfunction "1_1") (pintype "passive"))
      (node (ref "C133") (pin "1") (pinfunction "1_1") (pintype "passive"))
      (node (ref "C58") (pin "1") (pinfunction "1_1") (pintype "passive"))
      (node (ref "C60") (pin "1") (pinfunction "+_1") (pintype "passive"))
      (node (ref "IC25") (pin "1") (pinfunction "VIN_1") (pintype "bidirectional"))
      (node (ref "IC25") (pin "3") (pinfunction "EN_3") (pintype "bidirectional"))
      (node (ref "IC5") (pin "9") (pinfunction "OUT1_9") (pintype "output"))
      (node (ref "R18") (pin "1") (pinfunction "1_1") (pintype "passive"))
    )
    (net (code "68") (name "DS4_VBUS") (class "Default")
      (node (ref "C62") (pin "1") (pinfunction "1_1") (pintype "passive"))
      (node (ref "C64") (pin "1") (pinfunction "+_1") (pintype "passive"))
      (node (ref "IC5") (pin "8") (pinfunction "OUT2_8") (pintype "output"))
      (node (ref "J4") (pin "1") (pinfunction "1_1") (pintype "passive"))
      (node (ref "R16") (pin "1") (pinfunction "1_1") (pintype "passive"))
    )
    (net (code "69") (name "EECLK") (class "Default")
      (node (ref "IC11") (pin "62") (pinfunction "EECLK_62") (pintype "output"))
      (node (ref "IC12") (pin "4") (pinfunction "CLK_4") (pintype "input"))
      (node (ref "R26") (pin "2") (pinfunction "2_2") (pintype "passive"))
    )
    (net (code "70") (name "EECS") (class "Default")
      (node (ref "IC11") (pin "63") (pinfunction "EECS_63") (pintype "bidirectional"))
      (node (ref "IC12") (pin "5") (pinfunction "~{CS}_5") (pintype "input"))
      (node (ref "R24") (pin "2") (pinfunction "2_2") (pintype "passive"))
    )
    (net (code "71") (name "EEDATA") (class "Default")
      (node (ref "IC11") (pin "61") (pinfunction "EEDATA_61") (pintype "bidirectional"))
      (node (ref "IC12") (pin "3") (pinfunction "DI_3") (pintype "input"))
      (node (ref "R23") (pin "2") (pinfunction "2_2") (pintype "passive"))
      (node (ref "R25") (pin "2") (pinfunction "2_2") (pintype "passive"))
    )
    (net (code "72") (name "EN_1V1") (class "Default")
      (node (ref "C48") (pin "1") (pinfunction "1_1") (pintype "passive"))
      (node (ref "IC3") (pin "11") (pinfunction "EN_11") (pintype "bidirectional"))
      (node (ref "R6") (pin "2") (pinfunction "2_2") (pintype "passive"))
    )
    (net (code "73") (name "FB_1V1") (class "Default")
      (node (ref "IC3") (pin "16") (pinfunction "FB_16") (pintype "bidirectional"))
      (node (ref "R10") (pin "2") (pinfunction "2_2") (pintype "passive"))
      (node (ref "R11") (pin "1") (pinfunction "1_1") (pintype "passive"))
    )
    (net (code "74") (name "FB_5V") (class "Default")
      (node (ref "IC2") (pin "4") (pinfunction "VSENSE_4") (pintype "input"))
      (node (ref "R7") (pin "2") (pinfunction "2_2") (pintype "passive"))
      (node (ref "R8") (pin "1") (pinfunction "1_1") (pintype "passive"))
    )
    (net (code "75") (name "FT_SCL") (class "Default")
      (node (ref "IC11") (pin "16") (pinfunction "ADBUS0_16") (pintype "bidirectional"))
      (node (ref "IC15") (pin "12") (pinfunction "B8_12") (pintype "bidirectional"))
      (node (ref "R32") (pin "2") (pinfunction "2_2") (pintype "passive"))
    )
    (net (code "76") (name "FT_SCL_OUT") (class "Default")
      (node (ref "IC15") (pin "9") (pinfunction "A8_9") (pintype "bidirectional"))
    )
    (net (code "77") (name "FT_SDA") (class "Default")
      (node (ref "IC11") (pin "17") (pinfunction "ADBUS1_17") (pintype "bidirectional"))
      (node (ref "IC11") (pin "18") (pinfunction "ADBUS2_18") (pintype "bidirectional"))
      (node (ref "IC15") (pin "13") (pinfunction "B7_13") (pintype "bidirectional"))
      (node (ref "R31") (pin "2") (pinfunction "2_2") (pintype "passive"))
    )
    (net (code "78") (name "FT_SDA_OUT") (class "Default")
      (node (ref "IC15") (pin "8") (pinfunction "A7_8") (pintype "bidirectional"))
    )
    (net (code "79") (name "GND") (class "Default")
      (node (ref "1V8") (pin "C") (pinfunction "C_C") (pintype "passive"))
      (node (ref "2V5") (pin "C") (pinfunction "C_C") (pintype "passive"))
      (node (ref "3V3") (pin "C") (pinfunction "C_C") (pintype "passive"))
      (node (ref "C1") (pin "2") (pinfunction "2_2") (pintype "passive"))
      (node (ref "C10") (pin "2") (pinfunction "2_2") (pintype "passive"))
      (node (ref "C100") (pin "2") (pinfunction "2_2") (pintype "passive"))
      (node (ref "C101") (pin "2") (pinfunction "2_2") (pintype "passive"))
      (node (ref "C102") (pin "2") (pinfunction "2_2") (pintype "passive"))
      (node (ref "C103") (pin "2") (pinfunction "2_2") (pintype "passive"))
      (node (ref "C104") (pin "2") (pinfunction "2_2") (pintype "passive"))
      (node (ref "C105") (pin "2") (pinfunction "2_2") (pintype "passive"))
      (node (ref "C106") (pin "2") (pinfunction "2_2") (pintype "passive"))
      (node (ref "C107") (pin "2") (pinfunction "2_2") (pintype "passive"))
      (node (ref "C108") (pin "2") (pinfunction "2_2") (pintype "passive"))
      (node (ref "C109") (pin "2") (pinfunction "2_2") (pintype "passive"))
      (node (ref "C11") (pin "2") (pinfunction "2_2") (pintype "passive"))
      (node (ref "C110") (pin "2") (pinfunction "2_2") (pintype "passive"))
      (node (ref "C111") (pin "2") (pinfunction "2_2") (pintype "passive"))
      (node (ref "C112") (pin "2") (pinfunction "2_2") (pintype "passive"))
      (node (ref "C113") (pin "2") (pinfunction "2_2") (pintype "passive"))
      (node (ref "C114") (pin "2") (pinfunction "2_2") (pintype "passive"))
      (node (ref "C115") (pin "2") (pinfunction "2_2") (pintype "passive"))
      (node (ref "C116") (pin "2") (pinfunction "2_2") (pintype "passive"))
      (node (ref "C117") (pin "2") (pinfunction "2_2") (pintype "passive"))
      (node (ref "C118") (pin "2") (pinfunction "2_2") (pintype "passive"))
      (node (ref "C119") (pin "2") (pinfunction "2_2") (pintype "passive"))
      (node (ref "C12") (pin "2") (pinfunction "2_2") (pintype "passive"))
      (node (ref "C120") (pin "2") (pinfunction "2_2") (pintype "passive"))
      (node (ref "C121") (pin "2") (pinfunction "2_2") (pintype "passive"))
      (node (ref "C122") (pin "2") (pinfunction "2_2") (pintype "passive"))
      (node (ref "C123") (pin "2") (pinfunction "2_2") (pintype "passive"))
      (node (ref "C124") (pin "2") (pinfunction "2_2") (pintype "passive"))
      (node (ref "C125") (pin "2") (pinfunction "2_2") (pintype "passive"))
      (node (ref "C126") (pin "2") (pinfunction "2_2") (pintype "passive"))
      (node (ref "C127") (pin "2") (pinfunction "2_2") (pintype "passive"))
      (node (ref "C128") (pin "2") (pinfunction "2_2") (pintype "passive"))
      (node (ref "C129") (pin "2") (pinfunction "2_2") (pintype "passive"))
      (node (ref "C13") (pin "2") (pinfunction "2_2") (pintype "passive"))
      (node (ref "C130") (pin "2") (pinfunction "2_2") (pintype "passive"))
      (node (ref "C131") (pin "2") (pinfunction "2_2") (pintype "passive"))
      (node (ref "C132") (pin "2") (pinfunction "2_2") (pintype "passive"))
      (node (ref "C133") (pin "2") (pinfunction "2_2") (pintype "passive"))
      (node (ref "C134") (pin "2") (pinfunction "2_2") (pintype "passive"))
      (node (ref "C135") (pin "2") (pinfunction "2_2") (pintype "passive"))
      (node (ref "C14") (pin "2") (pinfunction "2_2") (pintype "passive"))
      (node (ref "C15") (pin "2") (pinfunction "2_2") (pintype "passive"))
      (node (ref "C16") (pin "2") (pinfunction "2_2") (pintype "passive"))
      (node (ref "C17") (pin "2") (pinfunction "2_2") (pintype "passive"))
      (node (ref "C18") (pin "2") (pinfunction "2_2") (pintype "passive"))
      (node (ref "C19") (pin "2") (pinfunction "2_2") (pintype "passive"))
      (node (ref "C2") (pin "2") (pinfunction "2_2") (pintype "passive"))
      (node (ref "C20") (pin "2") (pinfunction "2_2") (pintype "passive"))
      (node (ref "C21") (pin "2") (pinfunction "2_2") (pintype "passive"))
      (node (ref "C22") (pin "2") (pinfunction "2_2") (pintype "passive"))
      (node (ref "C23") (pin "2") (pinfunction "2_2") (pintype "passive"))
      (node (ref "C24") (pin "2") (pinfunction "2_2") (pintype "passive"))
      (node (ref "C25") (pin "2") (pinfunction "2_2") (pintype "passive"))
      (node (ref "C26") (pin "2") (pinfunction "2_2") (pintype "passive"))
      (node (ref "C27") (pin "2") (pinfunction "2_2") (pintype "passive"))
      (node (ref "C28") (pin "2") (pinfunction "2_2") (pintype "passive"))
      (node (ref "C29") (pin "2") (pinfunction "2_2") (pintype "passive"))
      (node (ref "C3") (pin "2") (pinfunction "2_2") (pintype "passive"))
      (node (ref "C30") (pin "2") (pinfunction "2_2") (pintype "passive"))
      (node (ref "C31") (pin "2") (pinfunction "2_2") (pintype "passive"))
      (node (ref "C32") (pin "2") (pinfunction "2_2") (pintype "passive"))
      (node (ref "C33") (pin "2") (pinfunction "2_2") (pintype "passive"))
      (node (ref "C34") (pin "2") (pinfunction "2_2") (pintype "passive"))
      (node (ref "C35") (pin "2") (pinfunction "2_2") (pintype "passive"))
      (node (ref "C36") (pin "2") (pinfunction "2_2") (pintype "passive"))
      (node (ref "C37") (pin "2") (pinfunction "2_2") (pintype "passive"))
      (node (ref "C38") (pin "2") (pinfunction "2_2") (pintype "passive"))
      (node (ref "C39") (pin "2") (pinfunction "2_2") (pintype "passive"))
      (node (ref "C4") (pin "2") (pinfunction "2_2") (pintype "passive"))
      (node (ref "C40") (pin "2") (pinfunction "2_2") (pintype "passive"))
      (node (ref "C41") (pin "2") (pinfunction "2_2") (pintype "passive"))
      (node (ref "C42") (pin "2") (pinfunction "2_2") (pintype "passive"))
      (node (ref "C43") (pin "2") (pinfunction "2_2") (pintype "passive"))
      (node (ref "C44") (pin "2") (pinfunction "2_2") (pintype "passive"))
      (node (ref "C45") (pin "2") (pinfunction "2_2") (pintype "passive"))
      (node (ref "C46") (pin "2") (pinfunction "2_2") (pintype "passive"))
      (node (ref "C47") (pin "2") (pinfunction "2_2") (pintype "passive"))
      (node (ref "C48") (pin "2") (pinfunction "2_2") (pintype "passive"))
      (node (ref "C49") (pin "2") (pinfunction "2_2") (pintype "passive"))
      (node (ref "C5") (pin "2") (pinfunction "2_2") (pintype "passive"))
      (node (ref "C51") (pin "2") (pinfunction "2_2") (pintype "passive"))
      (node (ref "C52") (pin "2") (pinfunction "-_2") (pintype "passive"))
      (node (ref "C53") (pin "2") (pinfunction "2_2") (pintype "passive"))
      (node (ref "C54") (pin "2") (pinfunction "2_2") (pintype "passive"))
      (node (ref "C55") (pin "2") (pinfunction "2_2") (pintype "passive"))
      (node (ref "C56") (pin "2") (pinfunction "2_2") (pintype "passive"))
      (node (ref "C57") (pin "2") (pinfunction "2_2") (pintype "passive"))
      (node (ref "C58") (pin "2") (pinfunction "2_2") (pintype "passive"))
      (node (ref "C59") (pin "2") (pinfunction "-_2") (pintype "passive"))
      (node (ref "C6") (pin "2") (pinfunction "2_2") (pintype "passive"))
      (node (ref "C60") (pin "2") (pinfunction "-_2") (pintype "passive"))
      (node (ref "C61") (pin "2") (pinfunction "2_2") (pintype "passive"))
      (node (ref "C62") (pin "2") (pinfunction "2_2") (pintype "passive"))
      (node (ref "C63") (pin "2") (pinfunction "-_2") (pintype "passive"))
      (node (ref "C64") (pin "2") (pinfunction "-_2") (pintype "passive"))
      (node (ref "C65") (pin "2") (pinfunction "2_2") (pintype "passive"))
      (node (ref "C66") (pin "2") (pinfunction "2_2") (pintype "passive"))
      (node (ref "C67") (pin "2") (pinfunction "2_2") (pintype "passive"))
      (node (ref "C68") (pin "2") (pinfunction "2_2") (pintype "passive"))
      (node (ref "C69") (pin "2") (pinfunction "2_2") (pintype "passive"))
      (node (ref "C70") (pin "2") (pinfunction "2_2") (pintype "passive"))
      (node (ref "C71") (pin "2") (pinfunction "2_2") (pintype "passive"))
      (node (ref "C72") (pin "2") (pinfunction "2_2") (pintype "passive"))
      (node (ref "C73") (pin "2") (pinfunction "2_2") (pintype "passive"))
      (node (ref "C74") (pin "2") (pinfunction "2_2") (pintype "passive"))
      (node (ref "C75") (pin "2") (pinfunction "2_2") (pintype "passive"))
      (node (ref "C76") (pin "2") (pinfunction "2_2") (pintype "passive"))
      (node (ref "C77") (pin "2") (pinfunction "2_2") (pintype "passive"))
      (node (ref "C78") (pin "2") (pinfunction "2_2") (pintype "passive"))
      (node (ref "C79") (pin "2") (pinfunction "2_2") (pintype "passive"))
      (node (ref "C80") (pin "2") (pinfunction "2_2") (pintype "passive"))
      (node (ref "C81") (pin "2") (pinfunction "2_2") (pintype "passive"))
      (node (ref "C82") (pin "2") (pinfunction "2_2") (pintype "passive"))
      (node (ref "C83") (pin "2") (pinfunction "2_2") (pintype "passive"))
      (node (ref "C84") (pin "2") (pinfunction "2_2") (pintype "passive"))
      (node (ref "C85") (pin "2") (pinfunction "2_2") (pintype "passive"))
      (node (ref "C86") (pin "2") (pinfunction "2_2") (pintype "passive"))
      (node (ref "C87") (pin "2") (pinfunction "2_2") (pintype "passive"))
      (node (ref "C88") (pin "2") (pinfunction "2_2") (pintype "passive"))
      (node (ref "C89") (pin "2") (pinfunction "2_2") (pintype "passive"))
      (node (ref "C9") (pin "2") (pinfunction "2_2") (pintype "passive"))
      (node (ref "C90") (pin "2") (pinfunction "2_2") (pintype "passive"))
      (node (ref "C91") (pin "2") (pinfunction "2_2") (pintype "passive"))
      (node (ref "C92") (pin "2") (pinfunction "2_2") (pintype "passive"))
      (node (ref "C93") (pin "2") (pinfunction "2_2") (pintype "passive"))
      (node (ref "C94") (pin "2") (pinfunction "2_2") (pintype "passive"))
      (node (ref "C95") (pin "2") (pinfunction "2_2") (pintype "passive"))
      (node (ref "C96") (pin "2") (pinfunction "2_2") (pintype "passive"))
      (node (ref "C97") (pin "2") (pinfunction "2_2") (pintype "passive"))
      (node (ref "C98") (pin "2") (pinfunction "2_2") (pintype "passive"))
      (node (ref "C99") (pin "2") (pinfunction "2_2") (pintype "passive"))
      (node (ref "D9") (pin "A") (pinfunction "A_A") (pintype "passive"))
      (node (ref "DBGG") (pin "C") (pinfunction "C_C") (pintype "passive"))
      (node (ref "DBGY") (pin "C") (pinfunction "C_C") (pintype "passive"))
      (node (ref "G2R") (pin "C") (pinfunction "C_C") (pintype "passive"))
      (node (ref "IC1") (pin "34") (pinfunction "IC(L)_34") (pintype "input"))
      (node (ref "IC1") (pin "69") (pinfunction "GND_69") (pintype "power_in"))
      (node (ref "IC10") (pin "1") (pinfunction "~{OE1}_1") (pintype "input"))
      (node (ref "IC10") (pin "10") (pinfunction "GND_10") (pintype "power_in"))
      (node (ref "IC10") (pin "19") (pinfunction "~{OE2}_19") (pintype "input"))
      (node (ref "IC10") (pin "PAD") (pinfunction "GND_PAD") (pintype "power_in"))
      (node (ref "IC11") (pin "1") (pinfunction "GND_1") (pintype "power_in"))
      (node (ref "IC11") (pin "10") (pinfunction "AGND_10") (pintype "power_in"))
      (node (ref "IC11") (pin "11") (pinfunction "GND_11") (pintype "power_in"))
      (node (ref "IC11") (pin "13") (pinfunction "TEST_13") (pintype "input"))
      (node (ref "IC11") (pin "15") (pinfunction "GND_15") (pintype "power_in"))
      (node (ref "IC11") (pin "25") (pinfunction "GND_25") (pintype "power_in"))
      (node (ref "IC11") (pin "35") (pinfunction "GND_35") (pintype "power_in"))
      (node (ref "IC11") (pin "47") (pinfunction "GND_47") (pintype "power_in"))
      (node (ref "IC11") (pin "5") (pinfunction "GND_5") (pintype "power_in"))
      (node (ref "IC11") (pin "51") (pinfunction "GND_51") (pintype "power_in"))
      (node (ref "IC12") (pin "2") (pinfunction "GND_2") (pintype "power_in"))
      (node (ref "IC13") (pin "2") (pinfunction "GND_2") (pintype "bidirectional"))
      (node (ref "IC14") (pin "2") (pinfunction "V-_2") (pintype "power_in"))
      (node (ref "IC15") (pin "11") (pinfunction "GND_11") (pintype "power_in"))
      (node (ref "IC15") (pin "PAD") (pinfunction "GND_PAD") (pintype "power_in"))
      (node (ref "IC16") (pin "11") (pinfunction "GND_11") (pintype "power_in"))
      (node (ref "IC16") (pin "PAD") (pinfunction "GND_PAD") (pintype "power_in"))
      (node (ref "IC17") (pin "11") (pinfunction "GND_11") (pintype "power_in"))
      (node (ref "IC17") (pin "PAD") (pinfunction "GND_PAD") (pintype "power_in"))
      (node (ref "IC18") (pin "2") (pinfunction "V-_2") (pintype "power_in"))
      (node (ref "IC18") (pin "6") (pinfunction "SHDN_6") (pintype "bidirectional"))
      (node (ref "IC19") (pin "2") (pinfunction "V-_2") (pintype "power_in"))
      (node (ref "IC19") (pin "6") (pinfunction "SHDN_6") (pintype "bidirectional"))
      (node (ref "IC2") (pin "6") (pinfunction "GND_6") (pintype "power_in"))
      (node (ref "IC2") (pin "PAD") (pinfunction "POWERPAD_PAD") (pintype "bidirectional"))
      (node (ref "IC2") (pin "V1") (pinfunction "POWERPAD_V1") (pintype "bidirectional"))
      (node (ref "IC2") (pin "V2") (pinfunction "POWERPAD_V2") (pintype "bidirectional"))
      (node (ref "IC2") (pin "V3") (pinfunction "POWERPAD_V3") (pintype "bidirectional"))
      (node (ref "IC2") (pin "V4") (pinfunction "POWERPAD_V4") (pintype "bidirectional"))
      (node (ref "IC2") (pin "V5") (pinfunction "POWERPAD_V5") (pintype "bidirectional"))
      (node (ref "IC2") (pin "V6") (pinfunction "POWERPAD_V6") (pintype "bidirectional"))
      (node (ref "IC2") (pin "V7") (pinfunction "POWERPAD_V7") (pintype "bidirectional"))
      (node (ref "IC2") (pin "V8") (pinfunction "POWERPAD_V8") (pintype "bidirectional"))
      (node (ref "IC20") (pin "2") (pinfunction "V-_2") (pintype "power_in"))
      (node (ref "IC20") (pin "6") (pinfunction "SHDN_6") (pintype "bidirectional"))
      (node (ref "IC21") (pin "19") (pinfunction "TESTEN_19") (pintype "bidirectional"))
      (node (ref "IC21") (pin "PAD") (pinfunction "GND_PAD") (pintype "bidirectional"))
      (node (ref "IC22") (pin "4") (pinfunction "GND_4") (pintype "power_in"))
      (node (ref "IC22") (pin "PAD") (pinfunction "GND_PAD") (pintype "power_in"))
      (node (ref "IC23") (pin "3") (pinfunction "GND_3") (pintype "power_in"))
      (node (ref "IC24") (pin "3") (pinfunction "GND_3") (pintype "power_in"))
      (node (ref "IC25") (pin "2") (pinfunction "GND_2") (pintype "bidirectional"))
      (node (ref "IC3") (pin "12") (pinfunction "GND_12") (pintype "power_in"))
      (node (ref "IC3") (pin "21") (pinfunction "THERMAL_PAD_21") (pintype "bidirectional"))
      (node (ref "IC4") (pin "1") (pinfunction "GND_1") (pintype "power_in"))
      (node (ref "IC4") (pin "PAD") (pinfunction "PAD_PAD") (pintype "power_in"))
      (node (ref "IC5") (pin "1") (pinfunction "GND_1") (pintype "power_in"))
      (node (ref "IC5") (pin "PAD") (pinfunction "PAD_PAD") (pintype "power_in"))
      (node (ref "IC6") (pin "2") (pinfunction "GND_2") (pintype "bidirectional"))
      (node (ref "IC7") (pin "1") (pinfunction "~{OE1}_1") (pintype "input"))
      (node (ref "IC7") (pin "10") (pinfunction "GND_10") (pintype "power_in"))
      (node (ref "IC7") (pin "19") (pinfunction "~{OE2}_19") (pintype "input"))
      (node (ref "IC7") (pin "PAD") (pinfunction "GND_PAD") (pintype "power_in"))
      (node (ref "IC8") (pin "1") (pinfunction "A0_1") (pintype "bidirectional"))
      (node (ref "IC8") (pin "2") (pinfunction "A1_2") (pintype "bidirectional"))
      (node (ref "IC8") (pin "3") (pinfunction "A2_3") (pintype "bidirectional"))
      (node (ref "IC8") (pin "4") (pinfunction "GND_4") (pintype "power_in"))
      (node (ref "IC8") (pin "7") (pinfunction "WP_7") (pintype "bidirectional"))
      (node (ref "IC8") (pin "9") (pinfunction "GND_9") (pintype "power_in"))
      (node (ref "IC9") (pin "10") (pinfunction "AGND_10") (pintype "power_in"))
      (node (ref "IC9") (pin "12") (pinfunction "GND_12") (pintype "power_in"))
      (node (ref "IC9") (pin "14") (pinfunction "RESERVED_14") (pintype "bidirectional"))
      (node (ref "IC9") (pin "26") (pinfunction "GND_26") (pintype "power_in"))
      (node (ref "IC9") (pin "28") (pinfunction "GND_28") (pintype "power_in"))
      (node (ref "IC9") (pin "41") (pinfunction "GND_41") (pintype "power_in"))
      (node (ref "IC9") (pin "53") (pinfunction "GND_53") (pintype "power_in"))
      (node (ref "IC9") (pin "56") (pinfunction "GND_56") (pintype "power_in"))
      (node (ref "IC9") (pin "57") (pinfunction "EPAD_57") (pintype "power_in"))
      (node (ref "IC9") (pin "6") (pinfunction "AGND_6") (pintype "power_in"))
      (node (ref "J3") (pin "2") (pinfunction "2_2") (pintype "bidirectional"))
      (node (ref "J4") (pin "5") (pinfunction "5_5") (pintype "passive"))
      (node (ref "JTAG") (pin "3") (pinfunction "3_3") (pintype "passive"))
      (node (ref "JTAG") (pin "5") (pinfunction "5_5") (pintype "passive"))
      (node (ref "JTAG") (pin "9") (pinfunction "9_9") (pintype "passive"))
      (node (ref "LA") (pin "1") (pinfunction "1_1") (pintype "passive"))
      (node (ref "LA") (pin "19") (pinfunction "19_19") (pintype "passive"))
      (node (ref "LA") (pin "2") (pinfunction "2_2") (pintype "passive"))
      (node (ref "LA") (pin "20") (pinfunction "20_20") (pintype "passive"))
      (node (ref "PCIE-1X1") (pin "A12") (pinfunction "GND_A12") (pintype "power_in"))
      (node (ref "PCIE-1X1") (pin "A15") (pinfunction "GND_A15") (pintype "power_in"))
      (node (ref "PCIE-1X1") (pin "A18") (pinfunction "GND_A18") (pintype "power_in"))
      (node (ref "PCIE-1X1") (pin "A4") (pinfunction "GND_A4") (pintype "power_in"))
      (node (ref "PCIE-1X1") (pin "B13") (pinfunction "GND_B13") (pintype "power_in"))
      (node (ref "PCIE-1X1") (pin "B16") (pinfunction "GND_B16") (pintype "power_in"))
      (node (ref "PCIE-1X1") (pin "B18") (pinfunction "GND_B18") (pintype "power_in"))
      (node (ref "PCIE-1X1") (pin "B4") (pinfunction "GND_B4") (pintype "power_in"))
      (node (ref "PCIE-1X1") (pin "B7") (pinfunction "GND_B7") (pintype "power_in"))
      (node (ref "PGOOD3") (pin "C") (pinfunction "C_C") (pintype "passive"))
      (node (ref "PGOOD5") (pin "C") (pinfunction "C_C") (pintype "passive"))
      (node (ref "PORT1") (pin "C") (pinfunction "C_C") (pintype "passive"))
      (node (ref "PORT2") (pin "C") (pinfunction "C_C") (pintype "passive"))
      (node (ref "PORT3") (pin "C") (pinfunction "C_C") (pintype "passive"))
      (node (ref "PORT4") (pin "C") (pinfunction "C_C") (pintype "passive"))
      (node (ref "R11") (pin "2") (pinfunction "2_2") (pintype "passive"))
      (node (ref "R13") (pin "2") (pinfunction "2_2") (pintype "passive"))
      (node (ref "R14") (pin "2") (pinfunction "2_2") (pintype "passive"))
      (node (ref "R22") (pin "2") (pinfunction "2_2") (pintype "passive"))
      (node (ref "R28") (pin "2") (pinfunction "2_2") (pintype "passive"))
      (node (ref "R29") (pin "2") (pinfunction "2_2") (pintype "passive"))
      (node (ref "R37") (pin "2") (pinfunction "2_2") (pintype "passive"))
      (node (ref "R38") (pin "2") (pinfunction "2_2") (pintype "passive"))
      (node (ref "R39") (pin "2") (pinfunction "2_2") (pintype "passive"))
      (node (ref "R4") (pin "2") (pinfunction "2_2") (pintype "passive"))
      (node (ref "R40") (pin "2") (pinfunction "2_2") (pintype "passive"))
      (node (ref "R41") (pin "2") (pinfunction "2_2") (pintype "passive"))
      (node (ref "R42") (pin "2") (pinfunction "2_2") (pintype "passive"))
      (node (ref "R46") (pin "2") (pinfunction "2_2") (pintype "passive"))
      (node (ref "R49") (pin "2") (pinfunction "2_2") (pintype "passive"))
      (node (ref "R8") (pin "2") (pinfunction "2_2") (pintype "passive"))
      (node (ref "RPDBUG") (pin "2") (pinfunction "2_2") (pintype "passive"))
      (node (ref "RPDBUG") (pin "S1") (pinfunction "SHLD_S1") (pintype "passive"))
      (node (ref "RPDBUG") (pin "S2") (pinfunction "SHLD_S2") (pintype "passive"))
      (node (ref "RPUART") (pin "2") (pinfunction "2_2") (pintype "passive"))
      (node (ref "RPUART") (pin "S1") (pinfunction "SHLD_S1") (pintype "passive"))
      (node (ref "RPUART") (pin "S2") (pinfunction "SHLD_S2") (pintype "passive"))
      (node (ref "SW1") (pin "2") (pinfunction "P$2_2") (pintype "bidirectional"))
      (node (ref "SW2") (pin "2") (pinfunction "P$2_2") (pintype "bidirectional"))
      (node (ref "T1") (pin "2") (pinfunction "S_2") (pintype "passive"))
      (node (ref "T2") (pin "2") (pinfunction "S_2") (pintype "passive"))
      (node (ref "UARG") (pin "C") (pinfunction "C_C") (pintype "passive"))
      (node (ref "UART1") (pin "2") (pinfunction "2_2") (pintype "passive"))
      (node (ref "UART2") (pin "9") (pinfunction "9_9") (pintype "passive"))
      (node (ref "UARY") (pin "C") (pinfunction "C_C") (pintype "passive"))
      (node (ref "X1") (pin "2") (pinfunction "GND_2") (pintype "passive"))
      (node (ref "X1") (pin "4") (pinfunction "GND_4") (pintype "passive"))
      (node (ref "X2") (pin "2") (pinfunction "GND_2") (pintype "passive"))
      (node (ref "X2") (pin "4") (pinfunction "GND_4") (pintype "passive"))
      (node (ref "X3") (pin "2") (pinfunction "GND_2") (pintype "passive"))
      (node (ref "X3") (pin "4") (pinfunction "GND_4") (pintype "passive"))
      (node (ref "X4") (pin "2") (pinfunction "GND_2") (pintype "passive"))
      (node (ref "X4") (pin "4") (pinfunction "GND_4") (pintype "passive"))
    )
    (net (code "80") (name "GPIO2") (class "Default")
      (node (ref "IC21") (pin "4") (pinfunction "GPIO2_4") (pintype "bidirectional"))
      (node (ref "R54") (pin "1") (pinfunction "1_1") (pintype "passive"))
    )
    (net (code "81") (name "GPIO4") (class "Default")
      (node (ref "IC21") (pin "6") (pinfunction "GPIO4_6") (pintype "bidirectional"))
      (node (ref "R59") (pin "1") (pinfunction "1_1") (pintype "passive"))
    )
    (net (code "82") (name "GPIO5") (class "Default")
      (node (ref "IC21") (pin "7") (pinfunction "GPIO5_7") (pintype "bidirectional"))
      (node (ref "IC23") (pin "4") (pinfunction "Y_4") (pintype "output"))
    )
    (net (code "83") (name "GPIO6") (class "Default")
      (node (ref "IC21") (pin "8") (pinfunction "GPIO6_8") (pintype "bidirectional"))
      (node (ref "R60") (pin "1") (pinfunction "1_1") (pintype "passive"))
    )
    (net (code "84") (name "GPIO7") (class "Default")
      (node (ref "IC21") (pin "9") (pinfunction "GPIO7_9") (pintype "bidirectional"))
      (node (ref "R55") (pin "1") (pinfunction "1_1") (pintype "passive"))
    )
    (net (code "85") (name "GPIO8") (class "Default")
      (node (ref "IC21") (pin "11") (pinfunction "GPIO8_11") (pintype "bidirectional"))
      (node (ref "R56") (pin "1") (pinfunction "1_1") (pintype "passive"))
    )
    (net (code "86") (name "GPIO12") (class "Default")
      (node (ref "IC21") (pin "15") (pinfunction "GPIO12_15") (pintype "bidirectional"))
      (node (ref "R62") (pin "1") (pinfunction "1_1") (pintype "passive"))
    )
    (net (code "87") (name "GPIO13") (class "Default")
      (node (ref "IC21") (pin "16") (pinfunction "GPIO13_16") (pintype "bidirectional"))
      (node (ref "IC24") (pin "4") (pinfunction "Y_4") (pintype "output"))
    )
    (net (code "88") (name "GPIO14") (class "Default")
      (node (ref "IC21") (pin "17") (pinfunction "GPIO14_17") (pintype "bidirectional"))
      (node (ref "R63") (pin "1") (pinfunction "1_1") (pintype "passive"))
    )
    (net (code "89") (name "GPIO15") (class "Default")
      (node (ref "IC21") (pin "18") (pinfunction "GPIO15_18") (pintype "bidirectional"))
      (node (ref "R57") (pin "1") (pinfunction "1_1") (pintype "passive"))
    )
    (net (code "90") (name "GPIO16") (class "Default")
      (node (ref "IC21") (pin "27") (pinfunction "GPIO16_27") (pintype "bidirectional"))
      (node (ref "R58") (pin "1") (pinfunction "1_1") (pintype "passive"))
    )
    (net (code "91") (name "JTAG_TCK") (class "Default")
      (node (ref "PCIE-1X1") (pin "A5") (pinfunction "JTAG_TCK_A5") (pintype "bidirectional"))
    )
    (net (code "92") (name "JTAG_TDITDO") (class "Default")
      (node (ref "J1") (pin "1") (pinfunction "P$1_1") (pintype "bidirectional"))
      (node (ref "PCIE-1X1") (pin "A6") (pinfunction "JTAG_TDI_A6") (pintype "bidirectional"))
    )
    (net (code "93") (name "JTAG_TDO") (class "Default")
      (node (ref "J1") (pin "2") (pinfunction "P$2_2") (pintype "bidirectional"))
      (node (ref "PCIE-1X1") (pin "A7") (pinfunction "JTAG_TDO_A7") (pintype "bidirectional"))
    )
    (net (code "94") (name "JTAG_TMS") (class "Default")
      (node (ref "PCIE-1X1") (pin "A8") (pinfunction "JTAG_TMS_A8") (pintype "bidirectional"))
    )
    (net (code "95") (name "JTAG_~{TRST}") (class "Default")
      (node (ref "PCIE-1X1") (pin "B9") (pinfunction "~{JTAG_TRST}_B9") (pintype "bidirectional"))
    )
    (net (code "96") (name "KEY") (class "Default")
      (node (ref "JTAG") (pin "7") (pinfunction "7_7") (pintype "passive"))
    )
    (net (code "97") (name "Net-(1V8-PadA)") (class "Default")
      (node (ref "1V8") (pin "A") (pinfunction "A_A") (pintype "passive"))
      (node (ref "R48") (pin "2") (pinfunction "2_2") (pintype "passive"))
    )
    (net (code "98") (name "Net-(2V5-PadA)") (class "Default")
      (node (ref "2V5") (pin "A") (pinfunction "A_A") (pintype "passive"))
      (node (ref "R44") (pin "2") (pinfunction "2_2") (pintype "passive"))
    )
    (net (code "99") (name "Net-(3V3-PadA)") (class "Default")
      (node (ref "3V3") (pin "A") (pinfunction "A_A") (pintype "passive"))
      (node (ref "R43") (pin "2") (pinfunction "2_2") (pintype "passive"))
    )
    (net (code "100") (name "Net-(D10-PadC)") (class "Default")
      (node (ref "D10") (pin "C") (pinfunction "C_C") (pintype "passive"))
      (node (ref "R22") (pin "1") (pinfunction "1_1") (pintype "passive"))
    )
    (net (code "101") (name "Net-(DBGG-PadA)") (class "Default")
      (node (ref "DBGG") (pin "A") (pinfunction "A_A") (pintype "passive"))
      (node (ref "R57") (pin "2") (pinfunction "2_2") (pintype "passive"))
    )
    (net (code "102") (name "Net-(DBGY-PadA)") (class "Default")
      (node (ref "DBGY") (pin "A") (pinfunction "A_A") (pintype "passive"))
      (node (ref "R58") (pin "2") (pinfunction "2_2") (pintype "passive"))
    )
    (net (code "103") (name "Net-(G2R-PadA)") (class "Default")
      (node (ref "G2R") (pin "A") (pinfunction "A_A") (pintype "passive"))
      (node (ref "R54") (pin "2") (pinfunction "2_2") (pintype "passive"))
    )
    (net (code "104") (name "Net-(IC1A-RREF)") (class "Default")
      (node (ref "IC1") (pin "33") (pinfunction "RREF_33") (pintype "bidirectional"))
      (node (ref "R4") (pin "1") (pinfunction "1_1") (pintype "passive"))
    )
    (net (code "105") (name "Net-(IC1A-XT1)") (class "Default")
      (node (ref "C43") (pin "1") (pinfunction "1_1") (pintype "passive"))
      (node (ref "IC1") (pin "31") (pinfunction "XT1_31") (pintype "output"))
      (node (ref "X1") (pin "1") (pinfunction "1_1") (pintype "passive"))
    )
    (net (code "106") (name "Net-(IC1A-XT2)") (class "Default")
      (node (ref "C44") (pin "1") (pinfunction "1_1") (pintype "passive"))
      (node (ref "IC1") (pin "30") (pinfunction "XT2_30") (pintype "input"))
      (node (ref "X1") (pin "3") (pinfunction "2_3") (pintype "passive"))
    )
    (net (code "107") (name "Net-(IC2-PH)") (class "Default")
      (node (ref "C50") (pin "2") (pinfunction "2_2") (pintype "passive"))
      (node (ref "D9") (pin "C") (pinfunction "C_C") (pintype "passive"))
      (node (ref "IC2") (pin "8") (pinfunction "PH_8") (pintype "output"))
      (node (ref "L1") (pin "2") (pinfunction "2_2") (pintype "passive"))
    )
    (net (code "108") (name "Net-(IC4-ILIM)") (class "Default")
      (node (ref "IC4") (pin "7") (pinfunction "ILIM_7") (pintype "output"))
      (node (ref "R13") (pin "1") (pinfunction "1_1") (pintype "passive"))
    )
    (net (code "109") (name "Net-(IC5-ILIM)") (class "Default")
      (node (ref "IC5") (pin "7") (pinfunction "ILIM_7") (pintype "output"))
      (node (ref "R14") (pin "1") (pinfunction "1_1") (pintype "passive"))
    )
    (net (code "110") (name "Net-(IC9-XTALIN)") (class "Default")
      (node (ref "C75") (pin "1") (pinfunction "1_1") (pintype "passive"))
      (node (ref "IC9") (pin "5") (pinfunction "XTALIN_5") (pintype "input"))
      (node (ref "X2") (pin "1") (pinfunction "1_1") (pintype "passive"))
    )
    (net (code "111") (name "Net-(IC9-XTALOUT)") (class "Default")
      (node (ref "C76") (pin "1") (pinfunction "1_1") (pintype "passive"))
      (node (ref "IC9") (pin "4") (pinfunction "XTALOUT_4") (pintype "output"))
      (node (ref "X2") (pin "3") (pinfunction "2_3") (pintype "passive"))
    )
    (net (code "112") (name "Net-(IC11-OSCI)") (class "Default")
      (node (ref "C85") (pin "1") (pinfunction "1_1") (pintype "passive"))
      (node (ref "IC11") (pin "2") (pinfunction "OSCI_2") (pintype "input"))
      (node (ref "X3") (pin "1") (pinfunction "1_1") (pintype "passive"))
    )
    (net (code "113") (name "Net-(IC11-OSCO)") (class "Default")
      (node (ref "C86") (pin "1") (pinfunction "1_1") (pintype "passive"))
      (node (ref "IC11") (pin "3") (pinfunction "OSCO_3") (pintype "output"))
      (node (ref "X3") (pin "3") (pinfunction "2_3") (pintype "passive"))
    )
    (net (code "114") (name "Net-(IC11-REF)") (class "Default")
      (node (ref "IC11") (pin "6") (pinfunction "REF_6") (pintype "input"))
      (node (ref "R29") (pin "1") (pinfunction "1_1") (pintype "passive"))
    )
    (net (code "115") (name "Net-(IC12-DO)") (class "Default")
      (node (ref "IC12") (pin "1") (pinfunction "DO_1") (pintype "output"))
      (node (ref "R23") (pin "1") (pinfunction "1_1") (pintype "passive"))
    )
    (net (code "116") (name "Net-(IC18--IN)") (class "Default")
      (node (ref "IC18") (pin "1") (pinfunction "-IN_1") (pintype "input"))
      (node (ref "R36") (pin "2") (pinfunction "2_2") (pintype "passive"))
      (node (ref "R40") (pin "1") (pinfunction "1_1") (pintype "passive"))
    )
    (net (code "117") (name "Net-(IC18-OUT)") (class "Default")
      (node (ref "IC18") (pin "5") (pinfunction "OUT_5") (pintype "output"))
      (node (ref "R43") (pin "1") (pinfunction "1_1") (pintype "passive"))
    )
    (net (code "118") (name "Net-(IC19--IN)") (class "Default")
      (node (ref "IC19") (pin "1") (pinfunction "-IN_1") (pintype "input"))
      (node (ref "R45") (pin "2") (pinfunction "2_2") (pintype "passive"))
      (node (ref "R46") (pin "1") (pinfunction "1_1") (pintype "passive"))
    )
    (net (code "119") (name "Net-(IC19-OUT)") (class "Default")
      (node (ref "IC19") (pin "5") (pinfunction "OUT_5") (pintype "output"))
      (node (ref "R44") (pin "1") (pinfunction "1_1") (pintype "passive"))
    )
    (net (code "120") (name "Net-(IC20--IN)") (class "Default")
      (node (ref "IC20") (pin "1") (pinfunction "-IN_1") (pintype "input"))
      (node (ref "R47") (pin "2") (pinfunction "2_2") (pintype "passive"))
      (node (ref "R49") (pin "1") (pinfunction "1_1") (pintype "passive"))
    )
    (net (code "121") (name "Net-(IC20-OUT)") (class "Default")
      (node (ref "IC20") (pin "5") (pinfunction "OUT_5") (pintype "output"))
      (node (ref "R48") (pin "1") (pinfunction "1_1") (pintype "passive"))
    )
    (net (code "122") (name "Net-(IC21-GPIO0)") (class "Default")
      (node (ref "IC21") (pin "2") (pinfunction "GPIO0_2") (pintype "bidirectional"))
      (node (ref "J3") (pin "1") (pinfunction "1_1") (pintype "bidirectional"))
    )
    (net (code "123") (name "Net-(IC21-GPIO1)") (class "Default")
      (node (ref "IC21") (pin "3") (pinfunction "GPIO1_3") (pintype "bidirectional"))
      (node (ref "J3") (pin "3") (pinfunction "3_3") (pintype "bidirectional"))
    )
    (net (code "124") (name "Net-(IC21-USB_DM)") (class "Default")
      (node (ref "IC21") (pin "46") (pinfunction "USB_DM_46") (pintype "bidirectional"))
      (node (ref "R51") (pin "2") (pinfunction "2_2") (pintype "passive"))
    )
    (net (code "125") (name "Net-(IC21-USB_DP)") (class "Default")
      (node (ref "IC21") (pin "47") (pinfunction "USB_DP_47") (pintype "bidirectional"))
      (node (ref "R52") (pin "1") (pinfunction "1_1") (pintype "passive"))
    )
    (net (code "126") (name "Net-(IC21-XIN)") (class "Default")
      (node (ref "C127") (pin "1") (pinfunction "1_1") (pintype "passive"))
      (node (ref "IC21") (pin "20") (pinfunction "XIN_20") (pintype "bidirectional"))
      (node (ref "X4") (pin "1") (pinfunction "1_1") (pintype "passive"))
    )
    (net (code "127") (name "Net-(IC21-XOUT)") (class "Default")
      (node (ref "IC21") (pin "21") (pinfunction "XOUT_21") (pintype "bidirectional"))
      (node (ref "R50") (pin "1") (pinfunction "1_1") (pintype "passive"))
    )
    (net (code "128") (name "Net-(IC23-A)") (class "Default")
      (node (ref "IC23") (pin "2") (pinfunction "A_2") (pintype "input"))
      (node (ref "R61") (pin "1") (pinfunction "1_1") (pintype "passive"))
    )
    (net (code "129") (name "Net-(IC24-A)") (class "Default")
      (node (ref "IC24") (pin "2") (pinfunction "A_2") (pintype "input"))
      (node (ref "R64") (pin "1") (pinfunction "1_1") (pintype "passive"))
    )
    (net (code "130") (name "Net-(J7-P$2)") (class "Default")
      (node (ref "J7") (pin "2") (pinfunction "P$2_2") (pintype "bidirectional"))
      (node (ref "JTAG") (pin "1") (pinfunction "1_1") (pintype "passive"))
    )
    (net (code "131") (name "Net-(PGOOD3-PadA)") (class "Default")
      (node (ref "PGOOD3") (pin "A") (pinfunction "A_A") (pintype "passive"))
      (node (ref "R5") (pin "2") (pinfunction "2_2") (pintype "passive"))
    )
    (net (code "132") (name "Net-(PGOOD5-PadA)") (class "Default")
      (node (ref "PGOOD5") (pin "A") (pinfunction "A_A") (pintype "passive"))
      (node (ref "R12") (pin "2") (pinfunction "2_2") (pintype "passive"))
    )
    (net (code "133") (name "Net-(PORT1-PadA)") (class "Default")
      (node (ref "PORT1") (pin "A") (pinfunction "A_A") (pintype "passive"))
      (node (ref "R17") (pin "2") (pinfunction "2_2") (pintype "passive"))
    )
    (net (code "134") (name "Net-(PORT2-PadA)") (class "Default")
      (node (ref "PORT2") (pin "A") (pinfunction "A_A") (pintype "passive"))
      (node (ref "R15") (pin "2") (pinfunction "2_2") (pintype "passive"))
    )
    (net (code "135") (name "Net-(PORT3-PadA)") (class "Default")
      (node (ref "PORT3") (pin "A") (pinfunction "A_A") (pintype "passive"))
      (node (ref "R18") (pin "2") (pinfunction "2_2") (pintype "passive"))
    )
    (net (code "136") (name "Net-(PORT4-PadA)") (class "Default")
      (node (ref "PORT4") (pin "A") (pinfunction "A_A") (pintype "passive"))
      (node (ref "R16") (pin "2") (pinfunction "2_2") (pintype "passive"))
    )
    (net (code "137") (name "Net-(R55-Pad2)") (class "Default")
      (node (ref "R55") (pin "2") (pinfunction "2_2") (pintype "passive"))
      (node (ref "UARG") (pin "A") (pinfunction "A_A") (pintype "passive"))
    )
    (net (code "138") (name "Net-(R56-Pad2)") (class "Default")
      (node (ref "R56") (pin "2") (pinfunction "2_2") (pintype "passive"))
      (node (ref "UARY") (pin "A") (pinfunction "A_A") (pintype "passive"))
    )
    (net (code "139") (name "Net-(SW2-P$1)") (class "Default")
      (node (ref "R53") (pin "1") (pinfunction "1_1") (pintype "passive"))
      (node (ref "SW2") (pin "1") (pinfunction "P$1_1") (pintype "bidirectional"))
    )
    (net (code "140") (name "Net-(T1-D)") (class "Default")
      (node (ref "R34") (pin "2") (pinfunction "2_2") (pintype "passive"))
      (node (ref "T1") (pin "3") (pinfunction "D_3") (pintype "passive"))
    )
    (net (code "141") (name "Net-(T2-D)") (class "Default")
      (node (ref "R35") (pin "2") (pinfunction "2_2") (pintype "passive"))
      (node (ref "T2") (pin "3") (pinfunction "D_3") (pintype "passive"))
    )
    (net (code "142") (name "Net-(X4-2)") (class "Default")
      (node (ref "C128") (pin "1") (pinfunction "1_1") (pintype "passive"))
      (node (ref "R50") (pin "2") (pinfunction "2_2") (pintype "passive"))
      (node (ref "X4") (pin "3") (pinfunction "2_3") (pintype "passive"))
    )
    (net (code "143") (name "PA0") (class "Default")
      (node (ref "IC9") (pin "33") (pinfunction "PA0_33") (pintype "bidirectional"))
    )
    (net (code "144") (name "PA1") (class "Default")
      (node (ref "D10") (pin "A") (pinfunction "A_A") (pintype "passive"))
      (node (ref "IC9") (pin "34") (pinfunction "PA1_34") (pintype "bidirectional"))
    )
    (net (code "145") (name "PA2") (class "Default")
      (node (ref "IC9") (pin "35") (pinfunction "PA2_35") (pintype "bidirectional"))
    )
    (net (code "146") (name "PA3") (class "Default")
      (node (ref "IC9") (pin "36") (pinfunction "PA3_36") (pintype "bidirectional"))
    )
    (net (code "147") (name "PA4") (class "Default")
      (node (ref "IC9") (pin "37") (pinfunction "PA4_37") (pintype "bidirectional"))
    )
    (net (code "148") (name "PA5") (class "Default")
      (node (ref "IC9") (pin "38") (pinfunction "PA5_38") (pintype "bidirectional"))
    )
    (net (code "149") (name "PA6") (class "Default")
      (node (ref "IC9") (pin "39") (pinfunction "PA6_39") (pintype "bidirectional"))
    )
    (net (code "150") (name "PA7") (class "Default")
      (node (ref "IC9") (pin "40") (pinfunction "PA7_40") (pintype "bidirectional"))
    )
    (net (code "151") (name "PB0") (class "Default")
      (node (ref "IC9") (pin "18") (pinfunction "PB0_18") (pintype "bidirectional"))
      (node (ref "RN3") (pin "A2") (pinfunction "2_A2") (pintype "passive"))
    )
    (net (code "152") (name "PB1") (class "Default")
      (node (ref "IC9") (pin "19") (pinfunction "PB1_19") (pintype "bidirectional"))
      (node (ref "RN3") (pin "B2") (pinfunction "2_B2") (pintype "passive"))
    )
    (net (code "153") (name "PB2") (class "Default")
      (node (ref "IC9") (pin "20") (pinfunction "PB2_20") (pintype "bidirectional"))
      (node (ref "RN3") (pin "C2") (pinfunction "2_C2") (pintype "passive"))
    )
    (net (code "154") (name "PB3") (class "Default")
      (node (ref "IC9") (pin "21") (pinfunction "PB3_21") (pintype "bidirectional"))
      (node (ref "RN3") (pin "D2") (pinfunction "2_D2") (pintype "passive"))
    )
    (net (code "155") (name "PB4") (class "Default")
      (node (ref "IC9") (pin "22") (pinfunction "PB4_22") (pintype "bidirectional"))
      (node (ref "RN4") (pin "A2") (pinfunction "2_A2") (pintype "passive"))
    )
    (net (code "156") (name "PB5") (class "Default")
      (node (ref "IC9") (pin "23") (pinfunction "PB5_23") (pintype "bidirectional"))
      (node (ref "RN4") (pin "B2") (pinfunction "2_B2") (pintype "passive"))
    )
    (net (code "157") (name "PB6") (class "Default")
      (node (ref "IC9") (pin "24") (pinfunction "PB6_24") (pintype "bidirectional"))
      (node (ref "RN4") (pin "C2") (pinfunction "2_C2") (pintype "passive"))
    )
    (net (code "158") (name "PB7") (class "Default")
      (node (ref "IC9") (pin "25") (pinfunction "PB7_25") (pintype "bidirectional"))
      (node (ref "RN4") (pin "D2") (pinfunction "2_D2") (pintype "passive"))
    )
    (net (code "159") (name "PCIE_3V3") (class "Default")
      (node (ref "C11") (pin "1") (pinfunction "1_1") (pintype "passive"))
      (node (ref "C12") (pin "1") (pinfunction "1_1") (pintype "passive"))
      (node (ref "C13") (pin "1") (pinfunction "1_1") (pintype "passive"))
      (node (ref "C14") (pin "1") (pinfunction "1_1") (pintype "passive"))
      (node (ref "C15") (pin "1") (pinfunction "1_1") (pintype "passive"))
      (node (ref "C16") (pin "1") (pinfunction "1_1") (pintype "passive"))
      (node (ref "J2") (pin "1") (pinfunction "1_1") (pintype "bidirectional"))
      (node (ref "PCIE-1X1") (pin "A10") (pinfunction "+3V3_A10") (pintype "power_in"))
      (node (ref "PCIE-1X1") (pin "A9") (pinfunction "+3V3_A9") (pintype "power_in"))
      (node (ref "PCIE-1X1") (pin "B8") (pinfunction "+3V3_B8") (pintype "power_in"))
    )
    (net (code "160") (name "PCIE_CTX_N") (class "Default")
      (node (ref "C8") (pin "2") (pinfunction "2_2") (pintype "passive"))
      (node (ref "PCIE-1X1") (pin "A17") (pinfunction "PER_N0_A17") (pintype "bidirectional"))
    )
    (net (code "161") (name "PCIE_CTX_P") (class "Default")
      (node (ref "C7") (pin "2") (pinfunction "2_2") (pintype "passive"))
      (node (ref "PCIE-1X1") (pin "A16") (pinfunction "PER_P0_A16") (pintype "bidirectional"))
    )
    (net (code "162") (name "PCIE_REFCLK_N") (class "Default")
      (node (ref "IC1") (pin "4") (pinfunction "PECLKP_4") (pintype "input"))
      (node (ref "PCIE-1X1") (pin "A14") (pinfunction "REFCLK_N_A14") (pintype "bidirectional"))
    )
    (net (code "163") (name "PCIE_REFCLK_P") (class "Default")
      (node (ref "IC1") (pin "5") (pinfunction "PECLKN_5") (pintype "input"))
      (node (ref "PCIE-1X1") (pin "A13") (pinfunction "REFCLK_P_A13") (pintype "bidirectional"))
    )
    (net (code "164") (name "PCIE_RX_N") (class "Default")
      (node (ref "IC1") (pin "11") (pinfunction "PERXN_11") (pintype "input"))
      (node (ref "PCIE-1X1") (pin "B15") (pinfunction "PET_N0_B15") (pintype "bidirectional"))
    )
    (net (code "165") (name "PCIE_RX_P") (class "Default")
      (node (ref "IC1") (pin "10") (pinfunction "PERXP_10") (pintype "input"))
      (node (ref "PCIE-1X1") (pin "B14") (pinfunction "PET_P0_B14") (pintype "bidirectional"))
    )
    (net (code "166") (name "PCIE_TX_N") (class "Default")
      (node (ref "C8") (pin "1") (pinfunction "1_1") (pintype "passive"))
      (node (ref "IC1") (pin "8") (pinfunction "PETXN_8") (pintype "output"))
    )
    (net (code "167") (name "PCIE_TX_P") (class "Default")
      (node (ref "C7") (pin "1") (pinfunction "1_1") (pintype "passive"))
      (node (ref "IC1") (pin "7") (pinfunction "PETXP_7") (pintype "output"))
    )
    (net (code "168") (name "PD0") (class "Default")
      (node (ref "IC9") (pin "45") (pinfunction "PD0_45") (pintype "bidirectional"))
      (node (ref "RN9") (pin "A2") (pinfunction "2_A2") (pintype "passive"))
    )
    (net (code "169") (name "PD1") (class "Default")
      (node (ref "IC9") (pin "46") (pinfunction "PD1_46") (pintype "bidirectional"))
      (node (ref "RN9") (pin "B2") (pinfunction "2_B2") (pintype "passive"))
    )
    (net (code "170") (name "PD2") (class "Default")
      (node (ref "IC9") (pin "47") (pinfunction "PD2_47") (pintype "bidirectional"))
      (node (ref "RN9") (pin "C2") (pinfunction "2_C2") (pintype "passive"))
    )
    (net (code "171") (name "PD3") (class "Default")
      (node (ref "IC9") (pin "48") (pinfunction "PD3_48") (pintype "bidirectional"))
      (node (ref "RN9") (pin "D2") (pinfunction "2_D2") (pintype "passive"))
    )
    (net (code "172") (name "PD4") (class "Default")
      (node (ref "IC9") (pin "49") (pinfunction "PD4_49") (pintype "bidirectional"))
      (node (ref "RN10") (pin "A2") (pinfunction "2_A2") (pintype "passive"))
    )
    (net (code "173") (name "PD5") (class "Default")
      (node (ref "IC9") (pin "50") (pinfunction "PD5_50") (pintype "bidirectional"))
      (node (ref "RN10") (pin "B2") (pinfunction "2_B2") (pintype "passive"))
    )
    (net (code "174") (name "PD6") (class "Default")
      (node (ref "IC9") (pin "51") (pinfunction "PD6_51") (pintype "bidirectional"))
      (node (ref "RN10") (pin "C2") (pinfunction "2_C2") (pintype "passive"))
    )
    (net (code "175") (name "PD7") (class "Default")
      (node (ref "IC9") (pin "52") (pinfunction "PD7_52") (pintype "bidirectional"))
      (node (ref "RN10") (pin "D2") (pinfunction "2_D2") (pintype "passive"))
    )
    (net (code "176") (name "QSPI_SCLK") (class "Default")
      (node (ref "IC21") (pin "52") (pinfunction "QSPI_SCLK_52") (pintype "bidirectional"))
      (node (ref "IC22") (pin "6") (pinfunction "CLK_6") (pintype "bidirectional"))
    )
    (net (code "177") (name "QSPI_SD0") (class "Default")
      (node (ref "IC21") (pin "53") (pinfunction "QSPI_SD0_53") (pintype "bidirectional"))
      (node (ref "IC22") (pin "5") (pinfunction "DI/IO0_5") (pintype "bidirectional"))
    )
    (net (code "178") (name "QSPI_SD1") (class "Default")
      (node (ref "IC21") (pin "55") (pinfunction "QSPI_SD1_55") (pintype "bidirectional"))
      (node (ref "IC22") (pin "2") (pinfunction "DO/IO1_2") (pintype "bidirectional"))
    )
    (net (code "179") (name "QSPI_SD2") (class "Default")
      (node (ref "IC21") (pin "54") (pinfunction "QSPI_SD2_54") (pintype "bidirectional"))
      (node (ref "IC22") (pin "3") (pinfunction "~{WP}/IO2_3") (pintype "bidirectional"))
    )
    (net (code "180") (name "QSPI_SD3") (class "Default")
      (node (ref "IC21") (pin "51") (pinfunction "QSPI_SD3_51") (pintype "bidirectional"))
      (node (ref "IC22") (pin "7") (pinfunction "~{HOLD}/IO3_7") (pintype "bidirectional"))
    )
    (net (code "181") (name "QSPI_SS") (class "Default")
      (node (ref "IC21") (pin "56") (pinfunction "QSPI_SS_N_56") (pintype "bidirectional"))
      (node (ref "IC22") (pin "1") (pinfunction "~{CS}_1") (pintype "bidirectional"))
      (node (ref "R53") (pin "2") (pinfunction "2_2") (pintype "passive"))
    )
    (net (code "182") (name "RESET") (class "Default")
      (node (ref "C65") (pin "1") (pinfunction "1_1") (pintype "passive"))
      (node (ref "D8") (pin "A") (pinfunction "A_A") (pintype "passive"))
      (node (ref "IC9") (pin "42") (pinfunction "~{RESET}_42") (pintype "input"))
      (node (ref "R19") (pin "2") (pinfunction "2_2") (pintype "passive"))
    )
    (net (code "183") (name "RUN") (class "Default")
      (node (ref "IC21") (pin "26") (pinfunction "RUN_26") (pintype "bidirectional"))
      (node (ref "R65") (pin "2") (pinfunction "2_2") (pintype "passive"))
      (node (ref "SW1") (pin "1") (pinfunction "P$1_1") (pintype "bidirectional"))
    )
    (net (code "184") (name "RXD1") (class "Default")
      (node (ref "IC11") (pin "39") (pinfunction "CDBUS1_39") (pintype "bidirectional"))
      (node (ref "IC16") (pin "13") (pinfunction "B7_13") (pintype "bidirectional"))
    )
    (net (code "185") (name "RXD1_OUT") (class "Default")
      (node (ref "IC16") (pin "8") (pinfunction "A7_8") (pintype "bidirectional"))
      (node (ref "UART1") (pin "8") (pinfunction "8_8") (pintype "passive"))
    )
    (net (code "186") (name "RXD2") (class "Default")
      (node (ref "IC11") (pin "52") (pinfunction "DDBUS1_52") (pintype "bidirectional"))
      (node (ref "IC17") (pin "13") (pinfunction "B7_13") (pintype "bidirectional"))
    )
    (net (code "187") (name "RXD2_OUT") (class "Default")
      (node (ref "IC17") (pin "8") (pinfunction "A7_8") (pintype "bidirectional"))
      (node (ref "UART2") (pin "3") (pinfunction "3_3") (pintype "passive"))
    )
    (net (code "188") (name "SCL") (class "Default")
      (node (ref "IC8") (pin "6") (pinfunction "SCL_6") (pintype "bidirectional"))
      (node (ref "IC9") (pin "15") (pinfunction "SCL_15") (pintype "bidirectional"))
      (node (ref "R20") (pin "1") (pinfunction "1_1") (pintype "passive"))
    )
    (net (code "189") (name "SDA") (class "Default")
      (node (ref "IC8") (pin "5") (pinfunction "SDA_5") (pintype "bidirectional"))
      (node (ref "IC9") (pin "16") (pinfunction "SDA_16") (pintype "bidirectional"))
      (node (ref "R21") (pin "1") (pinfunction "1_1") (pintype "passive"))
    )
    (net (code "190") (name "SMCLK") (class "Default")
      (node (ref "PCIE-1X1") (pin "B5") (pinfunction "SMCLK_B5") (pintype "bidirectional"))
    )
    (net (code "191") (name "SMDAT") (class "Default")
      (node (ref "PCIE-1X1") (pin "B6") (pinfunction "SMDAT_B6") (pintype "bidirectional"))
    )
    (net (code "192") (name "SPI_MISO") (class "Default")
      (node (ref "IC1") (pin "19") (pinfunction "SPISI_19") (pintype "bidirectional"))
    )
    (net (code "193") (name "SPI_MOSI") (class "Default")
      (node (ref "IC1") (pin "16") (pinfunction "SPISO_16") (pintype "bidirectional"))
    )
    (net (code "194") (name "SPI_SCK") (class "Default")
      (node (ref "IC1") (pin "18") (pinfunction "SPISCK_18") (pintype "bidirectional"))
    )
    (net (code "195") (name "SS") (class "Default")
      (node (ref "C49") (pin "1") (pinfunction "1_1") (pintype "passive"))
      (node (ref "IC3") (pin "15") (pinfunction "SS_15") (pintype "bidirectional"))
    )
    (net (code "196") (name "SWCLK") (class "Default")
      (node (ref "IC21") (pin "24") (pinfunction "SWCLK_24") (pintype "bidirectional"))
    )
    (net (code "197") (name "SWDIO") (class "Default")
      (node (ref "IC21") (pin "25") (pinfunction "SWDIO_25") (pintype "bidirectional"))
    )
    (net (code "198") (name "TCK{slash}SCK") (class "Default")
      (node (ref "IC11") (pin "26") (pinfunction "BDBUS0_26") (pintype "bidirectional"))
      (node (ref "IC15") (pin "16") (pinfunction "B4_16") (pintype "bidirectional"))
    )
    (net (code "199") (name "TCK{slash}SCK_OUT") (class "Default")
      (node (ref "IC15") (pin "5") (pinfunction "A4_5") (pintype "bidirectional"))
      (node (ref "JTAG") (pin "4") (pinfunction "4_4") (pintype "passive"))
    )
    (net (code "200") (name "TDI{slash}DO") (class "Default")
      (node (ref "IC11") (pin "27") (pinfunction "BDBUS1_27") (pintype "bidirectional"))
      (node (ref "IC15") (pin "17") (pinfunction "B3_17") (pintype "bidirectional"))
    )
    (net (code "201") (name "TDI{slash}DO_OUT") (class "Default")
      (node (ref "IC15") (pin "4") (pinfunction "A3_4") (pintype "bidirectional"))
      (node (ref "JTAG") (pin "8") (pinfunction "8_8") (pintype "passive"))
    )
    (net (code "202") (name "TDO{slash}DI") (class "Default")
      (node (ref "IC11") (pin "28") (pinfunction "BDBUS2_28") (pintype "bidirectional"))
      (node (ref "IC15") (pin "18") (pinfunction "B2_18") (pintype "bidirectional"))
    )
    (net (code "203") (name "TDO{slash}DI_OUT") (class "Default")
      (node (ref "IC15") (pin "3") (pinfunction "A2_3") (pintype "bidirectional"))
      (node (ref "JTAG") (pin "6") (pinfunction "6_6") (pintype "passive"))
    )
    (net (code "204") (name "TMS{slash}CS") (class "Default")
      (node (ref "IC11") (pin "29") (pinfunction "BDBUS3_29") (pintype "bidirectional"))
      (node (ref "IC15") (pin "20") (pinfunction "B1_20") (pintype "bidirectional"))
    )
    (net (code "205") (name "TMS{slash}CS_OUT") (class "Default")
      (node (ref "IC15") (pin "1") (pinfunction "A1_1") (pintype "bidirectional"))
      (node (ref "JTAG") (pin "2") (pinfunction "2_2") (pintype "passive"))
    )
    (net (code "206") (name "TRESET") (class "Default")
      (node (ref "IC11") (pin "30") (pinfunction "BDBUS4_30") (pintype "bidirectional"))
    )
    (net (code "207") (name "TRESET_OUT") (class "Default")
      (node (ref "JTAG") (pin "10") (pinfunction "10_10") (pintype "passive"))
    )
    (net (code "208") (name "TXD1") (class "Default")
      (node (ref "IC11") (pin "38") (pinfunction "CDBUS0_38") (pintype "bidirectional"))
      (node (ref "IC16") (pin "12") (pinfunction "B8_12") (pintype "bidirectional"))
    )
    (net (code "209") (name "TXD1_OUT") (class "Default")
      (node (ref "IC16") (pin "9") (pinfunction "A8_9") (pintype "bidirectional"))
      (node (ref "UART1") (pin "6") (pinfunction "6_6") (pintype "passive"))
    )
    (net (code "210") (name "TXD2") (class "Default")
      (node (ref "IC11") (pin "48") (pinfunction "DDBUS0_48") (pintype "bidirectional"))
      (node (ref "IC17") (pin "12") (pinfunction "B8_12") (pintype "bidirectional"))
    )
    (net (code "211") (name "TXD2_OUT") (class "Default")
      (node (ref "IC17") (pin "9") (pinfunction "A8_9") (pintype "bidirectional"))
      (node (ref "UART2") (pin "5") (pinfunction "5_5") (pintype "passive"))
    )
    (net (code "212") (name "UART1_RX") (class "Default")
      (node (ref "R60") (pin "2") (pinfunction "2_2") (pintype "passive"))
      (node (ref "R61") (pin "2") (pinfunction "2_2") (pintype "passive"))
      (node (ref "RPUART") (pin "3") (pinfunction "3_3") (pintype "passive"))
    )
    (net (code "213") (name "UART1_TX") (class "Default")
      (node (ref "R59") (pin "2") (pinfunction "2_2") (pintype "passive"))
      (node (ref "RPUART") (pin "1") (pinfunction "1_1") (pintype "passive"))
    )
    (net (code "214") (name "USB1_DP_N") (class "Default")
      (node (ref "IC1") (pin "42") (pinfunction "U2DM1_42") (pintype "bidirectional"))
      (node (ref "IC9") (pin "9") (pinfunction "DN_9") (pintype "bidirectional"))
    )
    (net (code "215") (name "USB1_DP_P") (class "Default")
      (node (ref "IC1") (pin "41") (pinfunction "U2DP1_41") (pintype "bidirectional"))
      (node (ref "IC9") (pin "8") (pinfunction "DP_8") (pintype "bidirectional"))
    )
    (net (code "216") (name "USB1_SSRX_N") (class "Default")
      (node (ref "IC1") (pin "39") (pinfunction "U3RXDN1_39") (pintype "input"))
    )
    (net (code "217") (name "USB1_SSRX_P") (class "Default")
      (node (ref "IC1") (pin "38") (pinfunction "U3RXDP1_38") (pintype "input"))
    )
    (net (code "218") (name "USB1_SSTX_N") (class "Default")
      (node (ref "IC1") (pin "36") (pinfunction "U3TXDN1_36") (pintype "output"))
    )
    (net (code "219") (name "USB1_SSTX_P") (class "Default")
      (node (ref "IC1") (pin "35") (pinfunction "U3TXDP1_35") (pintype "output"))
    )
    (net (code "220") (name "USB2_DP_N") (class "Default")
      (node (ref "IC1") (pin "51") (pinfunction "U2DM2_51") (pintype "bidirectional"))
      (node (ref "IC11") (pin "7") (pinfunction "USB_DM_7") (pintype "bidirectional"))
    )
    (net (code "221") (name "USB2_DP_P") (class "Default")
      (node (ref "IC1") (pin "50") (pinfunction "U2DP2_50") (pintype "bidirectional"))
      (node (ref "IC11") (pin "8") (pinfunction "USB_DP_8") (pintype "bidirectional"))
    )
    (net (code "222") (name "USB2_SSRX_N") (class "Default")
      (node (ref "IC1") (pin "48") (pinfunction "U3RXDN2_48") (pintype "input"))
    )
    (net (code "223") (name "USB2_SSRX_P") (class "Default")
      (node (ref "IC1") (pin "47") (pinfunction "U3RXDP2_47") (pintype "input"))
    )
    (net (code "224") (name "USB2_SSTX_N") (class "Default")
      (node (ref "IC1") (pin "45") (pinfunction "U3TXDN2_45") (pintype "output"))
    )
    (net (code "225") (name "USB2_SSTX_P") (class "Default")
      (node (ref "IC1") (pin "44") (pinfunction "U3TXDP2_44") (pintype "output"))
    )
    (net (code "226") (name "USB3_DP_N") (class "Default")
      (node (ref "IC1") (pin "59") (pinfunction "U2DM3_59") (pintype "bidirectional"))
      (node (ref "R51") (pin "1") (pinfunction "1_1") (pintype "passive"))
    )
    (net (code "227") (name "USB3_DP_P") (class "Default")
      (node (ref "IC1") (pin "58") (pinfunction "U2DP3_58") (pintype "bidirectional"))
      (node (ref "R52") (pin "2") (pinfunction "2_2") (pintype "passive"))
    )
    (net (code "228") (name "USB3_SSRX_N") (class "Default")
      (node (ref "IC1") (pin "56") (pinfunction "U3RXDN3_56") (pintype "input"))
    )
    (net (code "229") (name "USB3_SSRX_P") (class "Default")
      (node (ref "IC1") (pin "55") (pinfunction "U3RXDP3_55") (pintype "input"))
    )
    (net (code "230") (name "USB3_SSTX_N") (class "Default")
      (node (ref "IC1") (pin "53") (pinfunction "U3TXDN3_53") (pintype "output"))
    )
    (net (code "231") (name "USB3_SSTX_P") (class "Default")
      (node (ref "IC1") (pin "52") (pinfunction "U3TXDP3_52") (pintype "output"))
    )
    (net (code "232") (name "USB4_DP_N") (class "Default")
      (node (ref "IC1") (pin "68") (pinfunction "U2DM4_68") (pintype "bidirectional"))
      (node (ref "J4") (pin "2") (pinfunction "2_2") (pintype "passive"))
    )
    (net (code "233") (name "USB4_DP_P") (class "Default")
      (node (ref "IC1") (pin "67") (pinfunction "U2DP4_67") (pintype "bidirectional"))
      (node (ref "J4") (pin "3") (pinfunction "3_3") (pintype "passive"))
    )
    (net (code "234") (name "USB4_SSRX_N") (class "Default")
      (node (ref "IC1") (pin "65") (pinfunction "U3RXDN4_65") (pintype "input"))
    )
    (net (code "235") (name "USB4_SSRX_P") (class "Default")
      (node (ref "IC1") (pin "64") (pinfunction "U3RXDP4_64") (pintype "input"))
    )
    (net (code "236") (name "USB4_SSTX_N") (class "Default")
      (node (ref "IC1") (pin "62") (pinfunction "U3TXDN4_62") (pintype "output"))
    )
    (net (code "237") (name "USB4_SSTX_P") (class "Default")
      (node (ref "IC1") (pin "61") (pinfunction "U3TXDP4_61") (pintype "output"))
    )
    (net (code "238") (name "VDIV_BUF") (class "Default")
      (node (ref "C104") (pin "1") (pinfunction "1_1") (pintype "passive"))
      (node (ref "IC14") (pin "1") (pinfunction "+IN_1") (pintype "input"))
      (node (ref "R33") (pin "2") (pinfunction "2_2") (pintype "passive"))
      (node (ref "R34") (pin "1") (pinfunction "1_1") (pintype "passive"))
      (node (ref "R35") (pin "1") (pinfunction "1_1") (pintype "passive"))
    )
    (net (code "239") (name "VREF_LOGIC") (class "Default")
      (node (ref "C107") (pin "1") (pinfunction "1_1") (pintype "passive"))
      (node (ref "C108") (pin "1") (pinfunction "1_1") (pintype "passive"))
      (node (ref "C110") (pin "1") (pinfunction "1_1") (pintype "passive"))
      (node (ref "C112") (pin "1") (pinfunction "1_1") (pintype "passive"))
      (node (ref "IC14") (pin "3") (pinfunction "-IN_3") (pintype "input"))
      (node (ref "IC14") (pin "4") (pinfunction "OUT_4") (pintype "output"))
      (node (ref "IC15") (pin "10") (pinfunction "OE_10") (pintype "input"))
      (node (ref "IC15") (pin "2") (pinfunction "VCCA_2") (pintype "power_in"))
      (node (ref "IC16") (pin "10") (pinfunction "OE_10") (pintype "input"))
      (node (ref "IC16") (pin "2") (pinfunction "VCCA_2") (pintype "power_in"))
      (node (ref "IC17") (pin "10") (pinfunction "OE_10") (pintype "input"))
      (node (ref "IC17") (pin "2") (pinfunction "VCCA_2") (pintype "power_in"))
      (node (ref "IC18") (pin "3") (pinfunction "+IN_3") (pintype "input"))
      (node (ref "IC19") (pin "3") (pinfunction "+IN_3") (pintype "input"))
      (node (ref "IC20") (pin "3") (pinfunction "+IN_3") (pintype "input"))
      (node (ref "J7") (pin "1") (pinfunction "P$1_1") (pintype "bidirectional"))
      (node (ref "R37") (pin "1") (pinfunction "1_1") (pintype "passive"))
      (node (ref "R41") (pin "1") (pinfunction "1_1") (pintype "passive"))
      (node (ref "R42") (pin "1") (pinfunction "1_1") (pintype "passive"))
    )
    (net (code "240") (name "VSEL_1V8") (class "Default")
      (node (ref "IC11") (pin "23") (pinfunction "ADBUS6_23") (pintype "bidirectional"))
      (node (ref "R39") (pin "1") (pinfunction "1_1") (pintype "passive"))
      (node (ref "T2") (pin "1") (pinfunction "G_1") (pintype "passive"))
    )
    (net (code "241") (name "VSEL_2V5") (class "Default")
      (node (ref "IC11") (pin "24") (pinfunction "ADBUS7_24") (pintype "bidirectional"))
      (node (ref "R38") (pin "1") (pinfunction "1_1") (pintype "passive"))
      (node (ref "T1") (pin "1") (pinfunction "G_1") (pintype "passive"))
    )
    (net (code "242") (name "unconnected-(IC2-ENA-Pad5)") (class "Default")
      (node (ref "IC2") (pin "5") (pinfunction "ENA_5") (pintype "input"))
    )
    (net (code "243") (name "unconnected-(IC6-NC-Pad4)") (class "Default")
      (node (ref "IC6") (pin "4") (pinfunction "NC_4") (pintype "bidirectional"))
    )
    (net (code "244") (name "unconnected-(IC9-CLKOUT{slash}T1OUT-Pad54)") (class "Default")
      (node (ref "IC9") (pin "54") (pinfunction "CLKOUT/T1OUT_54") (pintype "bidirectional"))
    )
    (net (code "245") (name "unconnected-(IC9-CTL0-Pad29)") (class "Default")
      (node (ref "IC9") (pin "29") (pinfunction "CTL0_29") (pintype "bidirectional"))
    )
    (net (code "246") (name "unconnected-(IC9-CTL1-Pad30)") (class "Default")
      (node (ref "IC9") (pin "30") (pinfunction "CTL1_30") (pintype "bidirectional"))
    )
    (net (code "247") (name "unconnected-(IC9-CTL2-Pad31)") (class "Default")
      (node (ref "IC9") (pin "31") (pinfunction "CTL2_31") (pintype "bidirectional"))
    )
    (net (code "248") (name "unconnected-(IC9-IFCLK{slash}T0OUT-Pad13)") (class "Default")
      (node (ref "IC9") (pin "13") (pinfunction "IFCLK/T0OUT_13") (pintype "bidirectional"))
    )
    (net (code "249") (name "unconnected-(IC9-RDY0{slash}SLRD-Pad1)") (class "Default")
      (node (ref "IC9") (pin "1") (pinfunction "RDY0/SLRD_1") (pintype "bidirectional"))
    )
    (net (code "250") (name "unconnected-(IC9-RDY1{slash}SLRW-Pad2)") (class "Default")
      (node (ref "IC9") (pin "2") (pinfunction "RDY1/SLRW_2") (pintype "bidirectional"))
    )
    (net (code "251") (name "unconnected-(IC11-ADBUS3-Pad19)") (class "Default")
      (node (ref "IC11") (pin "19") (pinfunction "ADBUS3_19") (pintype "bidirectional"))
    )
    (net (code "252") (name "unconnected-(IC11-ADBUS4-Pad21)") (class "Default")
      (node (ref "IC11") (pin "21") (pinfunction "ADBUS4_21") (pintype "bidirectional"))
    )
    (net (code "253") (name "unconnected-(IC11-ADBUS5-Pad22)") (class "Default")
      (node (ref "IC11") (pin "22") (pinfunction "ADBUS5_22") (pintype "bidirectional"))
    )
    (net (code "254") (name "unconnected-(IC11-BDBUS5-Pad32)") (class "Default")
      (node (ref "IC11") (pin "32") (pinfunction "BDBUS5_32") (pintype "bidirectional"))
    )
    (net (code "255") (name "unconnected-(IC11-BDBUS6-Pad33)") (class "Default")
      (node (ref "IC11") (pin "33") (pinfunction "BDBUS6_33") (pintype "bidirectional"))
    )
    (net (code "256") (name "unconnected-(IC11-BDBUS7-Pad34)") (class "Default")
      (node (ref "IC11") (pin "34") (pinfunction "BDBUS7_34") (pintype "bidirectional"))
    )
    (net (code "257") (name "unconnected-(IC11-~{PWREN}-Pad60)") (class "Default")
      (node (ref "IC11") (pin "60") (pinfunction "~{PWREN}_60") (pintype "output"))
    )
    (net (code "258") (name "unconnected-(IC11-~{SUSPEND}-Pad36)") (class "Default")
      (node (ref "IC11") (pin "36") (pinfunction "~{SUSPEND}_36") (pintype "output"))
    )
    (net (code "259") (name "unconnected-(IC13-NC-Pad4)") (class "Default")
      (node (ref "IC13") (pin "4") (pinfunction "NC_4") (pintype "bidirectional"))
    )
    (net (code "260") (name "unconnected-(IC15-A5-Pad6)") (class "Default")
      (node (ref "IC15") (pin "6") (pinfunction "A5_6") (pintype "bidirectional"))
    )
    (net (code "261") (name "unconnected-(IC15-A6-Pad7)") (class "Default")
      (node (ref "IC15") (pin "7") (pinfunction "A6_7") (pintype "bidirectional"))
    )
    (net (code "262") (name "unconnected-(IC15-B5-Pad15)") (class "Default")
      (node (ref "IC15") (pin "15") (pinfunction "B5_15") (pintype "bidirectional"))
    )
    (net (code "263") (name "unconnected-(IC15-B6-Pad14)") (class "Default")
      (node (ref "IC15") (pin "14") (pinfunction "B6_14") (pintype "bidirectional"))
    )
    (net (code "264") (name "unconnected-(IC21-GPIO3-Pad5)") (class "Default")
      (node (ref "IC21") (pin "5") (pinfunction "GPIO3_5") (pintype "bidirectional"))
    )
    (net (code "265") (name "unconnected-(IC21-GPIO9-Pad12)") (class "Default")
      (node (ref "IC21") (pin "12") (pinfunction "GPIO9_12") (pintype "bidirectional"))
    )
    (net (code "266") (name "unconnected-(IC21-GPIO10-Pad13)") (class "Default")
      (node (ref "IC21") (pin "13") (pinfunction "GPIO10_13") (pintype "bidirectional"))
    )
    (net (code "267") (name "unconnected-(IC21-GPIO11-Pad14)") (class "Default")
      (node (ref "IC21") (pin "14") (pinfunction "GPIO11_14") (pintype "bidirectional"))
    )
    (net (code "268") (name "unconnected-(IC21-GPIO17-Pad28)") (class "Default")
      (node (ref "IC21") (pin "28") (pinfunction "GPIO17_28") (pintype "bidirectional"))
    )
    (net (code "269") (name "unconnected-(IC21-GPIO18-Pad29)") (class "Default")
      (node (ref "IC21") (pin "29") (pinfunction "GPIO18_29") (pintype "bidirectional"))
    )
    (net (code "270") (name "unconnected-(IC21-GPIO19-Pad30)") (class "Default")
      (node (ref "IC21") (pin "30") (pinfunction "GPIO19_30") (pintype "bidirectional"))
    )
    (net (code "271") (name "unconnected-(IC21-GPIO20-Pad31)") (class "Default")
      (node (ref "IC21") (pin "31") (pinfunction "GPIO20_31") (pintype "bidirectional"))
    )
    (net (code "272") (name "unconnected-(IC21-GPIO21-Pad32)") (class "Default")
      (node (ref "IC21") (pin "32") (pinfunction "GPIO21_32") (pintype "bidirectional"))
    )
    (net (code "273") (name "unconnected-(IC21-GPIO22-Pad34)") (class "Default")
      (node (ref "IC21") (pin "34") (pinfunction "GPIO22_34") (pintype "bidirectional"))
    )
    (net (code "274") (name "unconnected-(IC21-GPIO23-Pad35)") (class "Default")
      (node (ref "IC21") (pin "35") (pinfunction "GPIO23_35") (pintype "bidirectional"))
    )
    (net (code "275") (name "unconnected-(IC21-GPIO24-Pad36)") (class "Default")
      (node (ref "IC21") (pin "36") (pinfunction "GPIO24_36") (pintype "bidirectional"))
    )
    (net (code "276") (name "unconnected-(IC21-GPIO25-Pad37)") (class "Default")
      (node (ref "IC21") (pin "37") (pinfunction "GPIO25_37") (pintype "bidirectional"))
    )
    (net (code "277") (name "unconnected-(IC21-GPIO26{slash}ADC0-Pad38)") (class "Default")
      (node (ref "IC21") (pin "38") (pinfunction "GPIO26/ADC0_38") (pintype "bidirectional"))
    )
    (net (code "278") (name "unconnected-(IC21-GPIO27{slash}ADC1-Pad39)") (class "Default")
      (node (ref "IC21") (pin "39") (pinfunction "GPIO27/ADC1_39") (pintype "bidirectional"))
    )
    (net (code "279") (name "unconnected-(IC21-GPIO28{slash}ADC2-Pad40)") (class "Default")
      (node (ref "IC21") (pin "40") (pinfunction "GPIO28/ADC2_40") (pintype "bidirectional"))
    )
    (net (code "280") (name "unconnected-(IC21-GPIO29{slash}ADC3-Pad41)") (class "Default")
      (node (ref "IC21") (pin "41") (pinfunction "GPIO29/ADC3_41") (pintype "bidirectional"))
    )
    (net (code "281") (name "unconnected-(IC23-P$1-Pad1)") (class "Default")
      (node (ref "IC23") (pin "1") (pinfunction "P$1_1") (pintype "no_connect"))
    )
    (net (code "282") (name "unconnected-(IC24-P$1-Pad1)") (class "Default")
      (node (ref "IC24") (pin "1") (pinfunction "P$1_1") (pintype "no_connect"))
    )
    (net (code "283") (name "unconnected-(IC25-NC-Pad4)") (class "Default")
      (node (ref "IC25") (pin "4") (pinfunction "NC_4") (pintype "bidirectional"))
    )
    (net (code "284") (name "unconnected-(J4-Pad4)") (class "Default")
      (node (ref "J4") (pin "4") (pinfunction "4_4") (pintype "passive"))
    )
    (net (code "285") (name "unconnected-(UART1-Pad1)") (class "Default")
      (node (ref "UART1") (pin "1") (pinfunction "1_1") (pintype "passive"))
    )
    (net (code "286") (name "unconnected-(UART2-Pad10)") (class "Default")
      (node (ref "UART2") (pin "10") (pinfunction "10_10") (pintype "passive"))
    )
    (net (code "287") (name "~{CLKREQ}") (class "Default")
      (node (ref "PCIE-1X1") (pin "B12") (pinfunction "~{CLKREQ}_B12") (pintype "bidirectional"))
    )
    (net (code "288") (name "~{CTS1_OUT}") (class "Default")
      (node (ref "IC16") (pin "6") (pinfunction "A5_6") (pintype "bidirectional"))
      (node (ref "UART1") (pin "5") (pinfunction "5_5") (pintype "passive"))
    )
    (net (code "289") (name "~{CTS1}") (class "Default")
      (node (ref "IC11") (pin "41") (pinfunction "CDBUS3_41") (pintype "bidirectional"))
      (node (ref "IC16") (pin "15") (pinfunction "B5_15") (pintype "bidirectional"))
    )
    (net (code "290") (name "~{CTS2_OUT}") (class "Default")
      (node (ref "IC17") (pin "6") (pinfunction "A5_6") (pintype "bidirectional"))
      (node (ref "UART2") (pin "6") (pinfunction "6_6") (pintype "passive"))
    )
    (net (code "291") (name "~{CTS2}") (class "Default")
      (node (ref "IC11") (pin "54") (pinfunction "DDBUS3_54") (pintype "bidirectional"))
      (node (ref "IC17") (pin "15") (pinfunction "B5_15") (pintype "bidirectional"))
    )
    (net (code "292") (name "~{DCD1_OUT}") (class "Default")
      (node (ref "IC16") (pin "3") (pinfunction "A2_3") (pintype "bidirectional"))
      (node (ref "UART1") (pin "10") (pinfunction "10_10") (pintype "passive"))
    )
    (net (code "293") (name "~{DCD1}") (class "Default")
      (node (ref "IC11") (pin "45") (pinfunction "CDBUS6_45") (pintype "bidirectional"))
      (node (ref "IC16") (pin "18") (pinfunction "B2_18") (pintype "bidirectional"))
    )
    (net (code "294") (name "~{DCD2_OUT}") (class "Default")
      (node (ref "IC17") (pin "3") (pinfunction "A2_3") (pintype "bidirectional"))
      (node (ref "UART2") (pin "1") (pinfunction "1_1") (pintype "passive"))
    )
    (net (code "295") (name "~{DCD2}") (class "Default")
      (node (ref "IC11") (pin "58") (pinfunction "DDBUS6_58") (pintype "bidirectional"))
      (node (ref "IC17") (pin "18") (pinfunction "B2_18") (pintype "bidirectional"))
    )
    (net (code "296") (name "~{DSR1_OUT}") (class "Default")
      (node (ref "IC16") (pin "4") (pinfunction "A3_4") (pintype "bidirectional"))
      (node (ref "UART1") (pin "9") (pinfunction "9_9") (pintype "passive"))
    )
    (net (code "297") (name "~{DSR1}") (class "Default")
      (node (ref "IC11") (pin "44") (pinfunction "CDBUS5_44") (pintype "bidirectional"))
      (node (ref "IC16") (pin "17") (pinfunction "B3_17") (pintype "bidirectional"))
    )
    (net (code "298") (name "~{DSR2_OUT}") (class "Default")
      (node (ref "IC17") (pin "4") (pinfunction "A3_4") (pintype "bidirectional"))
      (node (ref "UART2") (pin "2") (pinfunction "2_2") (pintype "passive"))
    )
    (net (code "299") (name "~{DSR2}") (class "Default")
      (node (ref "IC11") (pin "57") (pinfunction "DDBUS5_57") (pintype "bidirectional"))
      (node (ref "IC17") (pin "17") (pinfunction "B3_17") (pintype "bidirectional"))
    )
    (net (code "300") (name "~{DTR1_OUT}") (class "Default")
      (node (ref "IC16") (pin "5") (pinfunction "A4_5") (pintype "bidirectional"))
      (node (ref "UART1") (pin "4") (pinfunction "4_4") (pintype "passive"))
    )
    (net (code "301") (name "~{DTR1}") (class "Default")
      (node (ref "IC11") (pin "43") (pinfunction "CDBUS4_43") (pintype "bidirectional"))
      (node (ref "IC16") (pin "16") (pinfunction "B4_16") (pintype "bidirectional"))
    )
    (net (code "302") (name "~{DTR2_OUT}") (class "Default")
      (node (ref "IC17") (pin "5") (pinfunction "A4_5") (pintype "bidirectional"))
      (node (ref "UART2") (pin "7") (pinfunction "7_7") (pintype "passive"))
    )
    (net (code "303") (name "~{DTR2}") (class "Default")
      (node (ref "IC11") (pin "55") (pinfunction "DDBUS4_55") (pintype "bidirectional"))
      (node (ref "IC17") (pin "16") (pinfunction "B4_16") (pintype "bidirectional"))
    )
    (net (code "304") (name "~{GRST}") (class "Default")
      (node (ref "!RST") (pin "TP") (pinfunction "TP_TP") (pintype "input"))
      (node (ref "C42") (pin "1") (pinfunction "1_1") (pintype "passive"))
      (node (ref "C54") (pin "1") (pinfunction "1_1") (pintype "passive"))
      (node (ref "D1") (pin "1") (pinfunction "A_1") (pintype "passive"))
      (node (ref "IC1") (pin "14") (pinfunction "PONRSTB_14") (pintype "input"))
      (node (ref "IC3") (pin "9") (pinfunction "PG_9") (pintype "output"))
      (node (ref "R3") (pin "2") (pinfunction "2_2") (pintype "passive"))
      (node (ref "R9") (pin "2") (pinfunction "2_2") (pintype "passive"))
    )
    (net (code "305") (name "~{OVERCUR1}") (class "Default")
      (node (ref "IC1") (pin "26") (pinfunction "OCI1B_26") (pintype "input"))
      (node (ref "IC4") (pin "10") (pinfunction "~{FAULT1}_10") (pintype "output"))
    )
    (net (code "306") (name "~{OVERCUR2}") (class "Default")
      (node (ref "IC1") (pin "24") (pinfunction "OCI2B_24") (pintype "input"))
      (node (ref "IC4") (pin "6") (pinfunction "~{FAULT2}_6") (pintype "output"))
    )
    (net (code "307") (name "~{OVERCUR3}") (class "Default")
      (node (ref "IC1") (pin "22") (pinfunction "OCI3B_22") (pintype "input"))
      (node (ref "IC5") (pin "10") (pinfunction "~{FAULT1}_10") (pintype "output"))
    )
    (net (code "308") (name "~{OVERCUR4}") (class "Default")
      (node (ref "IC1") (pin "20") (pinfunction "OCI4B_20") (pintype "input"))
      (node (ref "IC5") (pin "6") (pinfunction "~{FAULT2}_6") (pintype "output"))
    )
    (net (code "309") (name "~{PCIE_PRSNT}") (class "Default")
      (node (ref "PCIE-1X1") (pin "A1") (pinfunction "~{PRSNT1}_A1") (pintype "bidirectional"))
      (node (ref "PCIE-1X1") (pin "B17") (pinfunction "~{PRSNT2}_B17") (pintype "bidirectional"))
    )
    (net (code "310") (name "~{PECREQ}") (class "Default")
      (node (ref "!REQ") (pin "TP") (pinfunction "TP_TP") (pintype "input"))
      (node (ref "IC1") (pin "13") (pinfunction "PECREQB_13") (pintype "output"))
    )
    (net (code "311") (name "~{PERST}") (class "Default")
      (node (ref "!PERST") (pin "TP") (pinfunction "TP_TP") (pintype "input"))
      (node (ref "IC1") (pin "2") (pinfunction "PERSTB_2") (pintype "input"))
      (node (ref "PCIE-1X1") (pin "A11") (pinfunction "~{PERST}_A11") (pintype "bidirectional"))
    )
    (net (code "312") (name "~{PWRON1}") (class "Default")
      (node (ref "IC1") (pin "27") (pinfunction "PPON1_27") (pintype "output"))
      (node (ref "IC4") (pin "4") (pinfunction "EN1_4") (pintype "input"))
    )
    (net (code "313") (name "~{PWRON2}") (class "Default")
      (node (ref "IC1") (pin "25") (pinfunction "PPON2_25") (pintype "output"))
      (node (ref "IC4") (pin "5") (pinfunction "EN2_5") (pintype "input"))
    )
    (net (code "314") (name "~{PWRON3}") (class "Default")
      (node (ref "IC1") (pin "23") (pinfunction "PPON3_23") (pintype "output"))
      (node (ref "IC5") (pin "4") (pinfunction "EN1_4") (pintype "input"))
    )
    (net (code "315") (name "~{PWRON4}") (class "Default")
      (node (ref "IC1") (pin "21") (pinfunction "PPON4_21") (pintype "output"))
      (node (ref "IC5") (pin "5") (pinfunction "EN2_5") (pintype "input"))
    )
    (net (code "316") (name "~{RI1_OUT}") (class "Default")
      (node (ref "IC16") (pin "1") (pinfunction "A1_1") (pintype "bidirectional"))
      (node (ref "UART1") (pin "3") (pinfunction "3_3") (pintype "passive"))
    )
    (net (code "317") (name "~{RI1}") (class "Default")
      (node (ref "IC11") (pin "46") (pinfunction "CDBUS7_46") (pintype "bidirectional"))
      (node (ref "IC16") (pin "20") (pinfunction "B1_20") (pintype "bidirectional"))
    )
    (net (code "318") (name "~{RI2_OUT}") (class "Default")
      (node (ref "IC17") (pin "1") (pinfunction "A1_1") (pintype "bidirectional"))
      (node (ref "UART2") (pin "8") (pinfunction "8_8") (pintype "passive"))
    )
    (net (code "319") (name "~{RI2}") (class "Default")
      (node (ref "IC11") (pin "59") (pinfunction "DDBUS7_59") (pintype "bidirectional"))
      (node (ref "IC17") (pin "20") (pinfunction "B1_20") (pintype "bidirectional"))
    )
    (net (code "320") (name "~{RTS1_OUT}") (class "Default")
      (node (ref "IC16") (pin "7") (pinfunction "A6_7") (pintype "bidirectional"))
      (node (ref "UART1") (pin "7") (pinfunction "7_7") (pintype "passive"))
    )
    (net (code "321") (name "~{RTS1}") (class "Default")
      (node (ref "IC11") (pin "40") (pinfunction "CDBUS2_40") (pintype "bidirectional"))
      (node (ref "IC16") (pin "14") (pinfunction "B6_14") (pintype "bidirectional"))
    )
    (net (code "322") (name "~{RTS2_OUT}") (class "Default")
      (node (ref "IC17") (pin "7") (pinfunction "A6_7") (pintype "bidirectional"))
      (node (ref "UART2") (pin "4") (pinfunction "4_4") (pintype "passive"))
    )
    (net (code "323") (name "~{RTS2}") (class "Default")
      (node (ref "IC11") (pin "53") (pinfunction "DDBUS2_53") (pintype "bidirectional"))
      (node (ref "IC17") (pin "14") (pinfunction "B6_14") (pintype "bidirectional"))
    )
    (net (code "324") (name "~{SMI}") (class "Default")
      (node (ref "!SMI") (pin "TP") (pinfunction "TP_TP") (pintype "input"))
      (node (ref "IC1") (pin "1") (pinfunction "SMIB_1") (pintype "output"))
    )
    (net (code "325") (name "~{SPI_CS}") (class "Default")
      (node (ref "IC1") (pin "17") (pinfunction "SPICSB_17") (pintype "bidirectional"))
    )
    (net (code "326") (name "~{WAKE_R}") (class "Default")
      (node (ref "PCIE-1X1") (pin "B11") (pinfunction "~{WAKE}_B11") (pintype "bidirectional"))
      (node (ref "R1") (pin "1") (pinfunction "1_1") (pintype "passive"))
    )
    (net (code "327") (name "~{WAKE}") (class "Default")
      (node (ref "C10") (pin "1") (pinfunction "1_1") (pintype "passive"))
      (node (ref "IC1") (pin "3") (pinfunction "PEWAKEB_3") (pintype "output"))
      (node (ref "R1") (pin "2") (pinfunction "2_2") (pintype "passive"))
    )
  )
)
